# design.net
KiCad netlist of a schematic drawn in Altium Designer
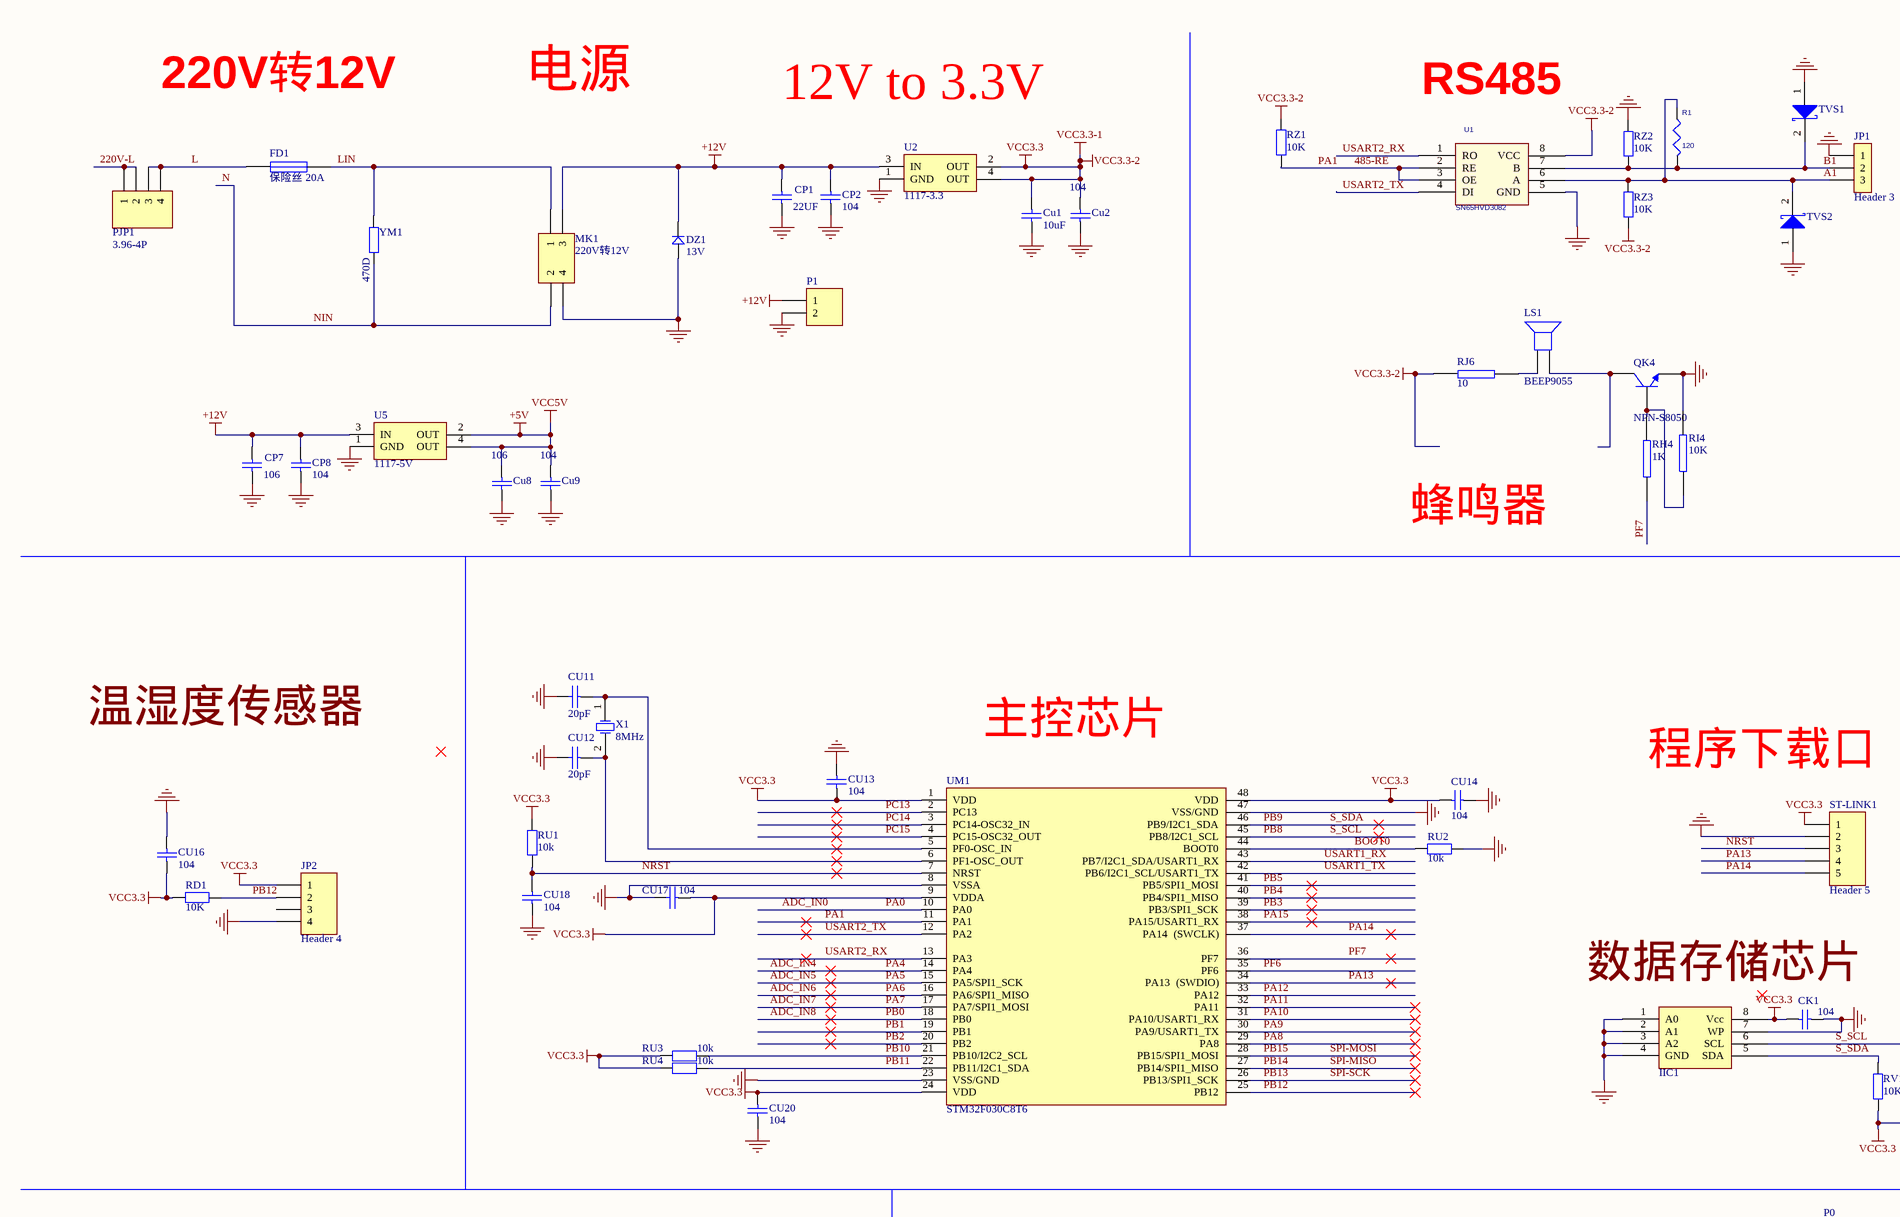
[diagram p0: 全兼容主控.SchDoc, top left]
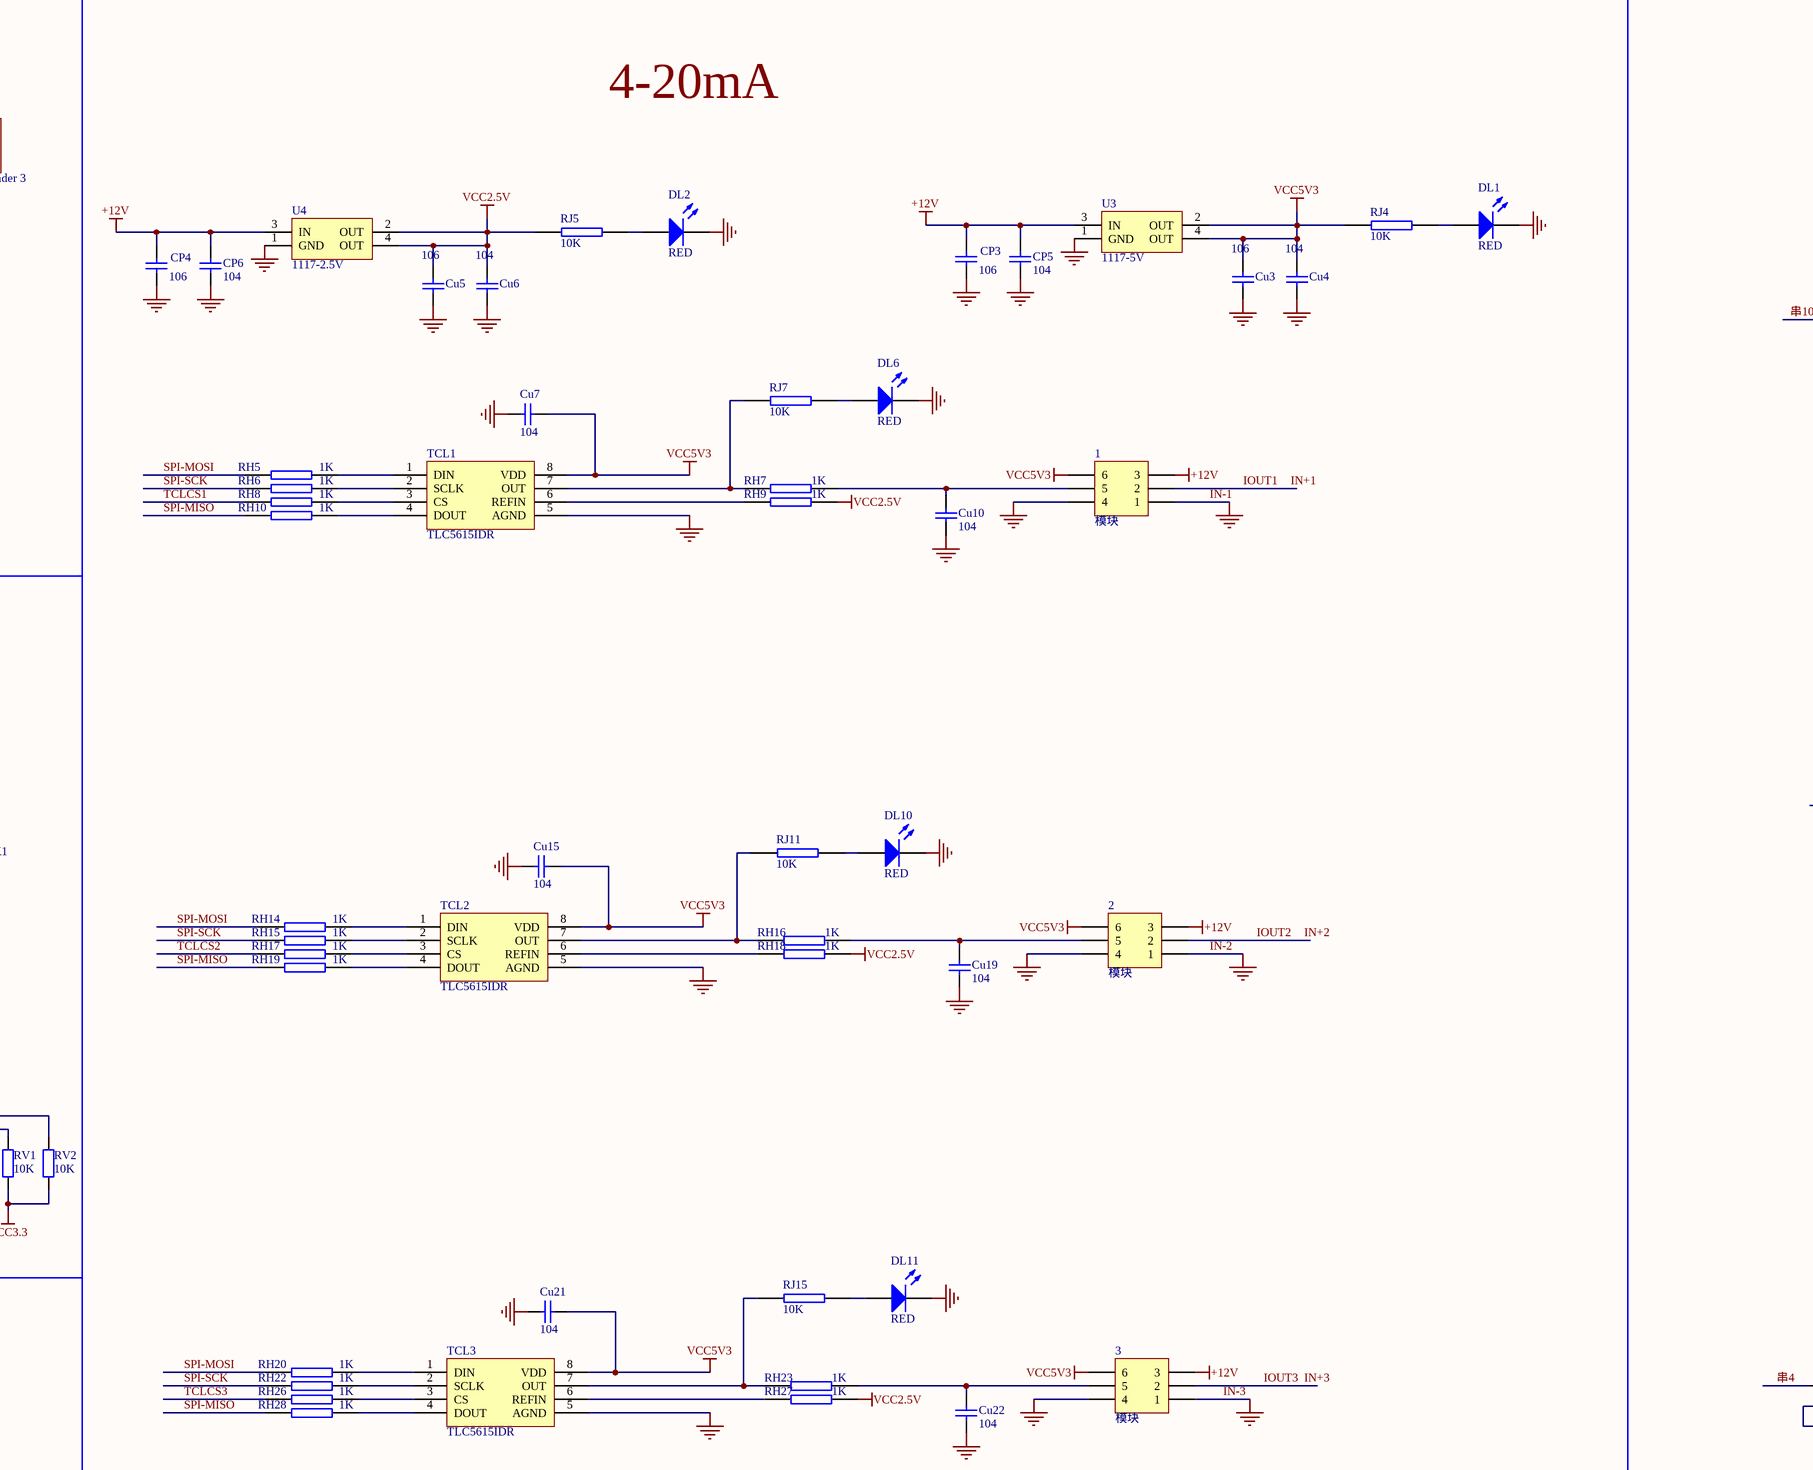
[diagram p1: 全兼容主控.SchDoc, top middle]
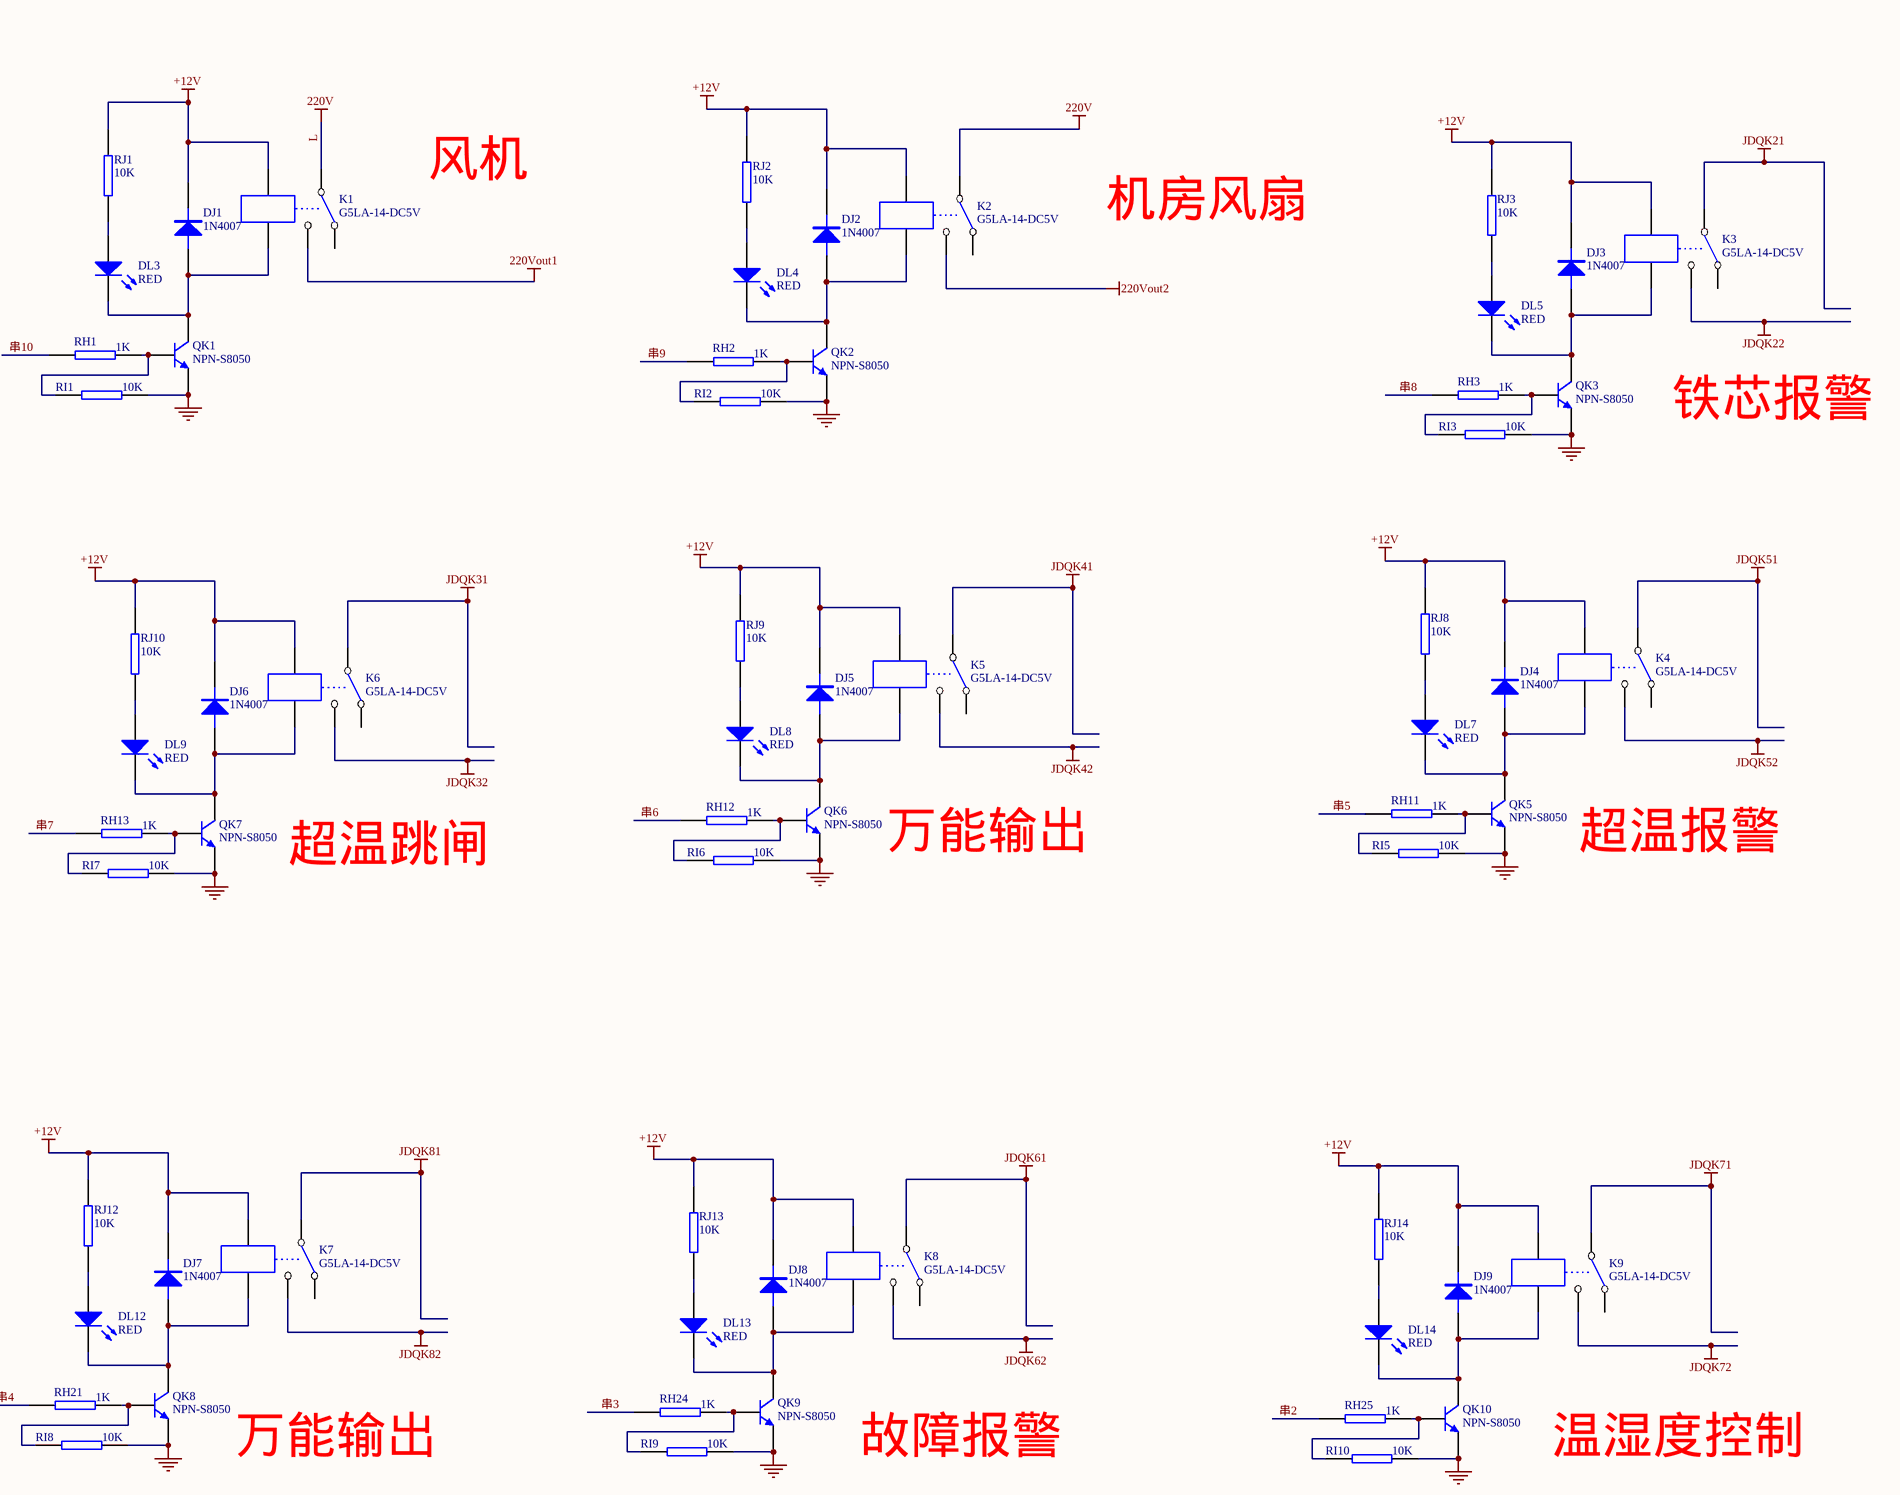
[diagram p2: 全兼容主控.SchDoc, top right]
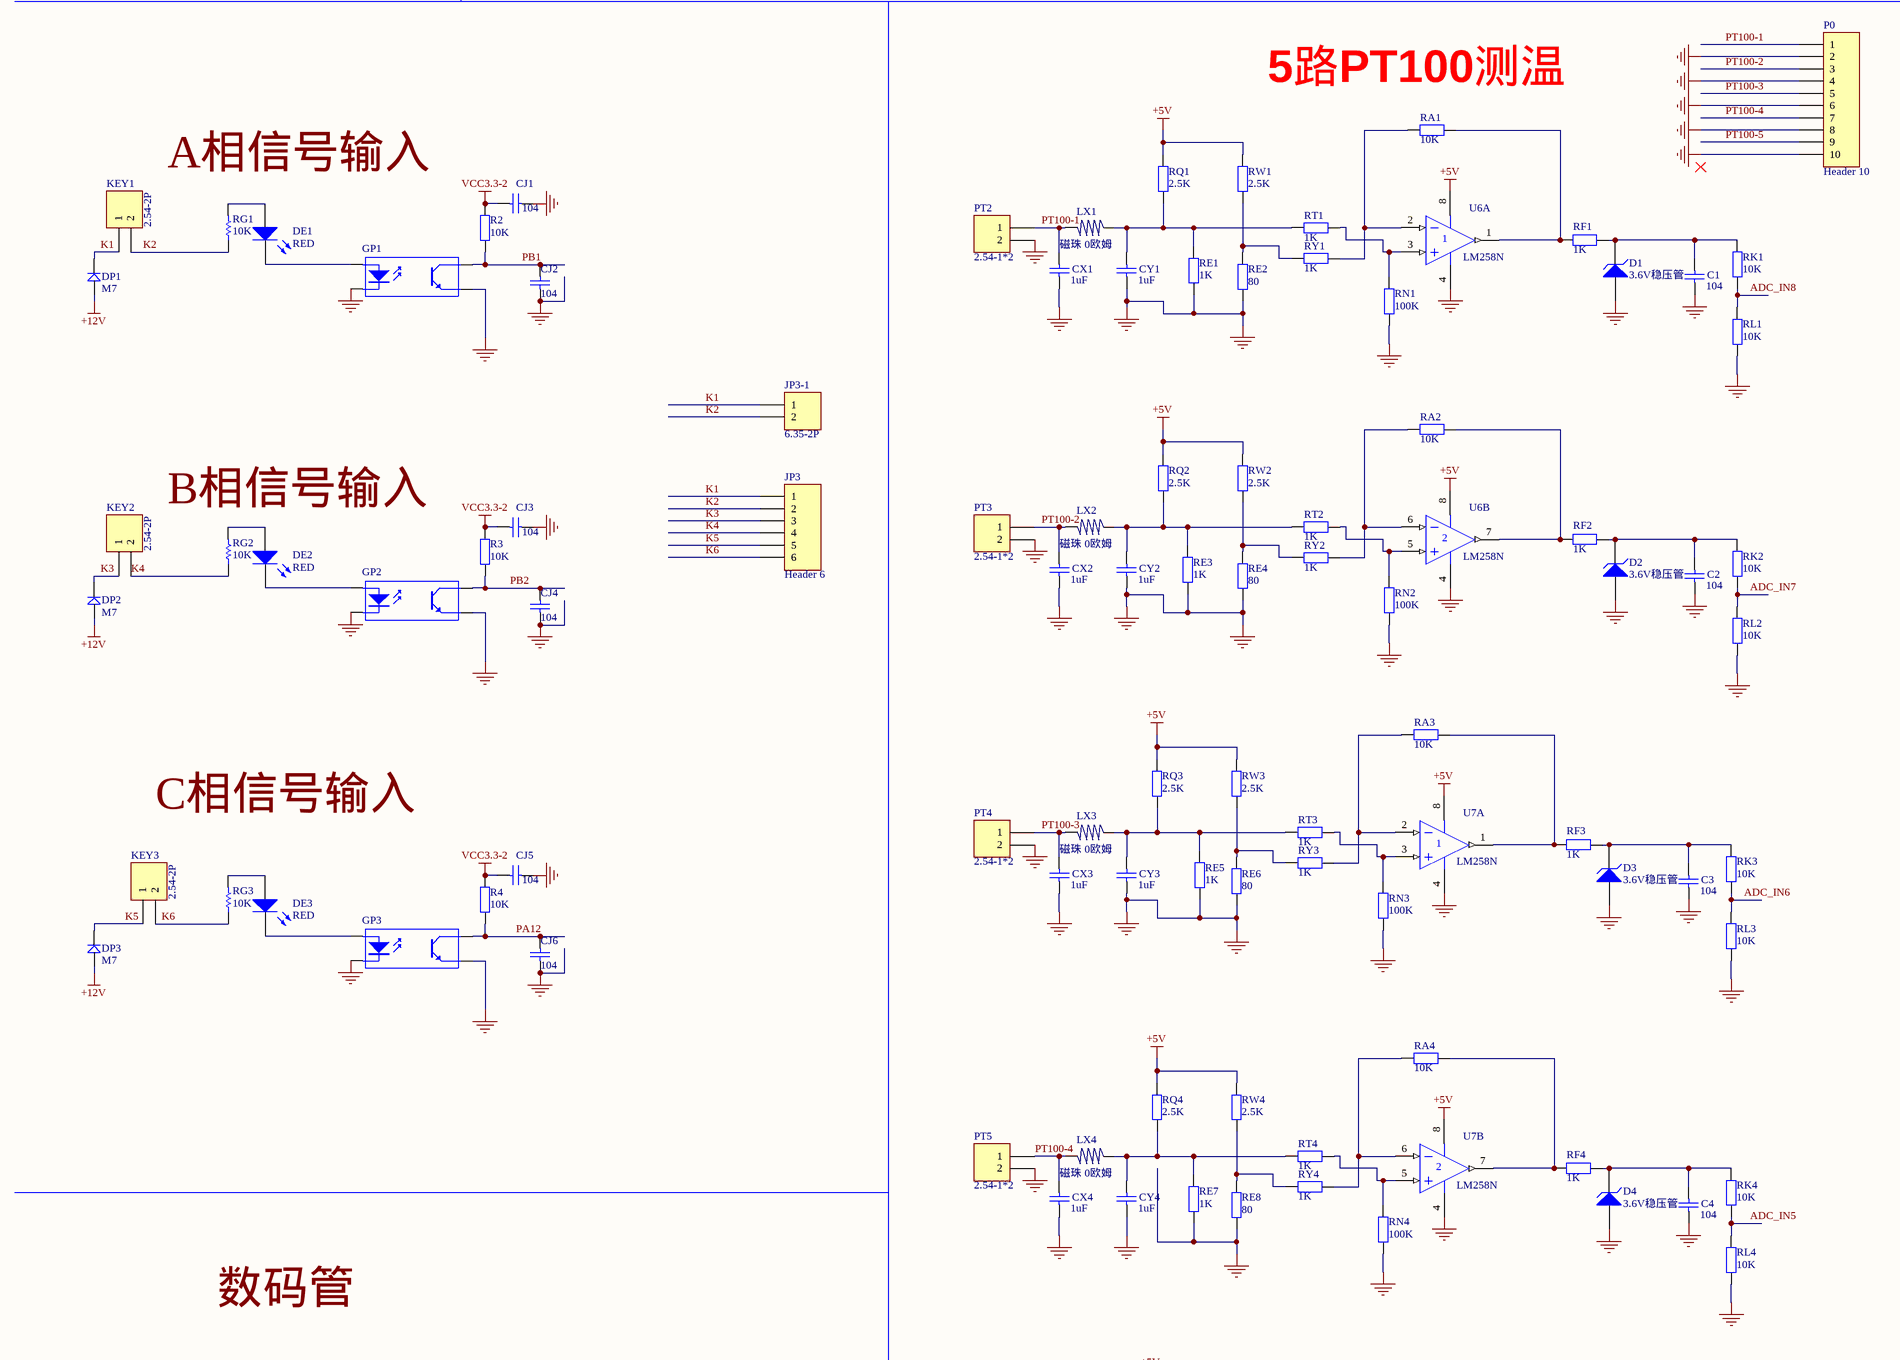
[diagram p3: 全兼容主控.SchDoc, centre left]
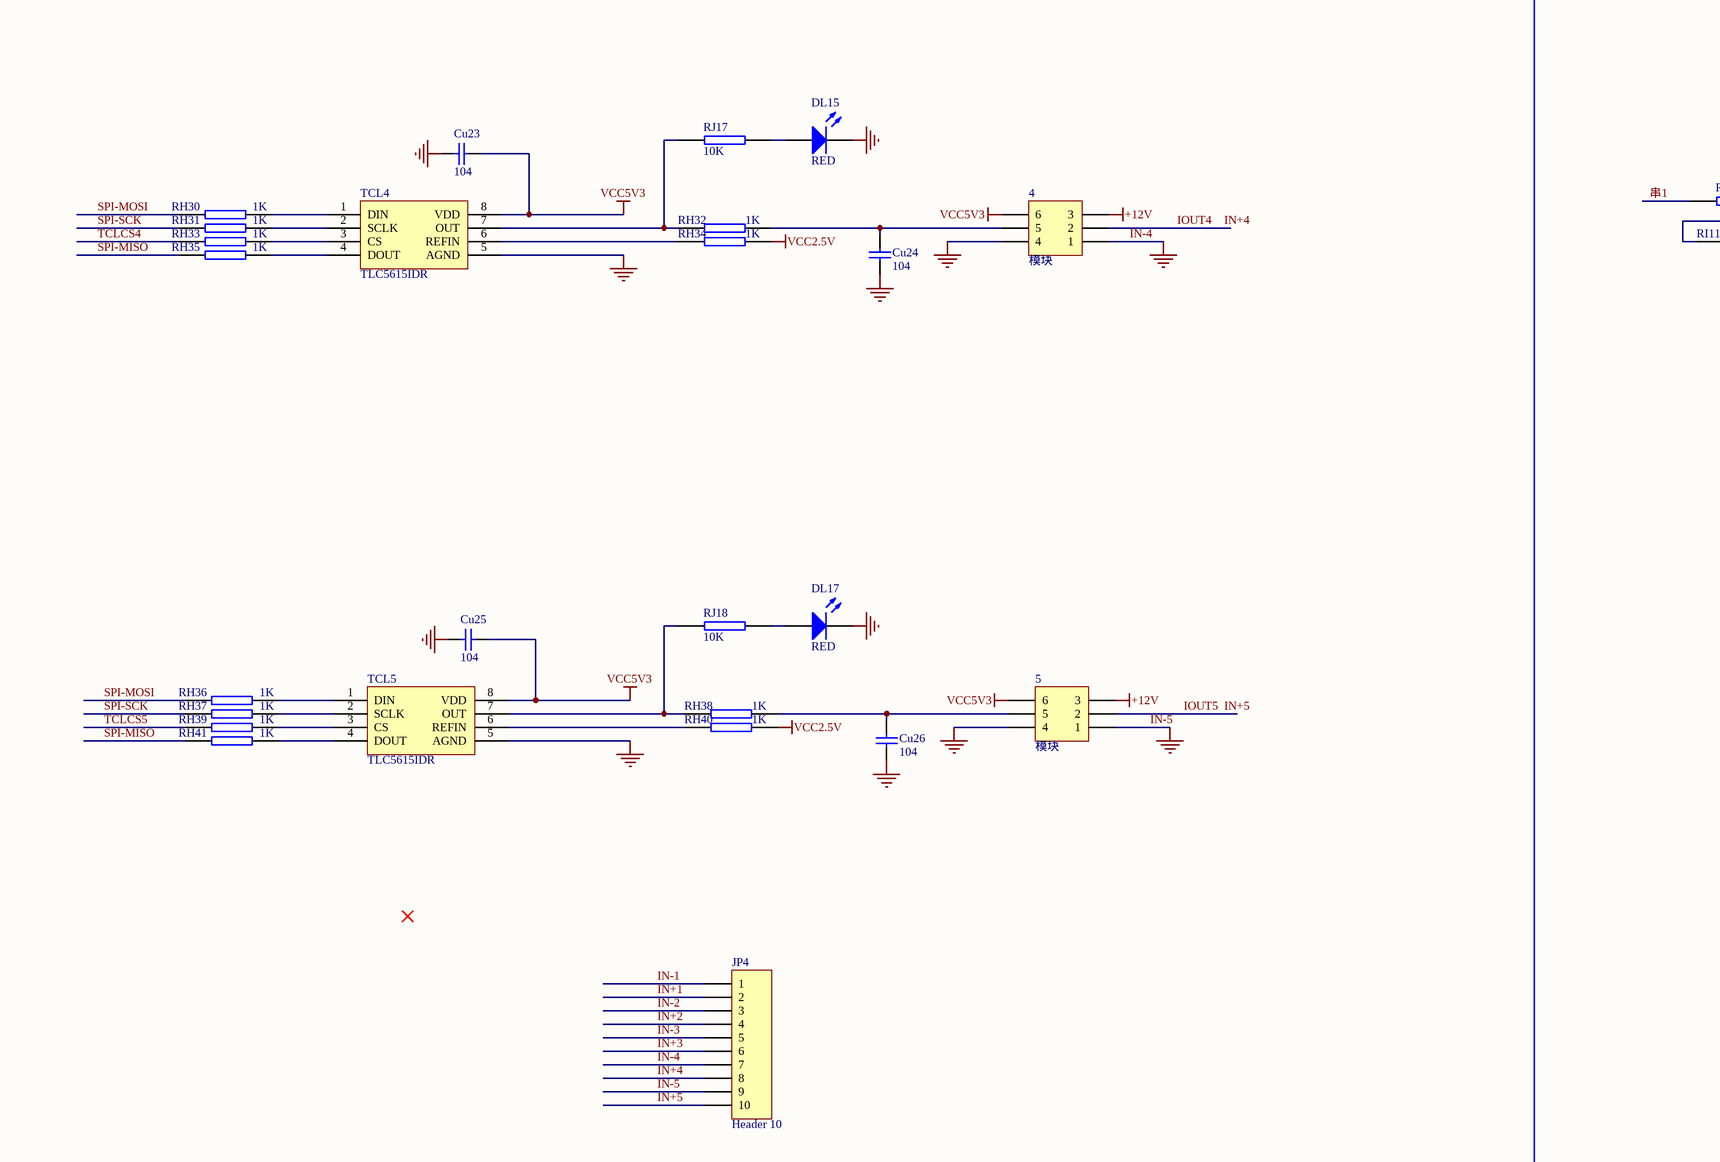
[diagram p4: 全兼容主控.SchDoc, centre middle]
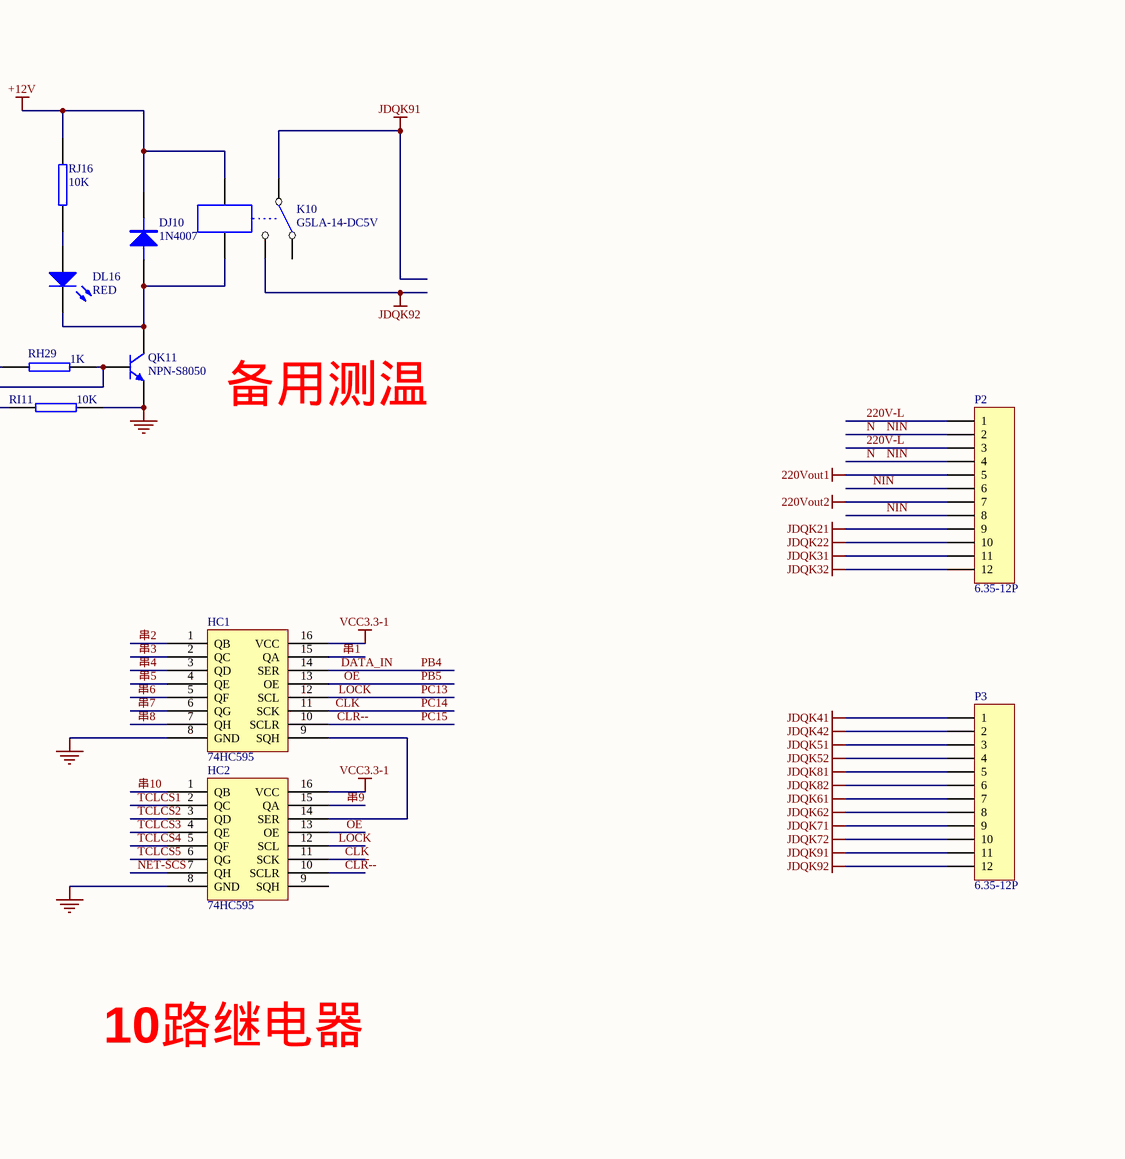
[diagram p5: 全兼容主控.SchDoc, centre right]
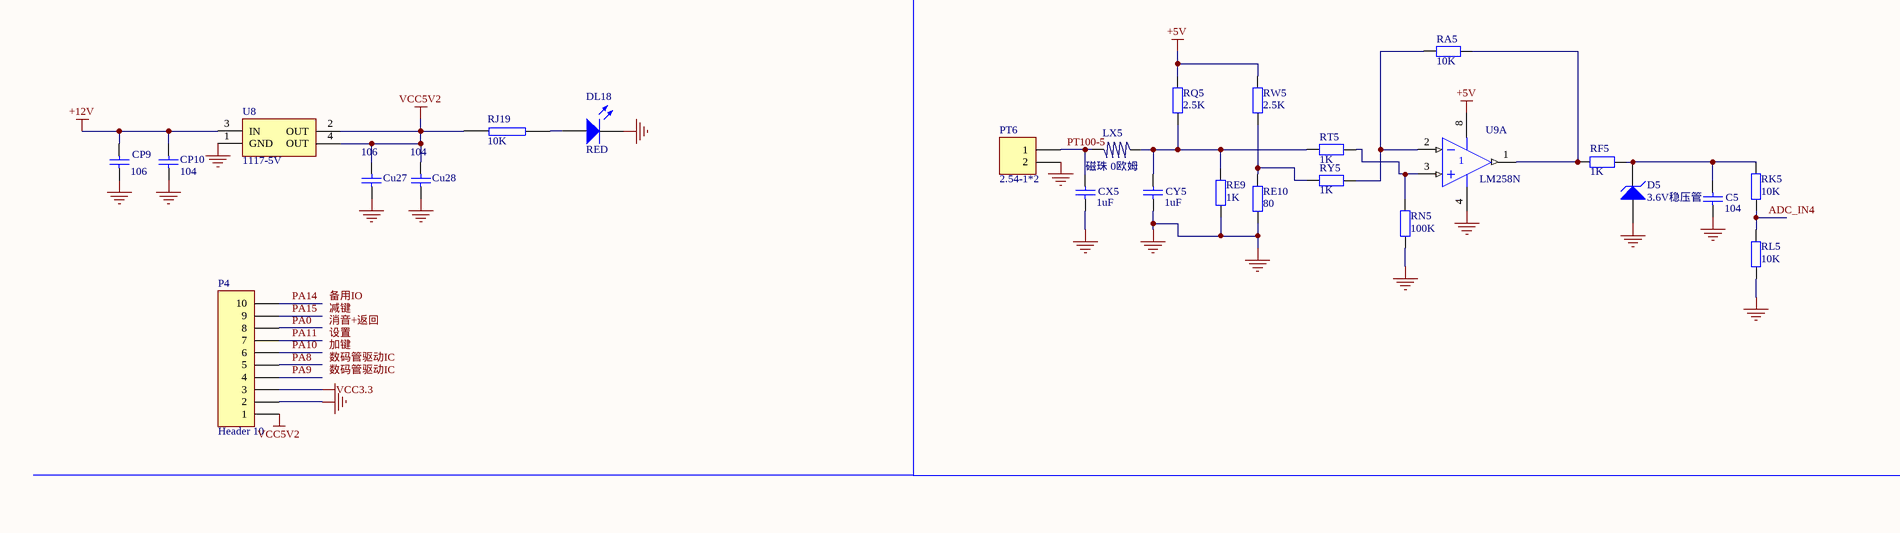
[diagram p6: 全兼容主控.SchDoc, bottom left]
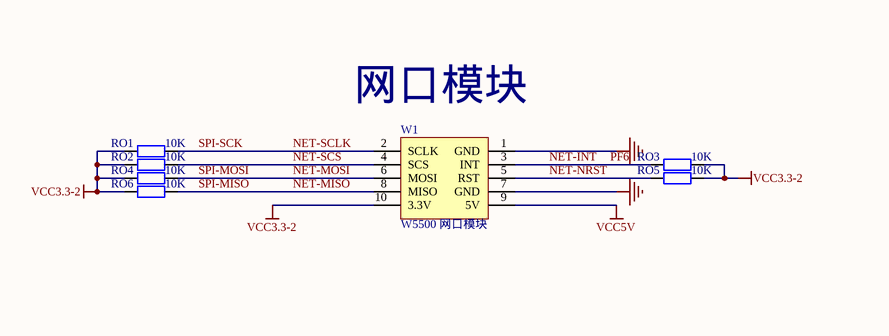
[diagram p7: 全兼容主控.SchDoc, bottom middle]
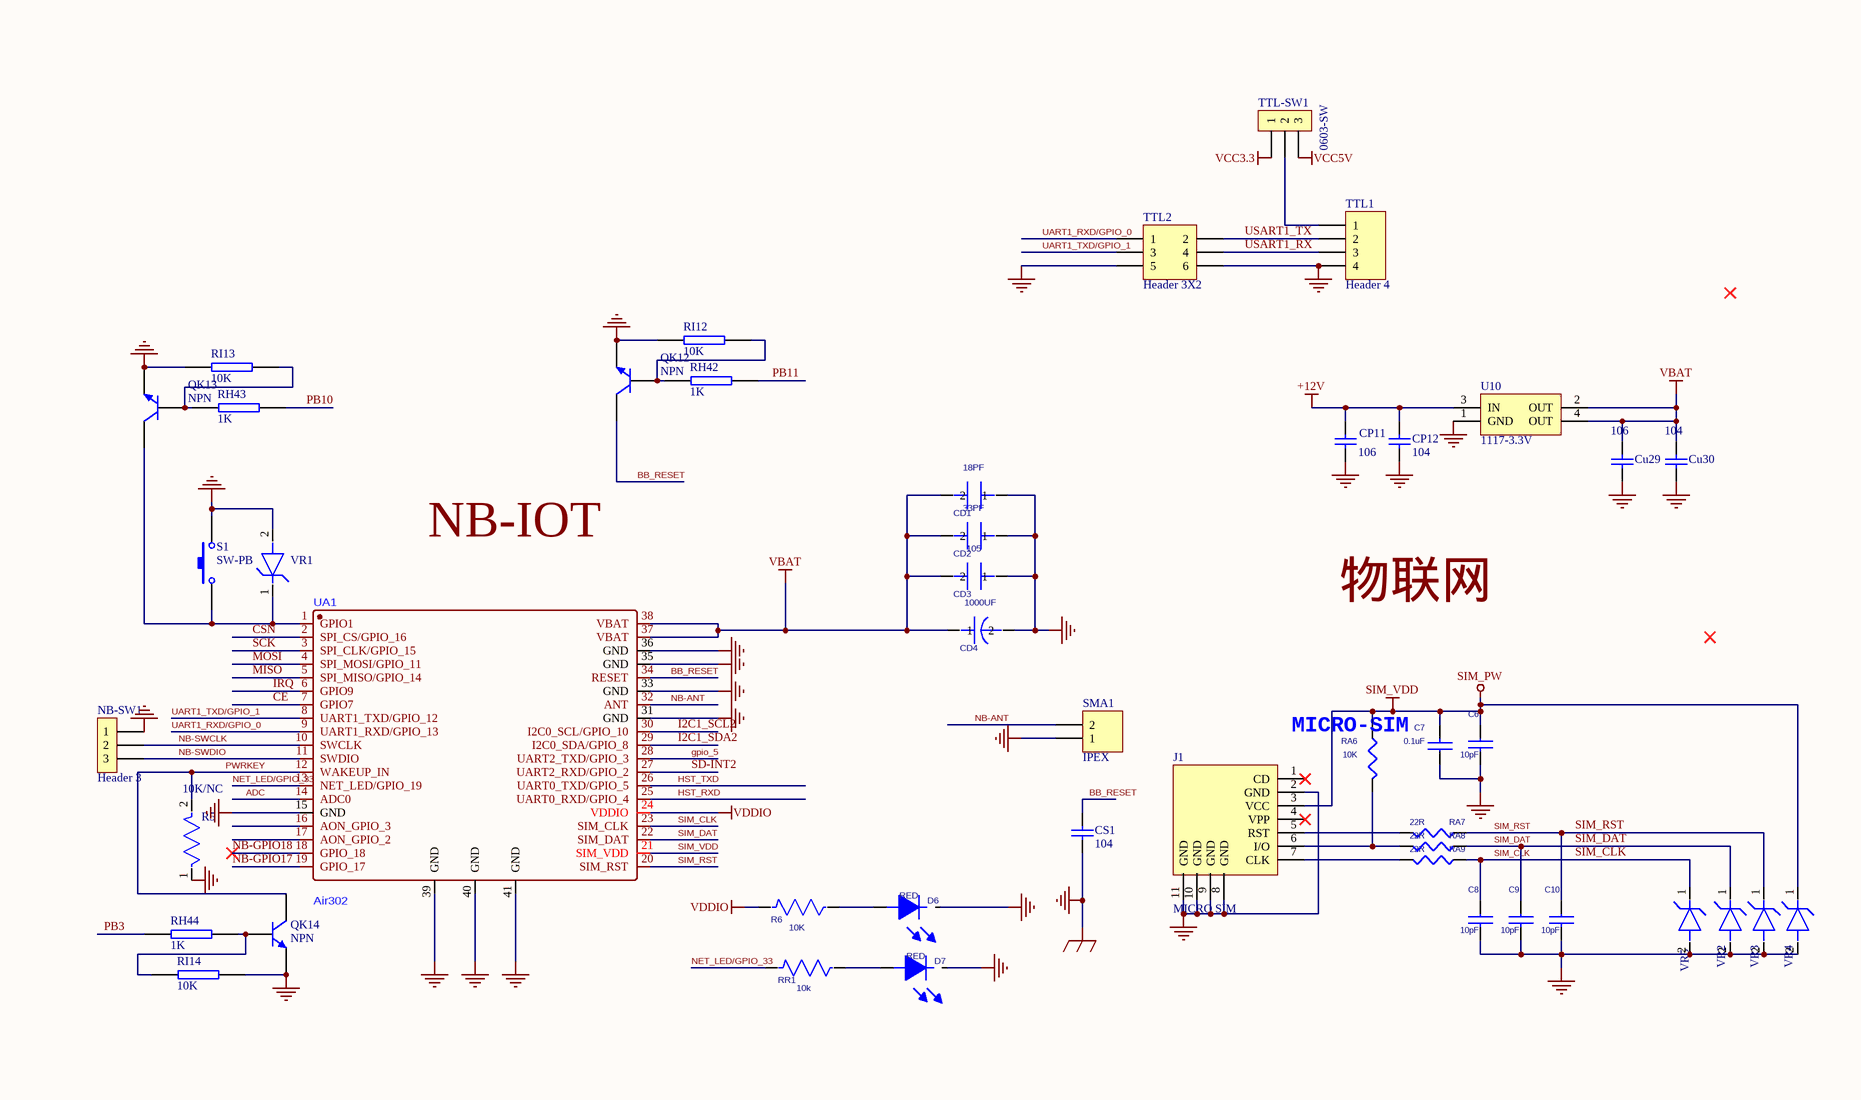
[diagram p8: 全兼容主控.SchDoc, bottom right]

(export (version "E")
  (design (tool "Eeschema 10.0.6"))
  (components
    (comp (ref "1")
      (value "模块")
      (footprint "0-5V转4-20mA")
      (description "Header, 3-Pin, Dual row")
      (libsource (lib "SCH原理图库") (part "Header 3X2A"))
    )
    (comp (ref "2")
      (value "模块")
      (footprint "0-5V转4-20mA")
      (description "Header, 3-Pin, Dual row")
      (libsource (lib "SCH原理图库") (part "Header 3X2A"))
    )
    (comp (ref "3")
      (value "模块")
      (footprint "0-5V转4-20mA")
      (description "Header, 3-Pin, Dual row")
      (libsource (lib "SCH原理图库") (part "Header 3X2A"))
    )
    (comp (ref "4")
      (value "模块")
      (footprint "0-5V转4-20mA")
      (description "Header, 3-Pin, Dual row")
      (libsource (lib "SCH原理图库") (part "Header 3X2A"))
    )
    (comp (ref "5")
      (value "模块")
      (footprint "0-5V转4-20mA")
      (description "Header, 3-Pin, Dual row")
      (libsource (lib "SCH原理图库") (part "Header 3X2A"))
    )
    (comp (ref "C1")
      (value "104")
      (footprint "0603-1")
      (description "Capacitor")
      (libsource (lib "Miscellaneous Devices") (part "Cap"))
    )
    (comp (ref "C2")
      (value "104")
      (footprint "0603-1")
      (description "Capacitor")
      (libsource (lib "Miscellaneous Devices") (part "Cap"))
    )
    (comp (ref "C3")
      (value "104")
      (footprint "0603-1")
      (description "Capacitor")
      (libsource (lib "Miscellaneous Devices") (part "Cap"))
    )
    (comp (ref "C4")
      (value "104")
      (footprint "0603-1")
      (description "Capacitor")
      (libsource (lib "Miscellaneous Devices") (part "Cap"))
    )
    (comp (ref "C5")
      (value "104")
      (footprint "0603-1")
      (description "Capacitor")
      (libsource (lib "Miscellaneous Devices") (part "Cap"))
    )
    (comp (ref "C6") (value "10pF") (footprint "0603-1") (libsource (lib "*") (part "CAP NP_Dup4")))
    (comp (ref "C7") (value "0.1uF") (footprint "0603-1") (libsource (lib "*") (part "CAP NP_Dup4")))
    (comp (ref "C8") (value "10pF") (footprint "0603-1") (libsource (lib "*") (part "CAP NP_Dup4")))
    (comp (ref "C9") (value "10pF") (footprint "0603-1") (libsource (lib "*") (part "CAP NP_Dup4")))
    (comp (ref "C10") (value "10pF") (footprint "0603-1") (libsource (lib "*") (part "CAP NP_Dup4")))
    (comp (ref "CD1")
      (value "18PF")
      (footprint "0603-1")
      (description "CAP CER C0G;18PF;+/-5%;50V;0402;0.5mm;ROHS")
      (libsource (lib "*") (part "CAP-18PF-0402-C0G"))
    )
    (comp (ref "CD2")
      (value "33PF")
      (footprint "0603-1")
      (description "CAP CER C0G;33PF;+/-5%;50V;0402;0.5mm;ROHS")
      (libsource (lib "*") (part "CAP-33PF-0402-C0G"))
    )
    (comp (ref "CD3")
      (value "105")
      (footprint "0603-1")
      (description "CAP CER X7R;0.1uF;+/-10%;16V;0402;0.5mm;ROHS")
      (libsource (lib "*") (part "CAP-0.1UF-0402-X7R"))
    )
    (comp (ref "CD4")
      (value "1000UF")
      (footprint "贴片电容-1000UF-10.4X10.4")
      (libsource (lib "*") (part "CAP-AL-1000UF-10.4X10.4"))
    )
    (comp (ref "CJ1")
      (value "104")
      (footprint "0603-1")
      (description "Capacitor")
      (fields (field (name "PUBLISHER") "Altium Limited"))
      (libsource (lib "原理图库") (part "104"))
    )
    (comp (ref "CJ2")
      (value "104")
      (footprint "0603-1")
      (description "Capacitor")
      (fields (field (name "PUBLISHER") "Altium Limited"))
      (libsource (lib "原理图库") (part "104"))
    )
    (comp (ref "CJ3")
      (value "104")
      (footprint "0603-1")
      (description "Capacitor")
      (fields (field (name "PUBLISHER") "Altium Limited"))
      (libsource (lib "原理图库") (part "104"))
    )
    (comp (ref "CJ4")
      (value "104")
      (footprint "0603-1")
      (description "Capacitor")
      (fields (field (name "PUBLISHER") "Altium Limited"))
      (libsource (lib "原理图库") (part "104"))
    )
    (comp (ref "CJ5")
      (value "104")
      (footprint "0603-1")
      (description "Capacitor")
      (fields (field (name "PUBLISHER") "Altium Limited"))
      (libsource (lib "原理图库") (part "104"))
    )
    (comp (ref "CJ6")
      (value "104")
      (footprint "0603-1")
      (description "Capacitor")
      (fields (field (name "PUBLISHER") "Altium Limited"))
      (libsource (lib "原理图库") (part "104"))
    )
    (comp (ref "CK1")
      (value "104")
      (footprint "0603-1")
      (description "Capacitor")
      (fields (field (name "PUBLISHER") "Altium Limited"))
      (libsource (lib "原理图库") (part "104"))
    )
    (comp (ref "CP1")
      (value "22UF")
      (footprint "0805")
      (description "Capacitor")
      (libsource (lib "原理图库") (part "104"))
    )
    (comp (ref "CP2")
      (value "104")
      (footprint "0603-1")
      (description "Capacitor")
      (libsource (lib "原理图库") (part "104"))
    )
    (comp (ref "CP3")
      (value "106")
      (footprint "0805")
      (description "Capacitor")
      (libsource (lib "原理图库") (part "104"))
    )
    (comp (ref "CP4")
      (value "106")
      (footprint "0805")
      (description "Capacitor")
      (libsource (lib "原理图库") (part "104"))
    )
    (comp (ref "CP5")
      (value "104")
      (footprint "0603-1")
      (description "Capacitor")
      (libsource (lib "原理图库") (part "104"))
    )
    (comp (ref "CP6")
      (value "104")
      (footprint "0603-1")
      (description "Capacitor")
      (libsource (lib "原理图库") (part "104"))
    )
    (comp (ref "CP7")
      (value "106")
      (footprint "0805")
      (description "Capacitor")
      (libsource (lib "原理图库") (part "104"))
    )
    (comp (ref "CP8")
      (value "104")
      (footprint "0603-1")
      (description "Capacitor")
      (libsource (lib "原理图库") (part "104"))
    )
    (comp (ref "CP9")
      (value "106")
      (footprint "0805")
      (description "Capacitor")
      (libsource (lib "原理图库") (part "104"))
    )
    (comp (ref "CP10")
      (value "104")
      (footprint "0603-1")
      (description "Capacitor")
      (libsource (lib "原理图库") (part "104"))
    )
    (comp (ref "CP11")
      (value "106")
      (footprint "0805")
      (description "Capacitor")
      (libsource (lib "原理图库") (part "104"))
    )
    (comp (ref "CP12")
      (value "104")
      (footprint "0603-1")
      (description "Capacitor")
      (libsource (lib "原理图库") (part "104"))
    )
    (comp (ref "CS1")
      (value "104")
      (footprint "0603-1")
      (description "Capacitor")
      (libsource (lib "原理图库") (part "104"))
    )
    (comp (ref "Cu1")
      (value "10uF")
      (footprint "0805")
      (description "Capacitor")
      (fields (field (name "Comment") "106") (field (name "PUBLISHER") "Altium Limited"))
      (libsource (lib "*") (part "Cap"))
    )
    (comp (ref "Cu2")
      (value "104")
      (footprint "0603-1")
      (description "Capacitor")
      (libsource (lib "*") (part "Cap"))
    )
    (comp (ref "Cu3")
      (value "106")
      (footprint "0805")
      (description "Capacitor")
      (libsource (lib "*") (part "Cap"))
    )
    (comp (ref "Cu4")
      (value "104")
      (footprint "0603-1")
      (description "Capacitor")
      (libsource (lib "*") (part "Cap"))
    )
    (comp (ref "Cu5")
      (value "106")
      (footprint "0805")
      (description "Capacitor")
      (libsource (lib "*") (part "Cap"))
    )
    (comp (ref "Cu6")
      (value "104")
      (footprint "0603-1")
      (description "Capacitor")
      (libsource (lib "*") (part "Cap"))
    )
    (comp (ref "Cu7")
      (value "104")
      (footprint "0603-1")
      (description "Capacitor")
      (libsource (lib "*") (part "Cap"))
    )
    (comp (ref "Cu8")
      (value "106")
      (footprint "0805")
      (description "Capacitor")
      (libsource (lib "*") (part "Cap"))
    )
    (comp (ref "Cu9")
      (value "104")
      (footprint "0603-1")
      (description "Capacitor")
      (libsource (lib "*") (part "Cap"))
    )
    (comp (ref "Cu10")
      (value "104")
      (footprint "0603-1")
      (description "Capacitor")
      (libsource (lib "*") (part "Cap"))
    )
    (comp (ref "CU11")
      (value "20pF")
      (footprint "0603-1")
      (description "Capacitor")
      (libsource (lib "*") (part "CAP"))
    )
    (comp (ref "CU12")
      (value "20pF")
      (footprint "0603-1")
      (description "Capacitor")
      (libsource (lib "*") (part "CAP"))
    )
    (comp (ref "CU13")
      (value "104")
      (footprint "0603-1")
      (description "Capacitor")
      (fields (field (name "PUBLISHER") "Altium Limited"))
      (libsource (lib "Miscellaneous Devices") (part "Cap"))
    )
    (comp (ref "CU14")
      (value "104")
      (footprint "0603-1")
      (description "Capacitor")
      (fields (field (name "PUBLISHER") "Altium Limited"))
      (libsource (lib "Miscellaneous Devices") (part "Cap"))
    )
    (comp (ref "Cu15")
      (value "104")
      (footprint "0603-1")
      (description "Capacitor")
      (libsource (lib "*") (part "Cap"))
    )
    (comp (ref "CU16")
      (value "104")
      (footprint "0603-1")
      (description "Capacitor")
      (fields (field (name "PUBLISHER") "Altium Limited"))
      (libsource (lib "Miscellaneous Devices") (part "Cap"))
    )
    (comp (ref "CU17")
      (value "104")
      (footprint "0603-1")
      (description "Capacitor")
      (libsource (lib "*") (part "CAP"))
    )
    (comp (ref "CU18")
      (value "104")
      (footprint "0603-1")
      (description "Capacitor")
      (fields (field (name "PUBLISHER") "Altium Limited"))
      (libsource (lib "Miscellaneous Devices") (part "Cap"))
    )
    (comp (ref "Cu19")
      (value "104")
      (footprint "0603-1")
      (description "Capacitor")
      (libsource (lib "*") (part "Cap"))
    )
    (comp (ref "CU20")
      (value "104")
      (footprint "0603-1")
      (description "Capacitor")
      (fields (field (name "PUBLISHER") "Altium Limited"))
      (libsource (lib "Miscellaneous Devices") (part "Cap"))
    )
    (comp (ref "Cu21")
      (value "104")
      (footprint "0603-1")
      (description "Capacitor")
      (libsource (lib "*") (part "Cap"))
    )
    (comp (ref "Cu22")
      (value "104")
      (footprint "0603-1")
      (description "Capacitor")
      (libsource (lib "*") (part "Cap"))
    )
    (comp (ref "Cu23")
      (value "104")
      (footprint "0603-1")
      (description "Capacitor")
      (libsource (lib "*") (part "Cap"))
    )
    (comp (ref "Cu24")
      (value "104")
      (footprint "0603-1")
      (description "Capacitor")
      (libsource (lib "*") (part "Cap"))
    )
    (comp (ref "Cu25")
      (value "104")
      (footprint "0603-1")
      (description "Capacitor")
      (libsource (lib "*") (part "Cap"))
    )
    (comp (ref "Cu26")
      (value "104")
      (footprint "0603-1")
      (description "Capacitor")
      (libsource (lib "*") (part "Cap"))
    )
    (comp (ref "Cu27")
      (value "106")
      (footprint "0805")
      (description "Capacitor")
      (libsource (lib "*") (part "Cap"))
    )
    (comp (ref "Cu28")
      (value "104")
      (footprint "0603-1")
      (description "Capacitor")
      (libsource (lib "*") (part "Cap"))
    )
    (comp (ref "Cu29")
      (value "106")
      (footprint "0805")
      (description "Capacitor")
      (libsource (lib "*") (part "Cap"))
    )
    (comp (ref "Cu30")
      (value "104")
      (footprint "0603-1")
      (description "Capacitor")
      (libsource (lib "*") (part "Cap"))
    )
    (comp (ref "CX1")
      (value "1uF")
      (footprint "1206")
      (description "Capacitor")
      (libsource (lib "Miscellaneous Devices") (part "Cap"))
    )
    (comp (ref "CX2")
      (value "1uF")
      (footprint "1206")
      (description "Capacitor")
      (libsource (lib "Miscellaneous Devices") (part "Cap"))
    )
    (comp (ref "CX3")
      (value "1uF")
      (footprint "1206")
      (description "Capacitor")
      (libsource (lib "Miscellaneous Devices") (part "Cap"))
    )
    (comp (ref "CX4")
      (value "1uF")
      (footprint "1206")
      (description "Capacitor")
      (libsource (lib "Miscellaneous Devices") (part "Cap"))
    )
    (comp (ref "CX5")
      (value "1uF")
      (footprint "1206")
      (description "Capacitor")
      (libsource (lib "Miscellaneous Devices") (part "Cap"))
    )
    (comp (ref "CY1")
      (value "1uF")
      (footprint "1206")
      (description "Capacitor")
      (libsource (lib "Miscellaneous Devices") (part "Cap"))
    )
    (comp (ref "CY2")
      (value "1uF")
      (footprint "1206")
      (description "Capacitor")
      (libsource (lib "Miscellaneous Devices") (part "Cap"))
    )
    (comp (ref "CY3")
      (value "1uF")
      (footprint "1206")
      (description "Capacitor")
      (libsource (lib "Miscellaneous Devices") (part "Cap"))
    )
    (comp (ref "CY4")
      (value "1uF")
      (footprint "1206")
      (description "Capacitor")
      (libsource (lib "Miscellaneous Devices") (part "Cap"))
    )
    (comp (ref "CY5")
      (value "1uF")
      (footprint "1206")
      (description "Capacitor")
      (libsource (lib "Miscellaneous Devices") (part "Cap"))
    )
    (comp (ref "D1")
      (value "3.6V稳压管")
      (footprint "DIODE")
      (description "Zener Diode")
      (libsource (lib "Miscellaneous Devices") (part "D Zener"))
    )
    (comp (ref "D2")
      (value "3.6V稳压管")
      (footprint "DIODE")
      (description "Zener Diode")
      (libsource (lib "Miscellaneous Devices") (part "D Zener"))
    )
    (comp (ref "D3")
      (value "3.6V稳压管")
      (footprint "DIODE")
      (description "Zener Diode")
      (libsource (lib "Miscellaneous Devices") (part "D Zener"))
    )
    (comp (ref "D4")
      (value "3.6V稳压管")
      (footprint "DIODE")
      (description "Zener Diode")
      (libsource (lib "Miscellaneous Devices") (part "D Zener"))
    )
    (comp (ref "D5")
      (value "3.6V稳压管")
      (footprint "DIODE")
      (description "Zener Diode")
      (libsource (lib "Miscellaneous Devices") (part "D Zener"))
    )
    (comp (ref "D6")
      (value "RED")
      (footprint "0603 - LED")
      (description "LED;Blue;3V;LED-0603;0.5mm;ROHS")
      (libsource (lib "*") (part "DIODE-LED-BLUE-0603"))
    )
    (comp (ref "D7")
      (value "RED")
      (footprint "0603 - LED")
      (description "LED;Blue;3V;LED-0603;0.5mm;ROHS")
      (libsource (lib "*") (part "DIODE-LED-BLUE-0603"))
    )
    (comp (ref "DE1")
      (value "RED")
      (footprint "0603 - LED")
      (description "Typical RED GaAs LED")
      (fields (field (name "PUBLISHER") "Altium Limited"))
      (libsource (lib "原理图库") (part "LED1"))
    )
    (comp (ref "DE2")
      (value "RED")
      (footprint "0603 - LED")
      (description "Typical RED GaAs LED")
      (fields (field (name "PUBLISHER") "Altium Limited"))
      (libsource (lib "原理图库") (part "LED1"))
    )
    (comp (ref "DE3")
      (value "RED")
      (footprint "0603 - LED")
      (description "Typical RED GaAs LED")
      (fields (field (name "PUBLISHER") "Altium Limited"))
      (libsource (lib "原理图库") (part "LED1"))
    )
    (comp (ref "DJ1")
      (value "1N4007")
      (footprint "DIODE")
      (description "Diode")
      (libsource (lib "*") (part "DIODE"))
    )
    (comp (ref "DJ2")
      (value "1N4007")
      (footprint "DIODE")
      (description "Diode")
      (libsource (lib "*") (part "DIODE"))
    )
    (comp (ref "DJ3")
      (value "1N4007")
      (footprint "DIODE")
      (description "Diode")
      (libsource (lib "*") (part "DIODE"))
    )
    (comp (ref "DJ4")
      (value "1N4007")
      (footprint "DIODE")
      (description "Diode")
      (libsource (lib "*") (part "DIODE"))
    )
    (comp (ref "DJ5")
      (value "1N4007")
      (footprint "DIODE")
      (description "Diode")
      (libsource (lib "*") (part "DIODE"))
    )
    (comp (ref "DJ6")
      (value "1N4007")
      (footprint "DIODE")
      (description "Diode")
      (libsource (lib "*") (part "DIODE"))
    )
    (comp (ref "DJ7")
      (value "1N4007")
      (footprint "DIODE")
      (description "Diode")
      (libsource (lib "*") (part "DIODE"))
    )
    (comp (ref "DJ8")
      (value "1N4007")
      (footprint "DIODE")
      (description "Diode")
      (libsource (lib "*") (part "DIODE"))
    )
    (comp (ref "DJ9")
      (value "1N4007")
      (footprint "DIODE")
      (description "Diode")
      (libsource (lib "*") (part "DIODE"))
    )
    (comp (ref "DJ10")
      (value "1N4007")
      (footprint "DIODE")
      (description "Diode")
      (libsource (lib "*") (part "DIODE"))
    )
    (comp (ref "DL1")
      (value "RED")
      (footprint "0603 - LED")
      (description "Typical RED GaAs LED")
      (fields (field (name "PUBLISHER") "Altium Limited"))
      (libsource (lib "原理图库") (part "LED1"))
    )
    (comp (ref "DL2")
      (value "RED")
      (footprint "0603 - LED")
      (description "Typical RED GaAs LED")
      (fields (field (name "PUBLISHER") "Altium Limited"))
      (libsource (lib "原理图库") (part "LED1"))
    )
    (comp (ref "DL3")
      (value "RED")
      (footprint "0603 - LED")
      (description "Typical RED GaAs LED")
      (fields (field (name "PUBLISHER") "Altium Limited"))
      (libsource (lib "原理图库") (part "LED1"))
    )
    (comp (ref "DL4")
      (value "RED")
      (footprint "0603 - LED")
      (description "Typical RED GaAs LED")
      (fields (field (name "PUBLISHER") "Altium Limited"))
      (libsource (lib "原理图库") (part "LED1"))
    )
    (comp (ref "DL5")
      (value "RED")
      (footprint "0603 - LED")
      (description "Typical RED GaAs LED")
      (fields (field (name "PUBLISHER") "Altium Limited"))
      (libsource (lib "原理图库") (part "LED1"))
    )
    (comp (ref "DL6")
      (value "RED")
      (footprint "0603 - LED")
      (description "Typical RED GaAs LED")
      (fields (field (name "PUBLISHER") "Altium Limited"))
      (libsource (lib "原理图库") (part "LED1"))
    )
    (comp (ref "DL7")
      (value "RED")
      (footprint "0603 - LED")
      (description "Typical RED GaAs LED")
      (fields (field (name "PUBLISHER") "Altium Limited"))
      (libsource (lib "原理图库") (part "LED1"))
    )
    (comp (ref "DL8")
      (value "RED")
      (footprint "0603 - LED")
      (description "Typical RED GaAs LED")
      (fields (field (name "PUBLISHER") "Altium Limited"))
      (libsource (lib "原理图库") (part "LED1"))
    )
    (comp (ref "DL9")
      (value "RED")
      (footprint "0603 - LED")
      (description "Typical RED GaAs LED")
      (fields (field (name "PUBLISHER") "Altium Limited"))
      (libsource (lib "原理图库") (part "LED1"))
    )
    (comp (ref "DL10")
      (value "RED")
      (footprint "0603 - LED")
      (description "Typical RED GaAs LED")
      (fields (field (name "PUBLISHER") "Altium Limited"))
      (libsource (lib "原理图库") (part "LED1"))
    )
    (comp (ref "DL11")
      (value "RED")
      (footprint "0603 - LED")
      (description "Typical RED GaAs LED")
      (fields (field (name "PUBLISHER") "Altium Limited"))
      (libsource (lib "原理图库") (part "LED1"))
    )
    (comp (ref "DL12")
      (value "RED")
      (footprint "0603 - LED")
      (description "Typical RED GaAs LED")
      (fields (field (name "PUBLISHER") "Altium Limited"))
      (libsource (lib "原理图库") (part "LED1"))
    )
    (comp (ref "DL13")
      (value "RED")
      (footprint "0603 - LED")
      (description "Typical RED GaAs LED")
      (fields (field (name "PUBLISHER") "Altium Limited"))
      (libsource (lib "原理图库") (part "LED1"))
    )
    (comp (ref "DL14")
      (value "RED")
      (footprint "0603 - LED")
      (description "Typical RED GaAs LED")
      (fields (field (name "PUBLISHER") "Altium Limited"))
      (libsource (lib "原理图库") (part "LED1"))
    )
    (comp (ref "DL15")
      (value "RED")
      (footprint "0603 - LED")
      (description "Typical RED GaAs LED")
      (fields (field (name "PUBLISHER") "Altium Limited"))
      (libsource (lib "原理图库") (part "LED1"))
    )
    (comp (ref "DL16")
      (value "RED")
      (footprint "0603 - LED")
      (description "Typical RED GaAs LED")
      (fields (field (name "PUBLISHER") "Altium Limited"))
      (libsource (lib "原理图库") (part "LED1"))
    )
    (comp (ref "DL17")
      (value "RED")
      (footprint "0603 - LED")
      (description "Typical RED GaAs LED")
      (fields (field (name "PUBLISHER") "Altium Limited"))
      (libsource (lib "原理图库") (part "LED1"))
    )
    (comp (ref "DL18")
      (value "RED")
      (footprint "0603 - LED")
      (description "Typical RED GaAs LED")
      (fields (field (name "PUBLISHER") "Altium Limited"))
      (libsource (lib "原理图库") (part "LED1"))
    )
    (comp (ref "DP1") (value "M7") (footprint "DIODE") (libsource (lib "SCH原理图库") (part "D")))
    (comp (ref "DP2") (value "M7") (footprint "DIODE") (libsource (lib "SCH原理图库") (part "D")))
    (comp (ref "DP3") (value "M7") (footprint "DIODE") (libsource (lib "SCH原理图库") (part "D")))
    (comp (ref "DZ1") (value "13V") (footprint "DIODE") (libsource (lib "SCH原理图库") (part "D")))
    (comp (ref "FD1")
      (value "保险丝 20A")
      (footprint "1808")
      (description "Fuse")
      (libsource (lib "原理图库") (part "Fuse 1"))
    )
    (comp (ref "GP1")
      (value "guangou*1")
      (footprint "PC817 SMD-4P")
      (libsource (lib "SCH原理图库") (part "guangou*1"))
    )
    (comp (ref "GP2")
      (value "guangou*1")
      (footprint "PC817 SMD-4P")
      (libsource (lib "SCH原理图库") (part "guangou*1"))
    )
    (comp (ref "GP3")
      (value "guangou*1")
      (footprint "PC817 SMD-4P")
      (libsource (lib "SCH原理图库") (part "guangou*1"))
    )
    (comp (ref "HC1") (value "74HC595") (footprint "SOP-16") (libsource (lib "74系列") (part "74HC595")))
    (comp (ref "HC2") (value "74HC595") (footprint "SOP-16") (libsource (lib "74系列") (part "74HC595")))
    (comp (ref "IIC1") (value "24c64") (footprint "SOP-8P") (libsource (lib "SCH原理图库") (part "24c64")))
    (comp (ref "J1")
      (value "MICRO SIM")
      (footprint "Nano-SIM卡 自弹式")
      (libsource (lib "my yltk") (part "MICRO SIM"))
    )
    (comp (ref "JP1")
      (value "Header 3")
      (footprint "HDR1X3")
      (description "Header, 3-Pin")
      (fields (field (name "PUBLISHER") "Altium Limited"))
      (libsource (lib "SCH原理图库") (part "Header 3"))
    )
    (comp (ref "JP2")
      (value "Header 4")
      (footprint "HDR1X4")
      (description "Header, 4-Pin")
      (fields (field (name "PUBLISHER") "Altium Limited"))
      (libsource (lib "SCH原理图库") (part "Header 4"))
    )
    (comp (ref "JP3")
      (value "Header 6")
      (footprint "HDR1X6")
      (description "Header, 6-Pin")
      (fields (field (name "PUBLISHER") "Altium Limited"))
      (libsource (lib "SCH原理图库") (part "Header 6"))
    )
    (comp (ref "JP3-1")
      (value "6.35-2P")
      (footprint "6.35-2P")
      (description "Header, 2-Pin")
      (libsource (lib "") (part "Header 2_2"))
    )
    (comp (ref "JP4")
      (value "Header 10")
      (footprint "HDR1X10")
      (description "Header, 10-Pin")
      (fields (field (name "PUBLISHER") "Altium Limited"))
      (libsource (lib "SCH原理图库") (part "Header 10"))
    )
    (comp (ref "K1")
      (value "G5LA-14-DC5V")
      (footprint "继电器 松乐SRD-12VDC-SL-C")
      (libsource (lib "*") (part "RELAY-SPDT"))
    )
    (comp (ref "K2")
      (value "G5LA-14-DC5V")
      (footprint "继电器 松乐SRD-12VDC-SL-C")
      (libsource (lib "*") (part "RELAY-SPDT"))
    )
    (comp (ref "K3")
      (value "G5LA-14-DC5V")
      (footprint "继电器 松乐SRD-12VDC-SL-C")
      (libsource (lib "*") (part "RELAY-SPDT"))
    )
    (comp (ref "K4")
      (value "G5LA-14-DC5V")
      (footprint "继电器 松乐SRD-12VDC-SL-C")
      (libsource (lib "*") (part "RELAY-SPDT"))
    )
    (comp (ref "K5")
      (value "G5LA-14-DC5V")
      (footprint "继电器 松乐SRD-12VDC-SL-C")
      (libsource (lib "*") (part "RELAY-SPDT"))
    )
    (comp (ref "K6")
      (value "G5LA-14-DC5V")
      (footprint "继电器 松乐SRD-12VDC-SL-C")
      (libsource (lib "*") (part "RELAY-SPDT"))
    )
    (comp (ref "K7")
      (value "G5LA-14-DC5V")
      (footprint "继电器 松乐SRD-12VDC-SL-C")
      (libsource (lib "*") (part "RELAY-SPDT"))
    )
    (comp (ref "K8")
      (value "G5LA-14-DC5V")
      (footprint "继电器 松乐SRD-12VDC-SL-C")
      (libsource (lib "*") (part "RELAY-SPDT"))
    )
    (comp (ref "K9")
      (value "G5LA-14-DC5V")
      (footprint "继电器 松乐SRD-12VDC-SL-C")
      (libsource (lib "*") (part "RELAY-SPDT"))
    )
    (comp (ref "K10")
      (value "G5LA-14-DC5V")
      (footprint "继电器 松乐SRD-12VDC-SL-C")
      (libsource (lib "*") (part "RELAY-SPDT"))
    )
    (comp (ref "KEY1")
      (value "2.54-2P")
      (footprint "HDR1X2")
      (description "Header, 2-Pin")
      (fields (field (name "PUBLISHER") "Altium Limited"))
      (libsource (lib "") (part "Header 2_1"))
    )
    (comp (ref "KEY2")
      (value "2.54-2P")
      (footprint "HDR1X2")
      (description "Header, 2-Pin")
      (fields (field (name "PUBLISHER") "Altium Limited"))
      (libsource (lib "") (part "Header 2_1"))
    )
    (comp (ref "KEY3")
      (value "2.54-2P")
      (footprint "HDR1X2")
      (description "Header, 2-Pin")
      (fields (field (name "PUBLISHER") "Altium Limited"))
      (libsource (lib "") (part "Header 2_1"))
    )
    (comp (ref "LS1")
      (value "BEEP9055")
      (footprint "BEEP9055")
      (description "Loudspeaker")
      (libsource (lib "SCH原理图库") (part "Speaker"))
    )
    (comp (ref "LX1") (value "磁珠 0欧姆") (footprint "1206") (libsource (lib "SCH原理图库") (part "L")))
    (comp (ref "LX2") (value "磁珠 0欧姆") (footprint "1206") (libsource (lib "SCH原理图库") (part "L")))
    (comp (ref "LX3") (value "磁珠 0欧姆") (footprint "1206") (libsource (lib "SCH原理图库") (part "L")))
    (comp (ref "LX4") (value "磁珠 0欧姆") (footprint "1206") (libsource (lib "SCH原理图库") (part "L")))
    (comp (ref "LX5") (value "磁珠 0欧姆") (footprint "1206") (libsource (lib "SCH原理图库") (part "L")))
    (comp (ref "MK1")
      (value "220V转12V")
      (footprint "220V转5V 2A")
      (description "Header, 2-Pin, Dual row")
      (fields (field (name "PUBLISHER") "Altium Limited"))
      (libsource (lib "SCH原理图库") (part "Header 2X2"))
    )
    (comp (ref "NB-SW1")
      (value "Header 3")
      (footprint "HDR1X3")
      (description "Header, 3-Pin")
      (fields (field (name "PUBLISHER") "Altium Limited"))
      (libsource (lib "") (part "Header 3_2"))
    )
    (comp (ref "P0")
      (value "Header 10")
      (footprint "HDR1X10")
      (description "Header, 10-Pin")
      (fields (field (name "PUBLISHER") "Altium Limited"))
      (libsource (lib "SCH原理图库") (part "Header 10"))
    )
    (comp (ref "P1")
      (value "~")
      (footprint "HDR1X2")
      (description "Header, 2-Pin")
      (libsource (lib "Miscellaneous Connectors") (part "Header 2"))
    )
    (comp (ref "P2")
      (value "6.35-12P")
      (footprint "6.35-12P")
      (description "Header, 12-Pin")
      (libsource (lib "SCH原理图库") (part "Header 12"))
    )
    (comp (ref "P3")
      (value "6.35-12P")
      (footprint "6.35-12P")
      (description "Header, 12-Pin")
      (libsource (lib "SCH原理图库") (part "Header 12"))
    )
    (comp (ref "P4")
      (value "Header 10")
      (footprint "HDR1X10")
      (description "Header, 10-Pin")
      (libsource (lib "") (part "Header 10_1"))
    )
    (comp (ref "PJP1")
      (value "3.96-4P")
      (footprint "3.96-4P")
      (description "Header, 4-Pin")
      (libsource (lib "") (part "Header 4_1"))
    )
    (comp (ref "PT2")
      (value "2.54-1*2")
      (footprint "HDR1X2")
      (description "Header, 2-Pin")
      (fields (field (name "PUBLISHER") "Altium Limited"))
      (libsource (lib "SCH原理图库") (part "Header 2"))
    )
    (comp (ref "PT3")
      (value "2.54-1*2")
      (footprint "HDR1X2")
      (description "Header, 2-Pin")
      (fields (field (name "PUBLISHER") "Altium Limited"))
      (libsource (lib "SCH原理图库") (part "Header 2"))
    )
    (comp (ref "PT4")
      (value "2.54-1*2")
      (footprint "HDR1X2")
      (description "Header, 2-Pin")
      (fields (field (name "PUBLISHER") "Altium Limited"))
      (libsource (lib "SCH原理图库") (part "Header 2"))
    )
    (comp (ref "PT5")
      (value "2.54-1*2")
      (footprint "HDR1X2")
      (description "Header, 2-Pin")
      (fields (field (name "PUBLISHER") "Altium Limited"))
      (libsource (lib "SCH原理图库") (part "Header 2"))
    )
    (comp (ref "PT6")
      (value "2.54-1*2")
      (footprint "HDR1X2")
      (description "Header, 2-Pin")
      (fields (field (name "PUBLISHER") "Altium Limited"))
      (libsource (lib "SCH原理图库") (part "Header 2"))
    )
    (comp (ref "QK1")
      (value "NPN-S8050")
      (footprint "NPN-SOT3")
      (description "NPN Bipolar Transistor")
      (fields (field (name "PUBLISHER") "Altium Limited"))
      (libsource (lib "原理图库") (part "NPN"))
    )
    (comp (ref "QK2")
      (value "NPN-S8050")
      (footprint "NPN-SOT3")
      (description "NPN Bipolar Transistor")
      (fields (field (name "PUBLISHER") "Altium Limited"))
      (libsource (lib "原理图库") (part "NPN"))
    )
    (comp (ref "QK3")
      (value "NPN-S8050")
      (footprint "NPN-SOT3")
      (description "NPN Bipolar Transistor")
      (fields (field (name "PUBLISHER") "Altium Limited"))
      (libsource (lib "原理图库") (part "NPN"))
    )
    (comp (ref "QK4")
      (value "NPN-S8050")
      (footprint "NPN-SOT3")
      (description "NPN Bipolar Transistor")
      (fields (field (name "PUBLISHER") "Altium Limited"))
      (libsource (lib "原理图库") (part "NPN"))
    )
    (comp (ref "QK5")
      (value "NPN-S8050")
      (footprint "NPN-SOT3")
      (description "NPN Bipolar Transistor")
      (fields (field (name "PUBLISHER") "Altium Limited"))
      (libsource (lib "原理图库") (part "NPN"))
    )
    (comp (ref "QK6")
      (value "NPN-S8050")
      (footprint "NPN-SOT3")
      (description "NPN Bipolar Transistor")
      (fields (field (name "PUBLISHER") "Altium Limited"))
      (libsource (lib "原理图库") (part "NPN"))
    )
    (comp (ref "QK7")
      (value "NPN-S8050")
      (footprint "NPN-SOT3")
      (description "NPN Bipolar Transistor")
      (fields (field (name "PUBLISHER") "Altium Limited"))
      (libsource (lib "原理图库") (part "NPN"))
    )
    (comp (ref "QK8")
      (value "NPN-S8050")
      (footprint "NPN-SOT3")
      (description "NPN Bipolar Transistor")
      (fields (field (name "PUBLISHER") "Altium Limited"))
      (libsource (lib "原理图库") (part "NPN"))
    )
    (comp (ref "QK9")
      (value "NPN-S8050")
      (footprint "NPN-SOT3")
      (description "NPN Bipolar Transistor")
      (fields (field (name "PUBLISHER") "Altium Limited"))
      (libsource (lib "原理图库") (part "NPN"))
    )
    (comp (ref "QK10")
      (value "NPN-S8050")
      (footprint "NPN-SOT3")
      (description "NPN Bipolar Transistor")
      (fields (field (name "PUBLISHER") "Altium Limited"))
      (libsource (lib "原理图库") (part "NPN"))
    )
    (comp (ref "QK11")
      (value "NPN-S8050")
      (footprint "NPN-SOT3")
      (description "NPN Bipolar Transistor")
      (fields (field (name "PUBLISHER") "Altium Limited"))
      (libsource (lib "原理图库") (part "NPN"))
    )
    (comp (ref "QK12")
      (value "NPN")
      (footprint "NPN-SOT3")
      (description "NPN Bipolar Transistor")
      (fields (field (name "PUBLISHER") "Altium Limited"))
      (libsource (lib "原理图库") (part "NPN"))
    )
    (comp (ref "QK13")
      (value "NPN")
      (footprint "NPN-SOT3")
      (description "NPN Bipolar Transistor")
      (fields (field (name "PUBLISHER") "Altium Limited"))
      (libsource (lib "原理图库") (part "NPN"))
    )
    (comp (ref "QK14")
      (value "NPN")
      (footprint "NPN-SOT3")
      (description "NPN Bipolar Transistor")
      (fields (field (name "PUBLISHER") "Altium Limited"))
      (libsource (lib "原理图库") (part "NPN"))
    )
    (comp (ref "R1") (value "120") (footprint "0603-1") (libsource (lib "*") (part "R1005_0")))
    (comp (ref "R2")
      (value "10K")
      (footprint "0603-1")
      (description "Resistor")
      (fields (field (name "PUBLISHER") "Altium Limited"))
      (libsource (lib "*") (part "Res2"))
    )
    (comp (ref "R3")
      (value "10K")
      (footprint "0603-1")
      (description "Resistor")
      (fields (field (name "PUBLISHER") "Altium Limited"))
      (libsource (lib "*") (part "Res2"))
    )
    (comp (ref "R4")
      (value "10K")
      (footprint "0603-1")
      (description "Resistor")
      (fields (field (name "PUBLISHER") "Altium Limited"))
      (libsource (lib "*") (part "Res2"))
    )
    (comp (ref "R5")
      (value "10K/NC")
      (footprint "0603-1")
      (description "RES FILM;10K;+/-5%;1/16W;0402;0.4mm;ROHS")
      (libsource (lib "*") (part "RES-10K-0402"))
    )
    (comp (ref "R6") (value "10K") (footprint "0603-1") (libsource (lib "*") (part "RES-510-0402")))
    (comp (ref "RA1")
      (value "10K")
      (footprint "0603-1")
      (description "Resistor")
      (libsource (lib "") (part "Res2_1"))
    )
    (comp (ref "RA2")
      (value "10K")
      (footprint "0603-1")
      (description "Resistor")
      (libsource (lib "") (part "Res2_1"))
    )
    (comp (ref "RA3")
      (value "10K")
      (footprint "0603-1")
      (description "Resistor")
      (libsource (lib "") (part "Res2_1"))
    )
    (comp (ref "RA4")
      (value "10K")
      (footprint "0603-1")
      (description "Resistor")
      (libsource (lib "") (part "Res2_1"))
    )
    (comp (ref "RA5")
      (value "10K")
      (footprint "0603-1")
      (description "Resistor")
      (libsource (lib "") (part "Res2_1"))
    )
    (comp (ref "RA6") (value "10K") (footprint "0603-1") (libsource (lib "*") (part "R")))
    (comp (ref "RA7") (value "22R") (footprint "0603-1") (libsource (lib "*") (part "R_Dup2")))
    (comp (ref "RA8") (value "22R") (footprint "0603-1") (libsource (lib "*") (part "R_Dup2")))
    (comp (ref "RA9") (value "22R") (footprint "0603-1") (libsource (lib "*") (part "R_Dup2")))
    (comp (ref "RD1")
      (value "10K")
      (footprint "0603-1")
      (description "Resistor")
      (fields (field (name "PUBLISHER") "Altium Limited"))
      (libsource (lib "") (part "Res2_3"))
    )
    (comp (ref "RE1")
      (value "1K")
      (footprint "0603-1")
      (description "Resistor")
      (libsource (lib "") (part "Res2_2"))
    )
    (comp (ref "RE2")
      (value "80")
      (footprint "0603-1")
      (description "Resistor")
      (libsource (lib "") (part "Res2_2"))
    )
    (comp (ref "RE3")
      (value "1K")
      (footprint "0603-1")
      (description "Resistor")
      (libsource (lib "") (part "Res2_2"))
    )
    (comp (ref "RE4")
      (value "80")
      (footprint "0603-1")
      (description "Resistor")
      (libsource (lib "") (part "Res2_2"))
    )
    (comp (ref "RE5")
      (value "1K")
      (footprint "0603-1")
      (description "Resistor")
      (libsource (lib "") (part "Res2_2"))
    )
    (comp (ref "RE6")
      (value "80")
      (footprint "0603-1")
      (description "Resistor")
      (libsource (lib "") (part "Res2_2"))
    )
    (comp (ref "RE7")
      (value "1K")
      (footprint "0603-1")
      (description "Resistor")
      (libsource (lib "") (part "Res2_2"))
    )
    (comp (ref "RE8")
      (value "80")
      (footprint "0603-1")
      (description "Resistor")
      (libsource (lib "") (part "Res2_2"))
    )
    (comp (ref "RE9")
      (value "1K")
      (footprint "0603-1")
      (description "Resistor")
      (libsource (lib "") (part "Res2_2"))
    )
    (comp (ref "RE10")
      (value "80")
      (footprint "0603-1")
      (description "Resistor")
      (libsource (lib "") (part "Res2_2"))
    )
    (comp (ref "RF1")
      (value "1K")
      (footprint "0603-1")
      (description "Resistor")
      (libsource (lib "") (part "Res2_3"))
    )
    (comp (ref "RF2")
      (value "1K")
      (footprint "0603-1")
      (description "Resistor")
      (libsource (lib "") (part "Res2_3"))
    )
    (comp (ref "RF3")
      (value "1K")
      (footprint "0603-1")
      (description "Resistor")
      (libsource (lib "") (part "Res2_3"))
    )
    (comp (ref "RF4")
      (value "1K")
      (footprint "0603-1")
      (description "Resistor")
      (libsource (lib "") (part "Res2_3"))
    )
    (comp (ref "RF5")
      (value "1K")
      (footprint "0603-1")
      (description "Resistor")
      (libsource (lib "") (part "Res2_3"))
    )
    (comp (ref "RG1")
      (value "10K")
      (footprint "0603-1")
      (description "Resistor")
      (libsource (lib "Miscellaneous Devices") (part "Res1"))
    )
    (comp (ref "RG2")
      (value "10K")
      (footprint "0603-1")
      (description "Resistor")
      (libsource (lib "Miscellaneous Devices") (part "Res1"))
    )
    (comp (ref "RG3")
      (value "10K")
      (footprint "0603-1")
      (description "Resistor")
      (libsource (lib "Miscellaneous Devices") (part "Res1"))
    )
    (comp (ref "RH1") (value "1K") (footprint "0603-1") (libsource (lib "*") (part "RES2")))
    (comp (ref "RH2") (value "1K") (footprint "0603-1") (libsource (lib "*") (part "RES2")))
    (comp (ref "RH3") (value "1K") (footprint "0603-1") (libsource (lib "*") (part "RES2")))
    (comp (ref "RH4") (value "1K") (footprint "0603-1") (libsource (lib "*") (part "RES2")))
    (comp (ref "RH5") (value "1K") (footprint "0603-1") (libsource (lib "*") (part "RES2")))
    (comp (ref "RH6") (value "1K") (footprint "0603-1") (libsource (lib "*") (part "RES2")))
    (comp (ref "RH7") (value "1K") (footprint "0603-1") (libsource (lib "*") (part "RES2")))
    (comp (ref "RH8") (value "1K") (footprint "0603-1") (libsource (lib "*") (part "RES2")))
    (comp (ref "RH9") (value "1K") (footprint "0603-1") (libsource (lib "*") (part "RES2")))
    (comp (ref "RH10") (value "1K") (footprint "0603-1") (libsource (lib "*") (part "RES2")))
    (comp (ref "RH11") (value "1K") (footprint "0603-1") (libsource (lib "*") (part "RES2")))
    (comp (ref "RH12") (value "1K") (footprint "0603-1") (libsource (lib "*") (part "RES2")))
    (comp (ref "RH13") (value "1K") (footprint "0603-1") (libsource (lib "*") (part "RES2")))
    (comp (ref "RH14") (value "1K") (footprint "0603-1") (libsource (lib "*") (part "RES2")))
    (comp (ref "RH15") (value "1K") (footprint "0603-1") (libsource (lib "*") (part "RES2")))
    (comp (ref "RH16") (value "1K") (footprint "0603-1") (libsource (lib "*") (part "RES2")))
    (comp (ref "RH17") (value "1K") (footprint "0603-1") (libsource (lib "*") (part "RES2")))
    (comp (ref "RH18") (value "1K") (footprint "0603-1") (libsource (lib "*") (part "RES2")))
    (comp (ref "RH19") (value "1K") (footprint "0603-1") (libsource (lib "*") (part "RES2")))
    (comp (ref "RH20") (value "1K") (footprint "0603-1") (libsource (lib "*") (part "RES2")))
    (comp (ref "RH21") (value "1K") (footprint "0603-1") (libsource (lib "*") (part "RES2")))
    (comp (ref "RH22") (value "1K") (footprint "0603-1") (libsource (lib "*") (part "RES2")))
    (comp (ref "RH23") (value "1K") (footprint "0603-1") (libsource (lib "*") (part "RES2")))
    (comp (ref "RH24") (value "1K") (footprint "0603-1") (libsource (lib "*") (part "RES2")))
    (comp (ref "RH25") (value "1K") (footprint "0603-1") (libsource (lib "*") (part "RES2")))
    (comp (ref "RH26") (value "1K") (footprint "0603-1") (libsource (lib "*") (part "RES2")))
    (comp (ref "RH27") (value "1K") (footprint "0603-1") (libsource (lib "*") (part "RES2")))
    (comp (ref "RH28") (value "1K") (footprint "0603-1") (libsource (lib "*") (part "RES2")))
    (comp (ref "RH29") (value "1K") (footprint "0603-1") (libsource (lib "*") (part "RES2")))
    (comp (ref "RH30") (value "1K") (footprint "0603-1") (libsource (lib "*") (part "RES2")))
    (comp (ref "RH31") (value "1K") (footprint "0603-1") (libsource (lib "*") (part "RES2")))
    (comp (ref "RH32") (value "1K") (footprint "0603-1") (libsource (lib "*") (part "RES2")))
    (comp (ref "RH33") (value "1K") (footprint "0603-1") (libsource (lib "*") (part "RES2")))
    (comp (ref "RH34") (value "1K") (footprint "0603-1") (libsource (lib "*") (part "RES2")))
    (comp (ref "RH35") (value "1K") (footprint "0603-1") (libsource (lib "*") (part "RES2")))
    (comp (ref "RH36") (value "1K") (footprint "0603-1") (libsource (lib "*") (part "RES2")))
    (comp (ref "RH37") (value "1K") (footprint "0603-1") (libsource (lib "*") (part "RES2")))
    (comp (ref "RH38") (value "1K") (footprint "0603-1") (libsource (lib "*") (part "RES2")))
    (comp (ref "RH39") (value "1K") (footprint "0603-1") (libsource (lib "*") (part "RES2")))
    (comp (ref "RH40") (value "1K") (footprint "0603-1") (libsource (lib "*") (part "RES2")))
    (comp (ref "RH41") (value "1K") (footprint "0603-1") (libsource (lib "*") (part "RES2")))
    (comp (ref "RH42") (value "1K") (footprint "0603-1") (libsource (lib "*") (part "RES2")))
    (comp (ref "RH43") (value "1K") (footprint "0603-1") (libsource (lib "*") (part "RES2")))
    (comp (ref "RH44") (value "1K") (footprint "0603-1") (libsource (lib "*") (part "RES2")))
    (comp (ref "RI1") (value "10K") (footprint "0603-1") (libsource (lib "*") (part "RES2")))
    (comp (ref "RI2") (value "10K") (footprint "0603-1") (libsource (lib "*") (part "RES2")))
    (comp (ref "RI3") (value "10K") (footprint "0603-1") (libsource (lib "*") (part "RES2")))
    (comp (ref "RI4") (value "10K") (footprint "0603-1") (libsource (lib "*") (part "RES2")))
    (comp (ref "RI5") (value "10K") (footprint "0603-1") (libsource (lib "*") (part "RES2")))
    (comp (ref "RI6") (value "10K") (footprint "0603-1") (libsource (lib "*") (part "RES2")))
    (comp (ref "RI7") (value "10K") (footprint "0603-1") (libsource (lib "*") (part "RES2")))
    (comp (ref "RI8") (value "10K") (footprint "0603-1") (libsource (lib "*") (part "RES2")))
    (comp (ref "RI9") (value "10K") (footprint "0603-1") (libsource (lib "*") (part "RES2")))
    (comp (ref "RI10") (value "10K") (footprint "0603-1") (libsource (lib "*") (part "RES2")))
    (comp (ref "RI11") (value "10K") (footprint "0603-1") (libsource (lib "*") (part "RES2")))
    (comp (ref "RI12") (value "10K") (footprint "0603-1") (libsource (lib "*") (part "RES2")))
    (comp (ref "RI13") (value "10K") (footprint "0603-1") (libsource (lib "*") (part "RES2")))
    (comp (ref "RI14") (value "10K") (footprint "0603-1") (libsource (lib "*") (part "RES2")))
    (comp (ref "RJ1") (value "10K") (footprint "0603-1") (libsource (lib "*") (part "RES2")))
    (comp (ref "RJ2") (value "10K") (footprint "0603-1") (libsource (lib "*") (part "RES2")))
    (comp (ref "RJ3") (value "10K") (footprint "0603-1") (libsource (lib "*") (part "RES2")))
    (comp (ref "RJ4") (value "10K") (footprint "0603-1") (libsource (lib "*") (part "RES2")))
    (comp (ref "RJ5") (value "10K") (footprint "0603-1") (libsource (lib "*") (part "RES2")))
    (comp (ref "RJ6") (value "10") (footprint "0603-1") (libsource (lib "*") (part "RES2")))
    (comp (ref "RJ7") (value "10K") (footprint "0603-1") (libsource (lib "*") (part "RES2")))
    (comp (ref "RJ8") (value "10K") (footprint "0603-1") (libsource (lib "*") (part "RES2")))
    (comp (ref "RJ9") (value "10K") (footprint "0603-1") (libsource (lib "*") (part "RES2")))
    (comp (ref "RJ10") (value "10K") (footprint "0603-1") (libsource (lib "*") (part "RES2")))
    (comp (ref "RJ11") (value "10K") (footprint "0603-1") (libsource (lib "*") (part "RES2")))
    (comp (ref "RJ12") (value "10K") (footprint "0603-1") (libsource (lib "*") (part "RES2")))
    (comp (ref "RJ13") (value "10K") (footprint "0603-1") (libsource (lib "*") (part "RES2")))
    (comp (ref "RJ14") (value "10K") (footprint "0603-1") (libsource (lib "*") (part "RES2")))
    (comp (ref "RJ15") (value "10K") (footprint "0603-1") (libsource (lib "*") (part "RES2")))
    (comp (ref "RJ16") (value "10K") (footprint "0603-1") (libsource (lib "*") (part "RES2")))
    (comp (ref "RJ17") (value "10K") (footprint "0603-1") (libsource (lib "*") (part "RES2")))
    (comp (ref "RJ18") (value "10K") (footprint "0603-1") (libsource (lib "*") (part "RES2")))
    (comp (ref "RJ19") (value "10K") (footprint "0603-1") (libsource (lib "*") (part "RES2")))
    (comp (ref "RK1")
      (value "10K")
      (footprint "0603-1")
      (description "Resistor")
      (libsource (lib "") (part "Res2_2"))
    )
    (comp (ref "RK2")
      (value "10K")
      (footprint "0603-1")
      (description "Resistor")
      (libsource (lib "") (part "Res2_2"))
    )
    (comp (ref "RK3")
      (value "10K")
      (footprint "0603-1")
      (description "Resistor")
      (libsource (lib "") (part "Res2_2"))
    )
    (comp (ref "RK4")
      (value "10K")
      (footprint "0603-1")
      (description "Resistor")
      (libsource (lib "") (part "Res2_2"))
    )
    (comp (ref "RK5")
      (value "10K")
      (footprint "0603-1")
      (description "Resistor")
      (libsource (lib "") (part "Res2_2"))
    )
    (comp (ref "RL1")
      (value "10K")
      (footprint "0603-1")
      (description "Resistor")
      (libsource (lib "") (part "Res2_2"))
    )
    (comp (ref "RL2")
      (value "10K")
      (footprint "0603-1")
      (description "Resistor")
      (libsource (lib "") (part "Res2_2"))
    )
    (comp (ref "RL3")
      (value "10K")
      (footprint "0603-1")
      (description "Resistor")
      (libsource (lib "") (part "Res2_2"))
    )
    (comp (ref "RL4")
      (value "10K")
      (footprint "0603-1")
      (description "Resistor")
      (libsource (lib "") (part "Res2_2"))
    )
    (comp (ref "RL5")
      (value "10K")
      (footprint "0603-1")
      (description "Resistor")
      (libsource (lib "") (part "Res2_2"))
    )
    (comp (ref "RN1")
      (value "100K")
      (footprint "0603-1")
      (description "Resistor")
      (libsource (lib "Miscellaneous Devices") (part "Res2"))
    )
    (comp (ref "RN2")
      (value "100K")
      (footprint "0603-1")
      (description "Resistor")
      (libsource (lib "Miscellaneous Devices") (part "Res2"))
    )
    (comp (ref "RN3")
      (value "100K")
      (footprint "0603-1")
      (description "Resistor")
      (libsource (lib "Miscellaneous Devices") (part "Res2"))
    )
    (comp (ref "RN4")
      (value "100K")
      (footprint "0603-1")
      (description "Resistor")
      (libsource (lib "Miscellaneous Devices") (part "Res2"))
    )
    (comp (ref "RN5")
      (value "100K")
      (footprint "0603-1")
      (description "Resistor")
      (libsource (lib "Miscellaneous Devices") (part "Res2"))
    )
    (comp (ref "RO1")
      (value "10K")
      (footprint "0603-1")
      (description "Resistor")
      (libsource (lib "") (part "Res2_1"))
    )
    (comp (ref "RO2")
      (value "10K")
      (footprint "0603-1")
      (description "Resistor")
      (libsource (lib "") (part "Res2_1"))
    )
    (comp (ref "RO3")
      (value "10K")
      (footprint "0603-1")
      (description "Resistor")
      (libsource (lib "") (part "Res2_1"))
    )
    (comp (ref "RO4")
      (value "10K")
      (footprint "0603-1")
      (description "Resistor")
      (libsource (lib "") (part "Res2_1"))
    )
    (comp (ref "RO5")
      (value "10K")
      (footprint "0603-1")
      (description "Resistor")
      (libsource (lib "") (part "Res2_1"))
    )
    (comp (ref "RO6")
      (value "10K")
      (footprint "0603-1")
      (description "Resistor")
      (libsource (lib "") (part "Res2_1"))
    )
    (comp (ref "RQ1")
      (value "2.5K")
      (footprint "0603-1")
      (description "Resistor")
      (libsource (lib "") (part "Res2_2"))
    )
    (comp (ref "RQ2")
      (value "2.5K")
      (footprint "0603-1")
      (description "Resistor")
      (libsource (lib "") (part "Res2_2"))
    )
    (comp (ref "RQ3")
      (value "2.5K")
      (footprint "0603-1")
      (description "Resistor")
      (libsource (lib "") (part "Res2_2"))
    )
    (comp (ref "RQ4")
      (value "2.5K")
      (footprint "0603-1")
      (description "Resistor")
      (libsource (lib "") (part "Res2_2"))
    )
    (comp (ref "RQ5")
      (value "2.5K")
      (footprint "0603-1")
      (description "Resistor")
      (libsource (lib "") (part "Res2_2"))
    )
    (comp (ref "RR1")
      (value "10k")
      (footprint "0603-1")
      (description "RES FILM;1K;+/-5%;1/16W;0402;0.4mm;ROHS")
      (libsource (lib "*") (part "RES-1K-0402"))
    )
    (comp (ref "RT1")
      (value "1K")
      (footprint "0603-1")
      (description "Resistor")
      (libsource (lib "") (part "Res2_1"))
    )
    (comp (ref "RT2")
      (value "1K")
      (footprint "0603-1")
      (description "Resistor")
      (libsource (lib "") (part "Res2_1"))
    )
    (comp (ref "RT3")
      (value "1K")
      (footprint "0603-1")
      (description "Resistor")
      (libsource (lib "") (part "Res2_1"))
    )
    (comp (ref "RT4")
      (value "1K")
      (footprint "0603-1")
      (description "Resistor")
      (libsource (lib "") (part "Res2_1"))
    )
    (comp (ref "RT5")
      (value "1K")
      (footprint "0603-1")
      (description "Resistor")
      (libsource (lib "") (part "Res2_1"))
    )
    (comp (ref "RU1")
      (value "10k")
      (footprint "0603-1")
      (description "Resistor")
      (fields (field (name "PUBLISHER") "Altium Limited"))
      (libsource (lib "Miscellaneous Devices") (part "Res2"))
    )
    (comp (ref "RU2")
      (value "10k")
      (footprint "0603-1")
      (description "Resistor")
      (libsource (lib "Miscellaneous Devices") (part "Res2"))
    )
    (comp (ref "RU3")
      (value "10k")
      (footprint "0603-1")
      (description "Resistor")
      (libsource (lib "") (part "Res2_3"))
    )
    (comp (ref "RU4")
      (value "10k")
      (footprint "0603-1")
      (description "Resistor")
      (fields (field (name "PUBLISHER") "Altium Limited"))
      (libsource (lib "") (part "Res2_3"))
    )
    (comp (ref "RV1")
      (value "10K")
      (footprint "0603-1")
      (description "Resistor")
      (fields (field (name "PUBLISHER") "Altium Limited"))
      (libsource (lib "Miscellaneous Devices") (part "Res2"))
    )
    (comp (ref "RV2")
      (value "10K")
      (footprint "0603-1")
      (description "Resistor")
      (fields (field (name "PUBLISHER") "Altium Limited"))
      (libsource (lib "Miscellaneous Devices") (part "Res2"))
    )
    (comp (ref "RW1")
      (value "2.5K")
      (footprint "0603-1")
      (description "Resistor")
      (libsource (lib "") (part "Res2_2"))
    )
    (comp (ref "RW2")
      (value "2.5K")
      (footprint "0603-1")
      (description "Resistor")
      (libsource (lib "") (part "Res2_2"))
    )
    (comp (ref "RW3")
      (value "2.5K")
      (footprint "0603-1")
      (description "Resistor")
      (libsource (lib "") (part "Res2_2"))
    )
    (comp (ref "RW4")
      (value "2.5K")
      (footprint "0603-1")
      (description "Resistor")
      (libsource (lib "") (part "Res2_2"))
    )
    (comp (ref "RW5")
      (value "2.5K")
      (footprint "0603-1")
      (description "Resistor")
      (libsource (lib "") (part "Res2_2"))
    )
    (comp (ref "RY1")
      (value "1K")
      (footprint "0603-1")
      (description "Resistor")
      (libsource (lib "") (part "Res2_1"))
    )
    (comp (ref "RY2")
      (value "1K")
      (footprint "0603-1")
      (description "Resistor")
      (libsource (lib "") (part "Res2_1"))
    )
    (comp (ref "RY3")
      (value "1K")
      (footprint "0603-1")
      (description "Resistor")
      (libsource (lib "") (part "Res2_1"))
    )
    (comp (ref "RY4")
      (value "1K")
      (footprint "0603-1")
      (description "Resistor")
      (libsource (lib "") (part "Res2_1"))
    )
    (comp (ref "RY5")
      (value "1K")
      (footprint "0603-1")
      (description "Resistor")
      (libsource (lib "") (part "Res2_1"))
    )
    (comp (ref "RZ1")
      (value "10K")
      (footprint "0603-1")
      (description "Resistor")
      (fields (field (name "PUBLISHER") "Altium Limited"))
      (libsource (lib "") (part "Res2_2"))
    )
    (comp (ref "RZ2")
      (value "10K")
      (footprint "0603-1")
      (description "Resistor")
      (fields (field (name "PUBLISHER") "Altium Limited"))
      (libsource (lib "Miscellaneous Devices") (part "Res2"))
    )
    (comp (ref "RZ3")
      (value "10K")
      (footprint "0603-1")
      (description "Resistor")
      (fields (field (name "PUBLISHER") "Altium Limited"))
      (libsource (lib "Miscellaneous Devices") (part "Res2"))
    )
    (comp (ref "S1")
      (value "SW-PB")
      (footprint "SW_2 - SMT")
      (description "Switch")
      (fields (field (name "PUBLISHER") "Altium Limited"))
      (libsource (lib "SCH原理图库") (part "SW-PB"))
    )
    (comp (ref "SMA1")
      (value "IPEX")
      (footprint "IPEX 接头")
      (description "Header, 2-Pin")
      (fields (field (name "PUBLISHER") "Altium Limited"))
      (libsource (lib "") (part "Header 2_1"))
    )
    (comp (ref "ST-LINK1")
      (value "Header 5")
      (footprint "HDR1X5")
      (description "Header, 5-Pin")
      (fields (field (name "PUBLISHER") "Altium Limited"))
      (libsource (lib "原理图库") (part "Header 5"))
    )
    (comp (ref "TCL1")
      (value "TLC5615IDR")
      (footprint "SOP-8")
      (libsource (lib "SCH原理图库") (part "TLC5615IDR"))
    )
    (comp (ref "TCL2")
      (value "TLC5615IDR")
      (footprint "SOP-8")
      (libsource (lib "SCH原理图库") (part "TLC5615IDR"))
    )
    (comp (ref "TCL3")
      (value "TLC5615IDR")
      (footprint "SOP-8")
      (libsource (lib "SCH原理图库") (part "TLC5615IDR"))
    )
    (comp (ref "TCL4")
      (value "TLC5615IDR")
      (footprint "SOP-8")
      (libsource (lib "SCH原理图库") (part "TLC5615IDR"))
    )
    (comp (ref "TCL5")
      (value "TLC5615IDR")
      (footprint "SOP-8")
      (libsource (lib "SCH原理图库") (part "TLC5615IDR"))
    )
    (comp (ref "TTL-SW1")
      (value "0603-SW")
      (footprint "HDR1X3")
      (description "Header, 3-Pin")
      (fields (field (name "PUBLISHER") "Altium Limited"))
      (libsource (lib "") (part "Header 3_1"))
    )
    (comp (ref "TTL1")
      (value "Header 4")
      (footprint "HDR1X4")
      (description "Header, 4-Pin")
      (fields (field (name "PUBLISHER") "Altium Limited"))
      (libsource (lib "SCH原理图库") (part "Header 4"))
    )
    (comp (ref "TTL2")
      (value "Header 3X2")
      (footprint "HDR2X3")
      (description "Header, 3-Pin, Dual row")
      (fields (field (name "PUBLISHER") "Altium Limited"))
      (libsource (lib "SCH原理图库") (part "Header 3X2"))
    )
    (comp (ref "TVS1")
      (value "~")
      (footprint "DIODE")
      (description "Schottky Rectifier")
      (fields (field (name "PUBLISHER") "*"))
      (libsource (lib "*") (part "Diode 10TQ035"))
    )
    (comp (ref "TVS2")
      (value "~")
      (footprint "DIODE")
      (description "Schottky Rectifier")
      (fields (field (name "PUBLISHER") "*"))
      (libsource (lib "*") (part "Diode 10TQ035"))
    )
    (comp (ref "U1") (value "SN65HVD3082") (footprint "SOP-8P") (libsource (lib "*") (part "SN65HVD3082")))
    (comp (ref "U2")
      (value "1117-3.3")
      (footprint "SOT223")
      (description "800mA and 1A Low Dropout Positive Regulator 2.85V, 3.3V, 5V, and Adjustable")
      (fields (field (name "PUBLISHER") "Altium Limited"))
      (libsource (lib "CommonLib") (part "1117-3.3"))
    )
    (comp (ref "U3")
      (value "1117-5V")
      (footprint "SOT223")
      (description "800mA and 1A Low Dropout Positive Regulator 2.85V, 3.3V, 5V, and Adjustable")
      (libsource (lib "CommonLib") (part "1117-3.3"))
    )
    (comp (ref "U4")
      (value "1117-2.5V")
      (footprint "SOT223")
      (description "800mA and 1A Low Dropout Positive Regulator 2.85V, 3.3V, 5V, and Adjustable")
      (libsource (lib "CommonLib") (part "1117-3.3"))
    )
    (comp (ref "U5")
      (value "1117-5V")
      (footprint "SOT223")
      (description "800mA and 1A Low Dropout Positive Regulator 2.85V, 3.3V, 5V, and Adjustable")
      (libsource (lib "CommonLib") (part "1117-3.3"))
    )
    (comp (ref "U6")
      (value "LM258N")
      (footprint "SOP-8")
      (description "Dual Low-Power Operational Amplifier")
      (libsource (lib "Motorola Amplifier Operational Amplifier") (part "LM258N"))
    )
    (comp (ref "U7")
      (value "LM258N")
      (footprint "SOP-8")
      (description "Dual Low-Power Operational Amplifier")
      (libsource (lib "Motorola Amplifier Operational Amplifier") (part "LM258N"))
    )
    (comp (ref "U8")
      (value "1117-5V")
      (footprint "SOT223")
      (description "800mA and 1A Low Dropout Positive Regulator 2.85V, 3.3V, 5V, and Adjustable")
      (libsource (lib "CommonLib") (part "1117-3.3"))
    )
    (comp (ref "U9")
      (value "LM258N")
      (footprint "SOP-8")
      (description "Dual Low-Power Operational Amplifier")
      (libsource (lib "Motorola Amplifier Operational Amplifier") (part "LM258N"))
    )
    (comp (ref "U10")
      (value "1117-3.3V")
      (footprint "SOT223")
      (description "800mA and 1A Low Dropout Positive Regulator 2.85V, 3.3V, 5V, and Adjustable")
      (libsource (lib "CommonLib") (part "1117-3.3"))
    )
    (comp (ref "UA1") (value "Air302") (footprint "AIR202") (libsource (lib "SCH原理图库") (part "Air302")))
    (comp (ref "UM1")
      (value "STM32F030C8T6")
      (footprint "LQFP48")
      (libsource (lib "SCH原理图库") (part "STM32F030C8T6"))
    )
    (comp (ref "VR1")
      (value "ESD-TVS-UM5079")
      (footprint "0603-1")
      (description "TVS;7V;65pf;SOD882;ROHS")
      (libsource (lib "*") (part "ESD-TVS-UM5079"))
    )
    (comp (ref "VR2")
      (value "ESD-TVS-UM5079")
      (footprint "0603-1")
      (description "TVS;7V;65pf;SOD882;ROHS")
      (libsource (lib "*") (part "ESD-TVS-UM5079"))
    )
    (comp (ref "VR3")
      (value "ESD-TVS-UM5079")
      (footprint "0603-1")
      (description "TVS;7V;65pf;SOD882;ROHS")
      (libsource (lib "*") (part "ESD-TVS-UM5079"))
    )
    (comp (ref "VR4")
      (value "ESD-TVS-UM5079")
      (footprint "0603-1")
      (description "TVS;7V;65pf;SOD882;ROHS")
      (libsource (lib "*") (part "ESD-TVS-UM5079"))
    )
    (comp (ref "VR5")
      (value "ESD-TVS-UM5079")
      (footprint "0603-1")
      (description "TVS;7V;65pf;SOD882;ROHS")
      (libsource (lib "*") (part "ESD-TVS-UM5079"))
    )
    (comp (ref "W1")
      (value "W5500 网口模块")
      (footprint "W5500 网口模块")
      (libsource (lib "SCH原理图库") (part "W5500 网口模块"))
    )
    (comp (ref "X1")
      (value "8MHz")
      (footprint "5032")
      (description "Crystal Oscillator")
      (fields (field (name "PUBLISHER") "Altium Limited"))
      (libsource (lib "MCD_TOOLS") (part "XTAL"))
    )
    (comp (ref "YM1")
      (value "470D")
      (footprint "压敏电阻")
      (description "Resistor")
      (libsource (lib "") (part "Res2_2"))
    )
  )
  (nets
    (net (code "1") (name "+5V") (class "Default")
      (node (ref "Cu8") (pin "1") (pinfunction "1_1") (pintype "passive"))
      (node (ref "Cu9") (pin "2") (pinfunction "2_2") (pintype "passive"))
      (node (ref "RQ1") (pin "2") (pinfunction "2_2") (pintype "passive"))
      (node (ref "RQ2") (pin "2") (pinfunction "2_2") (pintype "passive"))
      (node (ref "RQ3") (pin "2") (pinfunction "2_2") (pintype "passive"))
      (node (ref "RQ4") (pin "2") (pinfunction "2_2") (pintype "passive"))
      (node (ref "RQ5") (pin "2") (pinfunction "2_2") (pintype "passive"))
      (node (ref "RW1") (pin "2") (pinfunction "2_2") (pintype "passive"))
      (node (ref "RW2") (pin "2") (pinfunction "2_2") (pintype "passive"))
      (node (ref "RW3") (pin "2") (pinfunction "2_2") (pintype "passive"))
      (node (ref "RW4") (pin "2") (pinfunction "2_2") (pintype "passive"))
      (node (ref "RW5") (pin "2") (pinfunction "2_2") (pintype "passive"))
      (node (ref "TTL-SW1") (pin "3") (pinfunction "3_3") (pintype "passive"))
      (node (ref "U5") (pin "2") (pinfunction "OUT_2") (pintype "power_in"))
      (node (ref "U5") (pin "4") (pinfunction "OUT_4") (pintype "power_in"))
      (node (ref "U6") (pin "8") (pinfunction "V+_8") (pintype "power_in"))
      (node (ref "U7") (pin "8") (pinfunction "V+_8") (pintype "power_in"))
      (node (ref "U9") (pin "8") (pinfunction "V+_8") (pintype "power_in"))
      (node (ref "W1") (pin "9") (pinfunction "5V_9") (pintype "passive"))
    )
    (net (code "2") (name "+12V") (class "Default")
      (node (ref "1") (pin "3") (pinfunction "3_3") (pintype "passive"))
      (node (ref "2") (pin "3") (pinfunction "3_3") (pintype "passive"))
      (node (ref "3") (pin "3") (pinfunction "3_3") (pintype "passive"))
      (node (ref "4") (pin "3") (pinfunction "3_3") (pintype "passive"))
      (node (ref "5") (pin "3") (pinfunction "3_3") (pintype "passive"))
      (node (ref "CP1") (pin "1") (pinfunction "1_1") (pintype "passive"))
      (node (ref "CP10") (pin "2") (pinfunction "2_2") (pintype "passive"))
      (node (ref "CP11") (pin "1") (pinfunction "1_1") (pintype "passive"))
      (node (ref "CP12") (pin "2") (pinfunction "2_2") (pintype "passive"))
      (node (ref "CP2") (pin "2") (pinfunction "2_2") (pintype "passive"))
      (node (ref "CP3") (pin "1") (pinfunction "1_1") (pintype "passive"))
      (node (ref "CP4") (pin "1") (pinfunction "1_1") (pintype "passive"))
      (node (ref "CP5") (pin "2") (pinfunction "2_2") (pintype "passive"))
      (node (ref "CP6") (pin "2") (pinfunction "2_2") (pintype "passive"))
      (node (ref "CP7") (pin "1") (pinfunction "1_1") (pintype "passive"))
      (node (ref "CP8") (pin "2") (pinfunction "2_2") (pintype "passive"))
      (node (ref "CP9") (pin "1") (pinfunction "1_1") (pintype "passive"))
      (node (ref "DJ1") (pin "2") (pinfunction "K_2") (pintype "passive"))
      (node (ref "DJ10") (pin "2") (pinfunction "K_2") (pintype "passive"))
      (node (ref "DJ2") (pin "2") (pinfunction "K_2") (pintype "passive"))
      (node (ref "DJ3") (pin "2") (pinfunction "K_2") (pintype "passive"))
      (node (ref "DJ4") (pin "2") (pinfunction "K_2") (pintype "passive"))
      (node (ref "DJ5") (pin "2") (pinfunction "K_2") (pintype "passive"))
      (node (ref "DJ6") (pin "2") (pinfunction "K_2") (pintype "passive"))
      (node (ref "DJ7") (pin "2") (pinfunction "K_2") (pintype "passive"))
      (node (ref "DJ8") (pin "2") (pinfunction "K_2") (pintype "passive"))
      (node (ref "DJ9") (pin "2") (pinfunction "K_2") (pintype "passive"))
      (node (ref "DP1") (pin "1") (pintype "passive"))
      (node (ref "DP2") (pin "1") (pintype "passive"))
      (node (ref "DP3") (pin "1") (pintype "passive"))
      (node (ref "DZ1") (pin "2") (pintype "passive"))
      (node (ref "K1") (pin "4") (pinfunction "4_4") (pintype "passive"))
      (node (ref "K10") (pin "4") (pinfunction "4_4") (pintype "passive"))
      (node (ref "K2") (pin "4") (pinfunction "4_4") (pintype "passive"))
      (node (ref "K3") (pin "4") (pinfunction "4_4") (pintype "passive"))
      (node (ref "K4") (pin "4") (pinfunction "4_4") (pintype "passive"))
      (node (ref "K5") (pin "4") (pinfunction "4_4") (pintype "passive"))
      (node (ref "K6") (pin "4") (pinfunction "4_4") (pintype "passive"))
      (node (ref "K7") (pin "4") (pinfunction "4_4") (pintype "passive"))
      (node (ref "K8") (pin "4") (pinfunction "4_4") (pintype "passive"))
      (node (ref "K9") (pin "4") (pinfunction "4_4") (pintype "passive"))
      (node (ref "MK1") (pin "3") (pinfunction "3_3") (pintype "passive"))
      (node (ref "P1") (pin "1") (pinfunction "1_1") (pintype "passive"))
      (node (ref "RJ1") (pin "1") (pinfunction "1_1") (pintype "passive"))
      (node (ref "RJ10") (pin "1") (pinfunction "1_1") (pintype "passive"))
      (node (ref "RJ12") (pin "1") (pinfunction "1_1") (pintype "passive"))
      (node (ref "RJ13") (pin "1") (pinfunction "1_1") (pintype "passive"))
      (node (ref "RJ14") (pin "1") (pinfunction "1_1") (pintype "passive"))
      (node (ref "RJ16") (pin "1") (pinfunction "1_1") (pintype "passive"))
      (node (ref "RJ2") (pin "1") (pinfunction "1_1") (pintype "passive"))
      (node (ref "RJ3") (pin "1") (pinfunction "1_1") (pintype "passive"))
      (node (ref "RJ8") (pin "1") (pinfunction "1_1") (pintype "passive"))
      (node (ref "RJ9") (pin "1") (pinfunction "1_1") (pintype "passive"))
      (node (ref "U10") (pin "3") (pinfunction "IN_3") (pintype "power_in"))
      (node (ref "U2") (pin "3") (pinfunction "IN_3") (pintype "power_in"))
      (node (ref "U3") (pin "3") (pinfunction "IN_3") (pintype "power_in"))
      (node (ref "U4") (pin "3") (pinfunction "IN_3") (pintype "power_in"))
      (node (ref "U5") (pin "3") (pinfunction "IN_3") (pintype "power_in"))
      (node (ref "U8") (pin "3") (pinfunction "IN_3") (pintype "power_in"))
    )
    (net (code "4") (name "/220V-L") (class "Default")
      (node (ref "P2") (pin "1") (pinfunction "1_1") (pintype "passive"))
      (node (ref "P2") (pin "3") (pinfunction "3_3") (pintype "passive"))
      (node (ref "PJP1") (pin "1") (pinfunction "1_1") (pintype "passive"))
      (node (ref "PJP1") (pin "2") (pinfunction "2_2") (pintype "passive"))
    )
    (net (code "5") (name "/485-RE") (class "Default")
      (node (ref "RZ1") (pin "1") (pinfunction "1_1") (pintype "passive"))
      (node (ref "U1") (pin "2") (pinfunction "RE_2") (pintype "passive"))
      (node (ref "U1") (pin "3") (pinfunction "OE_3") (pintype "passive"))
      (node (ref "UM1") (pin "11") (pinfunction "PA1_11") (pintype "passive"))
    )
    (net (code "6") (name "/A1") (class "Default")
      (node (ref "JP1") (pin "3") (pinfunction "3_3") (pintype "passive"))
      (node (ref "R1") (pin "2") (pinfunction "2_2") (pintype "passive"))
      (node (ref "RZ3") (pin "1") (pinfunction "1_1") (pintype "passive"))
      (node (ref "TVS2") (pin "2") (pinfunction "K_2") (pintype "passive"))
      (node (ref "U1") (pin "6") (pinfunction "A_6") (pintype "passive"))
    )
    (net (code "7") (name "/ADC") (class "Default")
      (node (ref "UA1") (pin "14") (pinfunction "ADC0_14") (pintype "passive"))
    )
    (net (code "8") (name "/ADC_IN0") (class "Default")
      (node (ref "P4") (pin "8") (pinfunction "8_8") (pintype "passive"))
      (node (ref "UM1") (pin "10") (pinfunction "PA0_10") (pintype "passive"))
    )
    (net (code "9") (name "/ADC_IN4") (class "Default")
      (node (ref "RK5") (pin "1") (pinfunction "1_1") (pintype "passive"))
      (node (ref "RL5") (pin "2") (pinfunction "2_2") (pintype "passive"))
      (node (ref "UM1") (pin "14") (pinfunction "PA4_14") (pintype "passive"))
    )
    (net (code "10") (name "/ADC_IN5") (class "Default")
      (node (ref "RK4") (pin "1") (pinfunction "1_1") (pintype "passive"))
      (node (ref "RL4") (pin "2") (pinfunction "2_2") (pintype "passive"))
      (node (ref "UM1") (pin "15") (pinfunction "PA5/SPI1_SCK_15") (pintype "passive"))
    )
    (net (code "11") (name "/ADC_IN6") (class "Default")
      (node (ref "RK3") (pin "1") (pinfunction "1_1") (pintype "passive"))
      (node (ref "RL3") (pin "2") (pinfunction "2_2") (pintype "passive"))
      (node (ref "UM1") (pin "16") (pinfunction "PA6/SPI1_MISO_16") (pintype "passive"))
    )
    (net (code "12") (name "/ADC_IN7") (class "Default")
      (node (ref "RK2") (pin "1") (pinfunction "1_1") (pintype "passive"))
      (node (ref "RL2") (pin "2") (pinfunction "2_2") (pintype "passive"))
      (node (ref "UM1") (pin "17") (pinfunction "PA7/SPI1_MOSI_17") (pintype "passive"))
    )
    (net (code "13") (name "/ADC_IN8") (class "Default")
      (node (ref "RK1") (pin "1") (pinfunction "1_1") (pintype "passive"))
      (node (ref "RL1") (pin "2") (pinfunction "2_2") (pintype "passive"))
      (node (ref "UM1") (pin "18") (pinfunction "PB0_18") (pintype "passive"))
    )
    (net (code "15") (name "/B1") (class "Default")
      (node (ref "JP1") (pin "2") (pinfunction "2_2") (pintype "passive"))
      (node (ref "R1") (pin "1") (pinfunction "1_1") (pintype "passive"))
      (node (ref "RZ2") (pin "2") (pinfunction "2_2") (pintype "passive"))
      (node (ref "TVS1") (pin "2") (pinfunction "K_2") (pintype "passive"))
      (node (ref "U1") (pin "7") (pinfunction "B_7") (pintype "passive"))
    )
    (net (code "16") (name "/BB_RESET") (class "Default")
      (node (ref "CS1") (pin "1") (pinfunction "1_1") (pintype "passive"))
      (node (ref "QK12") (pin "1") (pinfunction "C_1") (pintype "passive"))
      (node (ref "UA1") (pin "34") (pinfunction "RESET_34") (pintype "passive"))
    )
    (net (code "17") (name "/BOOT0") (class "Default")
      (node (ref "RU2") (pin "2") (pinfunction "2_2") (pintype "passive"))
      (node (ref "UM1") (pin "44") (pinfunction "BOOT0_44") (pintype "passive"))
    )
    (net (code "19") (name "/CE") (class "Default")
      (node (ref "UA1") (pin "7") (pinfunction "GPIO7_7") (pintype "passive"))
    )
    (net (code "20") (name "/CLK") (class "Default")
      (node (ref "HC1") (pin "11") (pinfunction "SCK_11") (pintype "passive"))
      (node (ref "HC2") (pin "11") (pinfunction "SCK_11") (pintype "passive"))
      (node (ref "UM1") (pin "3") (pinfunction "PC14-OSC32_IN_3") (pintype "passive"))
    )
    (net (code "21") (name "/CSN") (class "Default")
      (node (ref "UA1") (pin "2") (pinfunction "SPI_CS/GPIO_16_2") (pintype "passive"))
    )
    (net (code "23") (name "/DATA_IN") (class "Default")
      (node (ref "HC1") (pin "14") (pinfunction "SER_14") (pintype "passive"))
      (node (ref "UM1") (pin "40") (pinfunction "PB4/SPI1_MISO_40") (pintype "passive"))
    )
    (net (code "24") (name "/HST_RXD") (class "Default")
      (node (ref "UA1") (pin "25") (pinfunction "UART0_RXD/GPIO_4_25") (pintype "passive"))
    )
    (net (code "25") (name "/HST_TXD") (class "Default")
      (node (ref "UA1") (pin "26") (pinfunction "UART0_TXD/GPIO_5_26") (pintype "passive"))
    )
    (net (code "26") (name "/I2C1_SCL2") (class "Default")
      (node (ref "UA1") (pin "30") (pinfunction "I2C0_SCL/GPIO_10_30") (pintype "passive"))
    )
    (net (code "27") (name "/I2C1_SDA2") (class "Default")
      (node (ref "UA1") (pin "29") (pinfunction "I2C0_SDA/GPIO_8_29") (pintype "passive"))
    )
    (net (code "28") (name "/IN+1") (class "Default")
      (node (ref "1") (pin "2") (pinfunction "2_2") (pintype "passive"))
      (node (ref "JP4") (pin "2") (pinfunction "2_2") (pintype "passive"))
    )
    (net (code "29") (name "/IN+2") (class "Default")
      (node (ref "2") (pin "2") (pinfunction "2_2") (pintype "passive"))
      (node (ref "JP4") (pin "4") (pinfunction "4_4") (pintype "passive"))
    )
    (net (code "30") (name "/IN+3") (class "Default")
      (node (ref "3") (pin "2") (pinfunction "2_2") (pintype "passive"))
      (node (ref "JP4") (pin "6") (pinfunction "6_6") (pintype "passive"))
    )
    (net (code "31") (name "/IN+4") (class "Default")
      (node (ref "4") (pin "2") (pinfunction "2_2") (pintype "passive"))
      (node (ref "JP4") (pin "8") (pinfunction "8_8") (pintype "passive"))
    )
    (net (code "32") (name "/IN+5") (class "Default")
      (node (ref "5") (pin "2") (pinfunction "2_2") (pintype "passive"))
      (node (ref "JP4") (pin "10") (pinfunction "10_10") (pintype "passive"))
    )
    (net (code "33") (name "/IRQ") (class "Default")
      (node (ref "UA1") (pin "6") (pinfunction "GPIO9_6") (pintype "passive"))
    )
    (net (code "34") (name "/K1") (class "Default")
      (node (ref "DP1") (pin "2") (pintype "passive"))
      (node (ref "JP3") (pin "1") (pinfunction "1_1") (pintype "passive"))
      (node (ref "JP3-1") (pin "1") (pinfunction "1_1") (pintype "passive"))
      (node (ref "KEY1") (pin "1") (pinfunction "1_1") (pintype "passive"))
    )
    (net (code "35") (name "/K2") (class "Default")
      (node (ref "JP3") (pin "2") (pinfunction "2_2") (pintype "passive"))
      (node (ref "JP3-1") (pin "2") (pinfunction "2_2") (pintype "passive"))
      (node (ref "KEY1") (pin "2") (pinfunction "2_2") (pintype "passive"))
      (node (ref "RG1") (pin "1") (pinfunction "1_1") (pintype "passive"))
    )
    (net (code "36") (name "/K3") (class "Default")
      (node (ref "DP2") (pin "2") (pintype "passive"))
      (node (ref "JP3") (pin "3") (pinfunction "3_3") (pintype "passive"))
      (node (ref "KEY2") (pin "1") (pinfunction "1_1") (pintype "passive"))
    )
    (net (code "37") (name "/K4") (class "Default")
      (node (ref "JP3") (pin "4") (pinfunction "4_4") (pintype "passive"))
      (node (ref "KEY2") (pin "2") (pinfunction "2_2") (pintype "passive"))
      (node (ref "RG2") (pin "1") (pinfunction "1_1") (pintype "passive"))
    )
    (net (code "38") (name "/K5") (class "Default")
      (node (ref "DP3") (pin "2") (pintype "passive"))
      (node (ref "JP3") (pin "5") (pinfunction "5_5") (pintype "passive"))
      (node (ref "KEY3") (pin "1") (pinfunction "1_1") (pintype "passive"))
    )
    (net (code "39") (name "/K6") (class "Default")
      (node (ref "JP3") (pin "6") (pinfunction "6_6") (pintype "passive"))
      (node (ref "KEY3") (pin "2") (pinfunction "2_2") (pintype "passive"))
      (node (ref "RG3") (pin "1") (pinfunction "1_1") (pintype "passive"))
    )
    (net (code "40") (name "/LIN") (class "Default")
      (node (ref "FD1") (pin "2") (pinfunction "2_2") (pintype "passive"))
      (node (ref "MK1") (pin "1") (pinfunction "1_1") (pintype "passive"))
      (node (ref "YM1") (pin "2") (pinfunction "2_2") (pintype "passive"))
    )
    (net (code "41") (name "/LOCK") (class "Default")
      (node (ref "HC1") (pin "12") (pinfunction "SCL_12") (pintype "passive"))
      (node (ref "HC2") (pin "12") (pinfunction "SCL_12") (pintype "passive"))
      (node (ref "UM1") (pin "2") (pinfunction "PC13_2") (pintype "passive"))
    )
    (net (code "42") (name "/MISO") (class "Default")
      (node (ref "UA1") (pin "5") (pinfunction "SPI_MISO/GPIO_14_5") (pintype "passive"))
    )
    (net (code "43") (name "/MOSI") (class "Default")
      (node (ref "UA1") (pin "4") (pinfunction "SPI_MOSI/GPIO_11_4") (pintype "passive"))
    )
    (net (code "44") (name "/N") (class "Default")
      (node (ref "MK1") (pin "2") (pinfunction "2_2") (pintype "passive"))
      (node (ref "P2") (pin "2") (pinfunction "2_2") (pintype "passive"))
      (node (ref "P2") (pin "4") (pinfunction "4_4") (pintype "passive"))
      (node (ref "P2") (pin "6") (pinfunction "6_6") (pintype "passive"))
      (node (ref "P2") (pin "8") (pinfunction "8_8") (pintype "passive"))
      (node (ref "YM1") (pin "1") (pinfunction "1_1") (pintype "passive"))
    )
    (net (code "45") (name "/NB-ANT") (class "Default")
      (node (ref "SMA1") (pin "2") (pinfunction "2_2") (pintype "passive"))
      (node (ref "UA1") (pin "32") (pinfunction "ANT_32") (pintype "passive"))
    )
    (net (code "46") (name "/NB-GPIO17") (class "Default")
      (node (ref "UA1") (pin "19") (pinfunction "GPIO_17_19") (pintype "passive"))
    )
    (net (code "47") (name "/NB-GPIO18") (class "Default")
      (node (ref "UA1") (pin "18") (pinfunction "GPIO_18_18") (pintype "passive+no_connect"))
    )
    (net (code "49") (name "/NB-SWCLK") (class "Default")
      (node (ref "NB-SW1") (pin "2") (pinfunction "2_2") (pintype "passive"))
      (node (ref "UA1") (pin "10") (pinfunction "SWCLK_10") (pintype "passive"))
    )
    (net (code "50") (name "/NB-SWDIO") (class "Default")
      (node (ref "NB-SW1") (pin "3") (pinfunction "3_3") (pintype "passive"))
      (node (ref "UA1") (pin "11") (pinfunction "SWDIO_11") (pintype "passive"))
    )
    (net (code "51") (name "/NET-INT") (class "Default")
      (node (ref "RO3") (pin "2") (pinfunction "2_2") (pintype "passive"))
      (node (ref "UM1") (pin "35") (pinfunction "PF6_35") (pintype "passive"))
      (node (ref "W1") (pin "3") (pinfunction "INT_3") (pintype "passive"))
    )
    (net (code "52") (name "/NET-MISO") (class "Default")
      (node (ref "RH10") (pin "1") (pinfunction "1_1") (pintype "passive"))
      (node (ref "RH19") (pin "1") (pinfunction "1_1") (pintype "passive"))
      (node (ref "RH28") (pin "1") (pinfunction "1_1") (pintype "passive"))
      (node (ref "RH35") (pin "1") (pinfunction "1_1") (pintype "passive"))
      (node (ref "RH41") (pin "1") (pinfunction "1_1") (pintype "passive"))
      (node (ref "RO6") (pin "1") (pinfunction "1_1") (pintype "passive"))
      (node (ref "UM1") (pin "27") (pinfunction "PB14/SPI1_MISO_27") (pintype "passive"))
      (node (ref "W1") (pin "8") (pinfunction "MISO_8") (pintype "passive"))
    )
    (net (code "53") (name "/NET-MOSI") (class "Default")
      (node (ref "RH14") (pin "1") (pinfunction "1_1") (pintype "passive"))
      (node (ref "RH20") (pin "1") (pinfunction "1_1") (pintype "passive"))
      (node (ref "RH30") (pin "1") (pinfunction "1_1") (pintype "passive"))
      (node (ref "RH36") (pin "1") (pinfunction "1_1") (pintype "passive"))
      (node (ref "RH5") (pin "1") (pinfunction "1_1") (pintype "passive"))
      (node (ref "RO4") (pin "1") (pinfunction "1_1") (pintype "passive"))
      (node (ref "UM1") (pin "28") (pinfunction "PB15/SPI1_MOSI_28") (pintype "passive"))
      (node (ref "W1") (pin "6") (pinfunction "MOSI_6") (pintype "passive"))
    )
    (net (code "54") (name "/NET-NRST") (class "Default")
      (node (ref "RO5") (pin "2") (pinfunction "2_2") (pintype "passive"))
      (node (ref "W1") (pin "5") (pinfunction "RST_5") (pintype "passive"))
    )
    (net (code "55") (name "/NET-SCLK") (class "Default")
      (node (ref "RH15") (pin "1") (pinfunction "1_1") (pintype "passive"))
      (node (ref "RH22") (pin "1") (pinfunction "1_1") (pintype "passive"))
      (node (ref "RH31") (pin "1") (pinfunction "1_1") (pintype "passive"))
      (node (ref "RH37") (pin "1") (pinfunction "1_1") (pintype "passive"))
      (node (ref "RH6") (pin "1") (pinfunction "1_1") (pintype "passive"))
      (node (ref "RO1") (pin "1") (pinfunction "1_1") (pintype "passive"))
      (node (ref "UM1") (pin "26") (pinfunction "PB13/SPI1_SCK_26") (pintype "passive"))
      (node (ref "W1") (pin "2") (pinfunction "SCLK_2") (pintype "passive"))
    )
    (net (code "56") (name "/NET-SCS") (class "Default")
      (node (ref "HC2") (pin "7") (pinfunction "QH_7") (pintype "passive"))
      (node (ref "RO2") (pin "1") (pinfunction "1_1") (pintype "passive"))
      (node (ref "W1") (pin "4") (pinfunction "SCS_4") (pintype "passive"))
    )
    (net (code "57") (name "/NET_LED{slash}GPIO_33") (class "Default")
      (node (ref "RR1") (pin "2") (pinfunction "2_2") (pintype "passive"))
      (node (ref "UA1") (pin "13") (pinfunction "NET_LED/GPIO_19_13") (pintype "passive"))
    )
    (net (code "58") (name "/NRST") (class "Default")
      (node (ref "CU18") (pin "1") (pinfunction "1_1") (pintype "passive"))
      (node (ref "RU1") (pin "2") (pinfunction "2_2") (pintype "passive"))
      (node (ref "ST-LINK1") (pin "3") (pinfunction "3_3") (pintype "passive"))
      (node (ref "UM1") (pin "7") (pinfunction "NRST_7") (pintype "passive"))
    )
    (net (code "59") (name "/PA8") (class "Default")
      (node (ref "P4") (pin "5") (pinfunction "5_5") (pintype "passive"))
      (node (ref "UM1") (pin "29") (pinfunction "PA8_29") (pintype "passive"))
    )
    (net (code "60") (name "/PA9") (class "Default")
      (node (ref "P4") (pin "4") (pinfunction "4_4") (pintype "passive"))
      (node (ref "UM1") (pin "30") (pinfunction "PA9/USART1_TX_30") (pintype "passive"))
    )
    (net (code "61") (name "/PA10") (class "Default")
      (node (ref "P4") (pin "6") (pinfunction "6_6") (pintype "passive"))
      (node (ref "UM1") (pin "31") (pinfunction "PA10/USART1_RX_31") (pintype "passive"))
    )
    (net (code "62") (name "/PA11") (class "Default")
      (node (ref "P4") (pin "7") (pinfunction "7_7") (pintype "passive"))
      (node (ref "UM1") (pin "32") (pinfunction "PA11_32") (pintype "passive"))
    )
    (net (code "63") (name "/PA12") (class "Default")
      (node (ref "CJ6") (pin "2") (pinfunction "2_2") (pintype "passive"))
      (node (ref "GP3") (pin "4") (pinfunction "C_4") (pintype "passive"))
      (node (ref "R4") (pin "1") (pinfunction "1_1") (pintype "passive"))
      (node (ref "UM1") (pin "33") (pinfunction "PA12_33") (pintype "passive"))
    )
    (net (code "64") (name "/PA13") (class "Default")
      (node (ref "ST-LINK1") (pin "4") (pinfunction "4_4") (pintype "passive"))
      (node (ref "UM1") (pin "34") (pinfunction "PA13__(SWDIO)_34") (pintype "passive"))
    )
    (net (code "65") (name "/PA14") (class "Default")
      (node (ref "P4") (pin "10") (pinfunction "10_10") (pintype "passive"))
      (node (ref "ST-LINK1") (pin "5") (pinfunction "5_5") (pintype "passive"))
      (node (ref "UM1") (pin "37") (pinfunction "PA14__(SWCLK)_37") (pintype "passive"))
    )
    (net (code "66") (name "/PA15") (class "Default")
      (node (ref "P4") (pin "9") (pinfunction "9_9") (pintype "passive"))
      (node (ref "UM1") (pin "38") (pinfunction "PA15/USART1_RX_38") (pintype "passive"))
    )
    (net (code "67") (name "/PB1") (class "Default")
      (node (ref "CJ2") (pin "2") (pinfunction "2_2") (pintype "passive"))
      (node (ref "GP1") (pin "4") (pinfunction "C_4") (pintype "passive"))
      (node (ref "R2") (pin "1") (pinfunction "1_1") (pintype "passive"))
      (node (ref "UM1") (pin "19") (pinfunction "PB1_19") (pintype "passive"))
    )
    (net (code "68") (name "/PB2") (class "Default")
      (node (ref "CJ4") (pin "2") (pinfunction "2_2") (pintype "passive"))
      (node (ref "GP2") (pin "4") (pinfunction "C_4") (pintype "passive"))
      (node (ref "R3") (pin "1") (pinfunction "1_1") (pintype "passive"))
      (node (ref "UM1") (pin "20") (pinfunction "PB2_20") (pintype "passive"))
    )
    (net (code "69") (name "/PB3") (class "Default")
      (node (ref "RH44") (pin "2") (pinfunction "2_2") (pintype "passive"))
      (node (ref "UM1") (pin "39") (pinfunction "PB3/SPI1_SCK_39") (pintype "passive"))
    )
    (net (code "70") (name "/PB5") (class "Default")
      (node (ref "HC1") (pin "13") (pinfunction "OE_13") (pintype "passive"))
      (node (ref "HC2") (pin "13") (pinfunction "OE_13") (pintype "passive"))
      (node (ref "UM1") (pin "41") (pinfunction "PB5/SPI1_MOSI_41") (pintype "passive"))
    )
    (net (code "71") (name "/PB8") (class "Default")
      (node (ref "IIC1") (pin "6") (pinfunction "SCL_6") (pintype "passive"))
      (node (ref "RV2") (pin "1") (pinfunction "1_1") (pintype "passive"))
      (node (ref "UM1") (pin "45") (pinfunction "PB8/I2C1_SCL_45") (pintype "passive"))
    )
    (net (code "72") (name "/PB9") (class "Default")
      (node (ref "IIC1") (pin "5") (pinfunction "SDA_5") (pintype "passive"))
      (node (ref "RV1") (pin "1") (pinfunction "1_1") (pintype "passive"))
      (node (ref "UM1") (pin "46") (pinfunction "PB9/I2C1_SDA_46") (pintype "passive"))
    )
    (net (code "73") (name "/PB10") (class "Default")
      (node (ref "RH43") (pin "2") (pinfunction "2_2") (pintype "passive"))
      (node (ref "RU3") (pin "2") (pinfunction "2_2") (pintype "passive"))
      (node (ref "UM1") (pin "21") (pinfunction "PB10/I2C2_SCL_21") (pintype "passive"))
    )
    (net (code "74") (name "/PB11") (class "Default")
      (node (ref "RH42") (pin "2") (pinfunction "2_2") (pintype "passive"))
      (node (ref "RU4") (pin "2") (pinfunction "2_2") (pintype "passive"))
      (node (ref "UM1") (pin "22") (pinfunction "PB11/I2C1_SDA_22") (pintype "passive"))
    )
    (net (code "75") (name "/PB12") (class "Default")
      (node (ref "JP2") (pin "2") (pinfunction "2_2") (pintype "passive"))
      (node (ref "RD1") (pin "2") (pinfunction "2_2") (pintype "passive"))
      (node (ref "UM1") (pin "25") (pinfunction "PB12_25") (pintype "passive"))
    )
    (net (code "76") (name "/PC15") (class "Default")
      (node (ref "HC1") (pin "10") (pinfunction "SCLR_10") (pintype "passive"))
      (node (ref "HC2") (pin "10") (pinfunction "SCLR_10") (pintype "passive"))
      (node (ref "UM1") (pin "4") (pinfunction "PC15-OSC32_OUT_4") (pintype "passive"))
    )
    (net (code "77") (name "/PF7") (class "Default")
      (node (ref "RH4") (pin "2") (pinfunction "2_2") (pintype "passive"))
      (node (ref "UM1") (pin "36") (pinfunction "PF7_36") (pintype "passive"))
    )
    (net (code "78") (name "/PT100-1") (class "Default")
      (node (ref "CX1") (pin "2") (pinfunction "2_2") (pintype "passive"))
      (node (ref "LX1") (pin "2") (pintype "passive"))
      (node (ref "P0") (pin "1") (pinfunction "1_1") (pintype "passive"))
      (node (ref "PT2") (pin "1") (pinfunction "1_1") (pintype "passive"))
    )
    (net (code "79") (name "/PT100-2") (class "Default")
      (node (ref "CX2") (pin "2") (pinfunction "2_2") (pintype "passive"))
      (node (ref "LX2") (pin "2") (pintype "passive"))
      (node (ref "P0") (pin "3") (pinfunction "3_3") (pintype "passive"))
      (node (ref "PT3") (pin "1") (pinfunction "1_1") (pintype "passive"))
    )
    (net (code "80") (name "/PT100-3") (class "Default")
      (node (ref "CX3") (pin "2") (pinfunction "2_2") (pintype "passive"))
      (node (ref "LX3") (pin "2") (pintype "passive"))
      (node (ref "P0") (pin "5") (pinfunction "5_5") (pintype "passive"))
      (node (ref "PT4") (pin "1") (pinfunction "1_1") (pintype "passive"))
    )
    (net (code "81") (name "/PT100-4") (class "Default")
      (node (ref "CX4") (pin "2") (pinfunction "2_2") (pintype "passive"))
      (node (ref "LX4") (pin "2") (pintype "passive"))
      (node (ref "P0") (pin "7") (pinfunction "7_7") (pintype "passive"))
      (node (ref "PT5") (pin "1") (pinfunction "1_1") (pintype "passive"))
    )
    (net (code "82") (name "/PT100-5") (class "Default")
      (node (ref "CX5") (pin "2") (pinfunction "2_2") (pintype "passive"))
      (node (ref "LX5") (pin "2") (pintype "passive"))
      (node (ref "P0") (pin "9") (pinfunction "9_9") (pintype "passive"))
      (node (ref "PT6") (pin "1") (pinfunction "1_1") (pintype "passive"))
    )
    (net (code "83") (name "/PWRKEY") (class "Default")
      (node (ref "QK14") (pin "1") (pinfunction "C_1") (pintype "passive"))
      (node (ref "R5") (pin "2") (pintype "passive"))
      (node (ref "UA1") (pin "12") (pinfunction "WAKEUP_IN_12") (pintype "passive"))
    )
    (net (code "84") (name "/SCK") (class "Default")
      (node (ref "UA1") (pin "3") (pinfunction "SPI_CLK/GPIO_15_3") (pintype "passive"))
    )
    (net (code "85") (name "/SD-INT2") (class "Default")
      (node (ref "UA1") (pin "27") (pinfunction "UART2_RXD/GPIO_2_27") (pintype "passive"))
    )
    (net (code "86") (name "/SIM_CLK") (class "Default")
      (node (ref "C8") (pin "1") (pinfunction "1_1") (pintype "passive"))
      (node (ref "RA9") (pin "2") (pinfunction "2_2") (pintype "passive"))
      (node (ref "UA1") (pin "23") (pinfunction "SIM_CLK_23") (pintype "passive"))
      (node (ref "VR5") (pin "1") (pintype "passive"))
    )
    (net (code "87") (name "/SIM_DAT") (class "Default")
      (node (ref "C9") (pin "1") (pinfunction "1_1") (pintype "passive"))
      (node (ref "RA8") (pin "1") (pinfunction "1_1") (pintype "passive"))
      (node (ref "UA1") (pin "22") (pinfunction "SIM_DAT_22") (pintype "passive"))
      (node (ref "VR2") (pin "1") (pintype "passive"))
    )
    (net (code "88") (name "/SIM_RST") (class "Default")
      (node (ref "C10") (pin "1") (pinfunction "1_1") (pintype "passive"))
      (node (ref "RA7") (pin "1") (pinfunction "1_1") (pintype "passive"))
      (node (ref "UA1") (pin "20") (pinfunction "SIM_RST_20") (pintype "passive"))
      (node (ref "VR3") (pin "1") (pintype "passive"))
    )
    (net (code "89") (name "/TCLCS1") (class "Default")
      (node (ref "HC2") (pin "2") (pinfunction "QC_2") (pintype "passive"))
      (node (ref "RH8") (pin "1") (pinfunction "1_1") (pintype "passive"))
    )
    (net (code "90") (name "/TCLCS2") (class "Default")
      (node (ref "HC2") (pin "3") (pinfunction "QD_3") (pintype "passive"))
      (node (ref "RH17") (pin "1") (pinfunction "1_1") (pintype "passive"))
    )
    (net (code "91") (name "/TCLCS3") (class "Default")
      (node (ref "HC2") (pin "4") (pinfunction "QE_4") (pintype "passive"))
      (node (ref "RH26") (pin "1") (pinfunction "1_1") (pintype "passive"))
    )
    (net (code "92") (name "/TCLCS4") (class "Default")
      (node (ref "HC2") (pin "5") (pinfunction "QF_5") (pintype "passive"))
      (node (ref "RH33") (pin "1") (pinfunction "1_1") (pintype "passive"))
    )
    (net (code "93") (name "/TCLCS5") (class "Default")
      (node (ref "HC2") (pin "6") (pinfunction "QG_6") (pintype "passive"))
      (node (ref "RH39") (pin "1") (pinfunction "1_1") (pintype "passive"))
    )
    (net (code "94") (name "/UART1_RXD{slash}GPIO_0") (class "Default")
      (node (ref "TTL2") (pin "1") (pinfunction "1_1") (pintype "passive"))
      (node (ref "UA1") (pin "9") (pinfunction "UART1_RXD/GPIO_13_9") (pintype "passive"))
    )
    (net (code "95") (name "/UART1_TXD{slash}GPIO_1") (class "Default")
      (node (ref "TTL2") (pin "3") (pinfunction "3_3") (pintype "passive"))
      (node (ref "UA1") (pin "8") (pinfunction "UART1_TXD/GPIO_12_8") (pintype "passive"))
    )
    (net (code "96") (name "/USART1_RX") (class "Default")
      (node (ref "TTL1") (pin "3") (pinfunction "3_3") (pintype "passive"))
      (node (ref "TTL2") (pin "4") (pinfunction "4_4") (pintype "passive"))
      (node (ref "UM1") (pin "43") (pinfunction "PB7/I2C1_SDA/USART1_RX_43") (pintype "passive"))
    )
    (net (code "97") (name "/USART1_TX") (class "Default")
      (node (ref "TTL1") (pin "2") (pinfunction "2_2") (pintype "passive"))
      (node (ref "TTL2") (pin "2") (pinfunction "2_2") (pintype "passive"))
      (node (ref "UM1") (pin "42") (pinfunction "PB6/I2C1_SCL/USART1_TX_42") (pintype "passive"))
    )
    (net (code "98") (name "/USART2_RX") (class "Default")
      (node (ref "U1") (pin "1") (pinfunction "RO_1") (pintype "passive"))
      (node (ref "UM1") (pin "13") (pinfunction "PA3_13") (pintype "passive"))
    )
    (net (code "99") (name "/USART2_TX") (class "Default")
      (node (ref "U1") (pin "4") (pinfunction "DI_4") (pintype "passive"))
      (node (ref "UM1") (pin "12") (pinfunction "PA2_12") (pintype "passive"))
    )
    (net (code "100") (name "/gpio_5") (class "Default")
      (node (ref "UA1") (pin "28") (pinfunction "UART2_TXD/GPIO_3_28") (pintype "passive"))
    )
    (net (code "101") (name "/串1") (class "Default")
      (node (ref "HC1") (pin "15") (pinfunction "QA_15") (pintype "passive"))
      (node (ref "RH29") (pin "2") (pinfunction "2_2") (pintype "passive"))
    )
    (net (code "102") (name "/串2") (class "Default")
      (node (ref "HC1") (pin "1") (pinfunction "QB_1") (pintype "passive"))
      (node (ref "RH25") (pin "2") (pinfunction "2_2") (pintype "passive"))
    )
    (net (code "103") (name "/串3") (class "Default")
      (node (ref "HC1") (pin "2") (pinfunction "QC_2") (pintype "passive"))
      (node (ref "RH24") (pin "2") (pinfunction "2_2") (pintype "passive"))
    )
    (net (code "104") (name "/串4") (class "Default")
      (node (ref "HC1") (pin "3") (pinfunction "QD_3") (pintype "passive"))
      (node (ref "RH21") (pin "2") (pinfunction "2_2") (pintype "passive"))
    )
    (net (code "105") (name "/串5") (class "Default")
      (node (ref "HC1") (pin "4") (pinfunction "QE_4") (pintype "passive"))
      (node (ref "RH11") (pin "2") (pinfunction "2_2") (pintype "passive"))
    )
    (net (code "106") (name "/串6") (class "Default")
      (node (ref "HC1") (pin "5") (pinfunction "QF_5") (pintype "passive"))
      (node (ref "RH12") (pin "2") (pinfunction "2_2") (pintype "passive"))
    )
    (net (code "107") (name "/串7") (class "Default")
      (node (ref "HC1") (pin "6") (pinfunction "QG_6") (pintype "passive"))
      (node (ref "RH13") (pin "2") (pinfunction "2_2") (pintype "passive"))
    )
    (net (code "108") (name "/串8") (class "Default")
      (node (ref "HC1") (pin "7") (pinfunction "QH_7") (pintype "passive"))
      (node (ref "RH3") (pin "2") (pinfunction "2_2") (pintype "passive"))
    )
    (net (code "109") (name "/串9") (class "Default")
      (node (ref "HC2") (pin "15") (pinfunction "QA_15") (pintype "passive"))
      (node (ref "RH2") (pin "2") (pinfunction "2_2") (pintype "passive"))
    )
    (net (code "110") (name "/串10") (class "Default")
      (node (ref "HC2") (pin "1") (pinfunction "QB_1") (pintype "passive"))
      (node (ref "RH1") (pin "2") (pinfunction "2_2") (pintype "passive"))
    )
    (net (code "121") (name "220V") (class "Default")
      (node (ref "FD1") (pin "1") (pinfunction "1_1") (pintype "passive"))
      (node (ref "K1") (pin "1") (pinfunction "1_1") (pintype "passive"))
      (node (ref "K2") (pin "1") (pinfunction "1_1") (pintype "passive"))
      (node (ref "PJP1") (pin "3") (pinfunction "3_3") (pintype "passive"))
      (node (ref "PJP1") (pin "4") (pinfunction "4_4") (pintype "passive"))
    )
    (net (code "122") (name "220Vout1") (class "Default")
      (node (ref "K1") (pin "3") (pinfunction "3_3") (pintype "passive"))
      (node (ref "P2") (pin "5") (pinfunction "5_5") (pintype "passive"))
    )
    (net (code "123") (name "220Vout2") (class "Default")
      (node (ref "K2") (pin "3") (pinfunction "3_3") (pintype "passive"))
      (node (ref "P2") (pin "7") (pinfunction "7_7") (pintype "passive"))
    )
    (net (code "124") (name "GND") (class "Default")
      (node (ref "1") (pin "1") (pinfunction "1_1") (pintype "passive"))
      (node (ref "1") (pin "4") (pinfunction "4_4") (pintype "passive"))
      (node (ref "2") (pin "1") (pinfunction "1_1") (pintype "passive"))
      (node (ref "2") (pin "4") (pinfunction "4_4") (pintype "passive"))
      (node (ref "3") (pin "1") (pinfunction "1_1") (pintype "passive"))
      (node (ref "3") (pin "4") (pinfunction "4_4") (pintype "passive"))
      (node (ref "4") (pin "1") (pinfunction "1_1") (pintype "passive"))
      (node (ref "4") (pin "4") (pinfunction "4_4") (pintype "passive"))
      (node (ref "5") (pin "1") (pinfunction "1_1") (pintype "passive"))
      (node (ref "5") (pin "4") (pinfunction "4_4") (pintype "passive"))
      (node (ref "C1") (pin "1") (pinfunction "1_1") (pintype "passive"))
      (node (ref "C10") (pin "2") (pinfunction "2_2") (pintype "passive"))
      (node (ref "C2") (pin "1") (pinfunction "1_1") (pintype "passive"))
      (node (ref "C3") (pin "1") (pinfunction "1_1") (pintype "passive"))
      (node (ref "C4") (pin "1") (pinfunction "1_1") (pintype "passive"))
      (node (ref "C5") (pin "1") (pinfunction "1_1") (pintype "passive"))
      (node (ref "C6") (pin "2") (pinfunction "2_2") (pintype "passive"))
      (node (ref "C7") (pin "1") (pinfunction "1_1") (pintype "passive"))
      (node (ref "C8") (pin "2") (pinfunction "2_2") (pintype "passive"))
      (node (ref "C9") (pin "2") (pinfunction "2_2") (pintype "passive"))
      (node (ref "CD1") (pin "1") (pinfunction "1_1") (pintype "passive"))
      (node (ref "CD2") (pin "1") (pinfunction "1_1") (pintype "passive"))
      (node (ref "CD3") (pin "1") (pinfunction "1_1") (pintype "passive"))
      (node (ref "CD4") (pin "2") (pinfunction "2_2") (pintype "passive"))
      (node (ref "CJ1") (pin "2") (pinfunction "2_2") (pintype "passive"))
      (node (ref "CJ2") (pin "1") (pinfunction "1_1") (pintype "passive"))
      (node (ref "CJ3") (pin "2") (pinfunction "2_2") (pintype "passive"))
      (node (ref "CJ4") (pin "1") (pinfunction "1_1") (pintype "passive"))
      (node (ref "CJ5") (pin "2") (pinfunction "2_2") (pintype "passive"))
      (node (ref "CJ6") (pin "1") (pinfunction "1_1") (pintype "passive"))
      (node (ref "CK1") (pin "1") (pinfunction "1_1") (pintype "passive"))
      (node (ref "CP1") (pin "2") (pinfunction "2_2") (pintype "passive"))
      (node (ref "CP10") (pin "1") (pinfunction "1_1") (pintype "passive"))
      (node (ref "CP11") (pin "2") (pinfunction "2_2") (pintype "passive"))
      (node (ref "CP12") (pin "1") (pinfunction "1_1") (pintype "passive"))
      (node (ref "CP2") (pin "1") (pinfunction "1_1") (pintype "passive"))
      (node (ref "CP3") (pin "2") (pinfunction "2_2") (pintype "passive"))
      (node (ref "CP4") (pin "2") (pinfunction "2_2") (pintype "passive"))
      (node (ref "CP5") (pin "1") (pinfunction "1_1") (pintype "passive"))
      (node (ref "CP6") (pin "1") (pinfunction "1_1") (pintype "passive"))
      (node (ref "CP7") (pin "2") (pinfunction "2_2") (pintype "passive"))
      (node (ref "CP8") (pin "1") (pinfunction "1_1") (pintype "passive"))
      (node (ref "CP9") (pin "2") (pinfunction "2_2") (pintype "passive"))
      (node (ref "CS1") (pin "2") (pinfunction "2_2") (pintype "passive"))
      (node (ref "CU11") (pin "2") (pinfunction "2_2") (pintype "passive"))
      (node (ref "CU12") (pin "2") (pinfunction "2_2") (pintype "passive"))
      (node (ref "CU13") (pin "2") (pinfunction "2_2") (pintype "passive"))
      (node (ref "CU14") (pin "2") (pinfunction "2_2") (pintype "passive"))
      (node (ref "CU16") (pin "2") (pinfunction "2_2") (pintype "passive"))
      (node (ref "CU17") (pin "2") (pinfunction "2_2") (pintype "passive"))
      (node (ref "CU18") (pin "2") (pinfunction "2_2") (pintype "passive"))
      (node (ref "CU20") (pin "2") (pinfunction "2_2") (pintype "passive"))
      (node (ref "CX1") (pin "1") (pinfunction "1_1") (pintype "passive"))
      (node (ref "CX2") (pin "1") (pinfunction "1_1") (pintype "passive"))
      (node (ref "CX3") (pin "1") (pinfunction "1_1") (pintype "passive"))
      (node (ref "CX4") (pin "1") (pinfunction "1_1") (pintype "passive"))
      (node (ref "CX5") (pin "1") (pinfunction "1_1") (pintype "passive"))
      (node (ref "CY1") (pin "1") (pinfunction "1_1") (pintype "passive"))
      (node (ref "CY2") (pin "1") (pinfunction "1_1") (pintype "passive"))
      (node (ref "CY3") (pin "1") (pinfunction "1_1") (pintype "passive"))
      (node (ref "CY4") (pin "1") (pinfunction "1_1") (pintype "passive"))
      (node (ref "CY5") (pin "1") (pinfunction "1_1") (pintype "passive"))
      (node (ref "Cu1") (pin "2") (pinfunction "2_2") (pintype "passive"))
      (node (ref "Cu10") (pin "2") (pinfunction "2_2") (pintype "passive"))
      (node (ref "Cu15") (pin "2") (pinfunction "2_2") (pintype "passive"))
      (node (ref "Cu19") (pin "2") (pinfunction "2_2") (pintype "passive"))
      (node (ref "Cu2") (pin "1") (pinfunction "1_1") (pintype "passive"))
      (node (ref "Cu21") (pin "2") (pinfunction "2_2") (pintype "passive"))
      (node (ref "Cu22") (pin "2") (pinfunction "2_2") (pintype "passive"))
      (node (ref "Cu23") (pin "2") (pinfunction "2_2") (pintype "passive"))
      (node (ref "Cu24") (pin "2") (pinfunction "2_2") (pintype "passive"))
      (node (ref "Cu25") (pin "2") (pinfunction "2_2") (pintype "passive"))
      (node (ref "Cu26") (pin "2") (pinfunction "2_2") (pintype "passive"))
      (node (ref "Cu27") (pin "2") (pinfunction "2_2") (pintype "passive"))
      (node (ref "Cu28") (pin "1") (pinfunction "1_1") (pintype "passive"))
      (node (ref "Cu29") (pin "2") (pinfunction "2_2") (pintype "passive"))
      (node (ref "Cu3") (pin "2") (pinfunction "2_2") (pintype "passive"))
      (node (ref "Cu30") (pin "1") (pinfunction "1_1") (pintype "passive"))
      (node (ref "Cu4") (pin "1") (pinfunction "1_1") (pintype "passive"))
      (node (ref "Cu5") (pin "2") (pinfunction "2_2") (pintype "passive"))
      (node (ref "Cu6") (pin "1") (pinfunction "1_1") (pintype "passive"))
      (node (ref "Cu7") (pin "2") (pinfunction "2_2") (pintype "passive"))
      (node (ref "Cu8") (pin "2") (pinfunction "2_2") (pintype "passive"))
      (node (ref "Cu9") (pin "1") (pinfunction "1_1") (pintype "passive"))
      (node (ref "D1") (pin "1") (pinfunction "A_1") (pintype "passive"))
      (node (ref "D2") (pin "1") (pinfunction "A_1") (pintype "passive"))
      (node (ref "D3") (pin "1") (pinfunction "A_1") (pintype "passive"))
      (node (ref "D4") (pin "1") (pinfunction "A_1") (pintype "passive"))
      (node (ref "D5") (pin "1") (pinfunction "A_1") (pintype "passive"))
      (node (ref "D6") (pin "2") (pinfunction "2_2") (pintype "passive"))
      (node (ref "D7") (pin "2") (pinfunction "2_2") (pintype "passive"))
      (node (ref "DL1") (pin "2") (pinfunction "K_2") (pintype "passive"))
      (node (ref "DL10") (pin "2") (pinfunction "K_2") (pintype "passive"))
      (node (ref "DL11") (pin "2") (pinfunction "K_2") (pintype "passive"))
      (node (ref "DL15") (pin "2") (pinfunction "K_2") (pintype "passive"))
      (node (ref "DL17") (pin "2") (pinfunction "K_2") (pintype "passive"))
      (node (ref "DL18") (pin "2") (pinfunction "K_2") (pintype "passive"))
      (node (ref "DL2") (pin "2") (pinfunction "K_2") (pintype "passive"))
      (node (ref "DL6") (pin "2") (pinfunction "K_2") (pintype "passive"))
      (node (ref "DZ1") (pin "1") (pintype "passive"))
      (node (ref "GP1") (pin "2") (pinfunction "K_2") (pintype "passive"))
      (node (ref "GP1") (pin "3") (pinfunction "E_3") (pintype "passive"))
      (node (ref "GP2") (pin "2") (pinfunction "K_2") (pintype "passive"))
      (node (ref "GP2") (pin "3") (pinfunction "E_3") (pintype "passive"))
      (node (ref "GP3") (pin "2") (pinfunction "K_2") (pintype "passive"))
      (node (ref "GP3") (pin "3") (pinfunction "E_3") (pintype "passive"))
      (node (ref "HC1") (pin "8") (pinfunction "GND_8") (pintype "passive"))
      (node (ref "HC2") (pin "8") (pinfunction "GND_8") (pintype "passive"))
      (node (ref "IIC1") (pin "1") (pinfunction "A0_1") (pintype "passive"))
      (node (ref "IIC1") (pin "2") (pinfunction "A1_2") (pintype "passive"))
      (node (ref "IIC1") (pin "3") (pinfunction "A2_3") (pintype "passive"))
      (node (ref "IIC1") (pin "4") (pinfunction "GND_4") (pintype "passive"))
      (node (ref "IIC1") (pin "7") (pinfunction "WP_7") (pintype "passive"))
      (node (ref "J1") (pin "10") (pinfunction "GND_10") (pintype "passive"))
      (node (ref "J1") (pin "11") (pinfunction "GND_11") (pintype "passive"))
      (node (ref "J1") (pin "2") (pinfunction "GND_2") (pintype "passive"))
      (node (ref "J1") (pin "8") (pinfunction "GND_8") (pintype "passive"))
      (node (ref "J1") (pin "9") (pinfunction "GND_9") (pintype "passive"))
      (node (ref "JP1") (pin "1") (pinfunction "1_1") (pintype "passive"))
      (node (ref "JP2") (pin "4") (pinfunction "4_4") (pintype "passive"))
      (node (ref "JP4") (pin "1") (pinfunction "1_1") (pintype "passive"))
      (node (ref "JP4") (pin "3") (pinfunction "3_3") (pintype "passive"))
      (node (ref "JP4") (pin "5") (pinfunction "5_5") (pintype "passive"))
      (node (ref "JP4") (pin "7") (pinfunction "7_7") (pintype "passive"))
      (node (ref "JP4") (pin "9") (pinfunction "9_9") (pintype "passive"))
      (node (ref "MK1") (pin "4") (pinfunction "4_4") (pintype "passive"))
      (node (ref "NB-SW1") (pin "1") (pinfunction "1_1") (pintype "passive"))
      (node (ref "P0") (pin "10") (pinfunction "10_10") (pintype "passive"))
      (node (ref "P0") (pin "2") (pinfunction "2_2") (pintype "passive"))
      (node (ref "P0") (pin "4") (pinfunction "4_4") (pintype "passive"))
      (node (ref "P0") (pin "6") (pinfunction "6_6") (pintype "passive"))
      (node (ref "P0") (pin "8") (pinfunction "8_8") (pintype "passive"))
      (node (ref "P1") (pin "2") (pinfunction "2_2") (pintype "passive"))
      (node (ref "P4") (pin "2") (pinfunction "2_2") (pintype "passive"))
      (node (ref "PT2") (pin "2") (pinfunction "2_2") (pintype "passive"))
      (node (ref "PT3") (pin "2") (pinfunction "2_2") (pintype "passive"))
      (node (ref "PT4") (pin "2") (pinfunction "2_2") (pintype "passive"))
      (node (ref "PT5") (pin "2") (pinfunction "2_2") (pintype "passive"))
      (node (ref "PT6") (pin "2") (pinfunction "2_2") (pintype "passive"))
      (node (ref "QK1") (pin "3") (pinfunction "E_3") (pintype "passive"))
      (node (ref "QK10") (pin "3") (pinfunction "E_3") (pintype "passive"))
      (node (ref "QK11") (pin "3") (pinfunction "E_3") (pintype "passive"))
      (node (ref "QK12") (pin "3") (pinfunction "E_3") (pintype "passive"))
      (node (ref "QK13") (pin "3") (pinfunction "E_3") (pintype "passive"))
      (node (ref "QK14") (pin "3") (pinfunction "E_3") (pintype "passive"))
      (node (ref "QK2") (pin "3") (pinfunction "E_3") (pintype "passive"))
      (node (ref "QK3") (pin "3") (pinfunction "E_3") (pintype "passive"))
      (node (ref "QK4") (pin "3") (pinfunction "E_3") (pintype "passive"))
      (node (ref "QK5") (pin "3") (pinfunction "E_3") (pintype "passive"))
      (node (ref "QK6") (pin "3") (pinfunction "E_3") (pintype "passive"))
      (node (ref "QK7") (pin "3") (pinfunction "E_3") (pintype "passive"))
      (node (ref "QK8") (pin "3") (pinfunction "E_3") (pintype "passive"))
      (node (ref "QK9") (pin "3") (pinfunction "E_3") (pintype "passive"))
      (node (ref "R5") (pin "1") (pintype "passive"))
      (node (ref "RE1") (pin "1") (pinfunction "1_1") (pintype "passive"))
      (node (ref "RE10") (pin "1") (pinfunction "1_1") (pintype "passive"))
      (node (ref "RE2") (pin "1") (pinfunction "1_1") (pintype "passive"))
      (node (ref "RE3") (pin "1") (pinfunction "1_1") (pintype "passive"))
      (node (ref "RE4") (pin "1") (pinfunction "1_1") (pintype "passive"))
      (node (ref "RE5") (pin "1") (pinfunction "1_1") (pintype "passive"))
      (node (ref "RE6") (pin "1") (pinfunction "1_1") (pintype "passive"))
      (node (ref "RE7") (pin "1") (pinfunction "1_1") (pintype "passive"))
      (node (ref "RE8") (pin "1") (pinfunction "1_1") (pintype "passive"))
      (node (ref "RE9") (pin "1") (pinfunction "1_1") (pintype "passive"))
      (node (ref "RI1") (pin "2") (pinfunction "2_2") (pintype "passive"))
      (node (ref "RI10") (pin "2") (pinfunction "2_2") (pintype "passive"))
      (node (ref "RI11") (pin "2") (pinfunction "2_2") (pintype "passive"))
      (node (ref "RI12") (pin "2") (pinfunction "2_2") (pintype "passive"))
      (node (ref "RI13") (pin "2") (pinfunction "2_2") (pintype "passive"))
      (node (ref "RI14") (pin "2") (pinfunction "2_2") (pintype "passive"))
      (node (ref "RI2") (pin "2") (pinfunction "2_2") (pintype "passive"))
      (node (ref "RI3") (pin "2") (pinfunction "2_2") (pintype "passive"))
      (node (ref "RI4") (pin "2") (pinfunction "2_2") (pintype "passive"))
      (node (ref "RI5") (pin "2") (pinfunction "2_2") (pintype "passive"))
      (node (ref "RI6") (pin "2") (pinfunction "2_2") (pintype "passive"))
      (node (ref "RI7") (pin "2") (pinfunction "2_2") (pintype "passive"))
      (node (ref "RI8") (pin "2") (pinfunction "2_2") (pintype "passive"))
      (node (ref "RI9") (pin "2") (pinfunction "2_2") (pintype "passive"))
      (node (ref "RL1") (pin "1") (pinfunction "1_1") (pintype "passive"))
      (node (ref "RL2") (pin "1") (pinfunction "1_1") (pintype "passive"))
      (node (ref "RL3") (pin "1") (pinfunction "1_1") (pintype "passive"))
      (node (ref "RL4") (pin "1") (pinfunction "1_1") (pintype "passive"))
      (node (ref "RL5") (pin "1") (pinfunction "1_1") (pintype "passive"))
      (node (ref "RN1") (pin "2") (pinfunction "2_2") (pintype "passive"))
      (node (ref "RN2") (pin "2") (pinfunction "2_2") (pintype "passive"))
      (node (ref "RN3") (pin "2") (pinfunction "2_2") (pintype "passive"))
      (node (ref "RN4") (pin "2") (pinfunction "2_2") (pintype "passive"))
      (node (ref "RN5") (pin "2") (pinfunction "2_2") (pintype "passive"))
      (node (ref "RU2") (pin "1") (pinfunction "1_1") (pintype "passive"))
      (node (ref "RZ2") (pin "1") (pinfunction "1_1") (pintype "passive"))
      (node (ref "S1") (pin "2") (pinfunction "2_2") (pintype "passive"))
      (node (ref "SMA1") (pin "1") (pinfunction "1_1") (pintype "passive"))
      (node (ref "ST-LINK1") (pin "2") (pinfunction "2_2") (pintype "passive"))
      (node (ref "TCL1") (pin "5") (pinfunction "AGND_5") (pintype "passive"))
      (node (ref "TCL2") (pin "5") (pinfunction "AGND_5") (pintype "passive"))
      (node (ref "TCL3") (pin "5") (pinfunction "AGND_5") (pintype "passive"))
      (node (ref "TCL4") (pin "5") (pinfunction "AGND_5") (pintype "passive"))
      (node (ref "TCL5") (pin "5") (pinfunction "AGND_5") (pintype "passive"))
      (node (ref "TTL1") (pin "4") (pinfunction "4_4") (pintype "passive"))
      (node (ref "TTL2") (pin "5") (pinfunction "5_5") (pintype "passive"))
      (node (ref "TTL2") (pin "6") (pinfunction "6_6") (pintype "passive"))
      (node (ref "TVS1") (pin "1") (pinfunction "A_1") (pintype "passive"))
      (node (ref "TVS2") (pin "1") (pinfunction "A_1") (pintype "passive"))
      (node (ref "U1") (pin "5") (pinfunction "GND_5") (pintype "passive"))
      (node (ref "U10") (pin "1") (pinfunction "GND_1") (pintype "power_in"))
      (node (ref "U2") (pin "1") (pinfunction "GND_1") (pintype "power_in"))
      (node (ref "U3") (pin "1") (pinfunction "GND_1") (pintype "power_in"))
      (node (ref "U4") (pin "1") (pinfunction "GND_1") (pintype "power_in"))
      (node (ref "U5") (pin "1") (pinfunction "GND_1") (pintype "power_in"))
      (node (ref "U6") (pin "4") (pinfunction "V-_4") (pintype "power_in"))
      (node (ref "U7") (pin "4") (pinfunction "V-_4") (pintype "power_in"))
      (node (ref "U8") (pin "1") (pinfunction "GND_1") (pintype "power_in"))
      (node (ref "U9") (pin "4") (pinfunction "V-_4") (pintype "power_in"))
      (node (ref "UA1") (pin "15") (pinfunction "GND_15") (pintype "passive"))
      (node (ref "UA1") (pin "31") (pinfunction "GND_31") (pintype "passive"))
      (node (ref "UA1") (pin "33") (pinfunction "GND_33") (pintype "passive"))
      (node (ref "UA1") (pin "35") (pinfunction "GND_35") (pintype "passive"))
      (node (ref "UA1") (pin "36") (pinfunction "GND_36") (pintype "passive"))
      (node (ref "UA1") (pin "39") (pinfunction "GND_39") (pintype "passive"))
      (node (ref "UA1") (pin "40") (pinfunction "GND_40") (pintype "passive"))
      (node (ref "UA1") (pin "41") (pinfunction "GND_41") (pintype "passive"))
      (node (ref "UM1") (pin "23") (pinfunction "VSS/GND_23") (pintype "passive"))
      (node (ref "UM1") (pin "47") (pinfunction "VSS/GND_47") (pintype "passive"))
      (node (ref "UM1") (pin "8") (pinfunction "VSSA_8") (pintype "passive"))
      (node (ref "VR1") (pin "2") (pintype "passive"))
      (node (ref "VR2") (pin "2") (pintype "passive"))
      (node (ref "VR3") (pin "2") (pintype "passive"))
      (node (ref "VR4") (pin "2") (pintype "passive"))
      (node (ref "VR5") (pin "2") (pintype "passive"))
      (node (ref "W1") (pin "1") (pinfunction "GND_1") (pintype "passive"))
      (node (ref "W1") (pin "7") (pinfunction "GND_7") (pintype "passive"))
    )
    (net (code "125") (name "JDQK21") (class "Default")
      (node (ref "K3") (pin "1") (pinfunction "1_1") (pintype "passive"))
      (node (ref "P2") (pin "9") (pinfunction "9_9") (pintype "passive"))
    )
    (net (code "126") (name "JDQK22") (class "Default")
      (node (ref "K3") (pin "3") (pinfunction "3_3") (pintype "passive"))
      (node (ref "P2") (pin "10") (pinfunction "10_10") (pintype "passive"))
    )
    (net (code "127") (name "JDQK31") (class "Default")
      (node (ref "K6") (pin "1") (pinfunction "1_1") (pintype "passive"))
      (node (ref "P2") (pin "11") (pinfunction "11_11") (pintype "passive"))
    )
    (net (code "128") (name "JDQK32") (class "Default")
      (node (ref "K6") (pin "3") (pinfunction "3_3") (pintype "passive"))
      (node (ref "P2") (pin "12") (pinfunction "12_12") (pintype "passive"))
    )
    (net (code "129") (name "JDQK41") (class "Default")
      (node (ref "K5") (pin "1") (pinfunction "1_1") (pintype "passive"))
      (node (ref "P3") (pin "1") (pinfunction "1_1") (pintype "passive"))
    )
    (net (code "130") (name "JDQK42") (class "Default")
      (node (ref "K5") (pin "3") (pinfunction "3_3") (pintype "passive"))
      (node (ref "P3") (pin "2") (pinfunction "2_2") (pintype "passive"))
    )
    (net (code "131") (name "JDQK51") (class "Default")
      (node (ref "K4") (pin "1") (pinfunction "1_1") (pintype "passive"))
      (node (ref "P3") (pin "3") (pinfunction "3_3") (pintype "passive"))
    )
    (net (code "132") (name "JDQK52") (class "Default")
      (node (ref "K4") (pin "3") (pinfunction "3_3") (pintype "passive"))
      (node (ref "P3") (pin "4") (pinfunction "4_4") (pintype "passive"))
    )
    (net (code "133") (name "JDQK61") (class "Default")
      (node (ref "K8") (pin "1") (pinfunction "1_1") (pintype "passive"))
      (node (ref "P3") (pin "7") (pinfunction "7_7") (pintype "passive"))
    )
    (net (code "134") (name "JDQK62") (class "Default")
      (node (ref "K8") (pin "3") (pinfunction "3_3") (pintype "passive"))
      (node (ref "P3") (pin "8") (pinfunction "8_8") (pintype "passive"))
    )
    (net (code "135") (name "JDQK71") (class "Default")
      (node (ref "K9") (pin "1") (pinfunction "1_1") (pintype "passive"))
      (node (ref "P3") (pin "9") (pinfunction "9_9") (pintype "passive"))
    )
    (net (code "136") (name "JDQK72") (class "Default")
      (node (ref "K9") (pin "3") (pinfunction "3_3") (pintype "passive"))
      (node (ref "P3") (pin "10") (pinfunction "10_10") (pintype "passive"))
    )
    (net (code "137") (name "JDQK81") (class "Default")
      (node (ref "K7") (pin "1") (pinfunction "1_1") (pintype "passive"))
      (node (ref "P3") (pin "5") (pinfunction "5_5") (pintype "passive"))
    )
    (net (code "138") (name "JDQK82") (class "Default")
      (node (ref "K7") (pin "3") (pinfunction "3_3") (pintype "passive"))
      (node (ref "P3") (pin "6") (pinfunction "6_6") (pintype "passive"))
    )
    (net (code "139") (name "JDQK91") (class "Default")
      (node (ref "K10") (pin "1") (pinfunction "1_1") (pintype "passive"))
      (node (ref "P3") (pin "11") (pinfunction "11_11") (pintype "passive"))
    )
    (net (code "140") (name "JDQK92") (class "Default")
      (node (ref "K10") (pin "3") (pinfunction "3_3") (pintype "passive"))
      (node (ref "P3") (pin "12") (pinfunction "12_12") (pintype "passive"))
    )
    (net (code "141") (name "Net-(1-Pad5)") (class "Default")
      (node (ref "1") (pin "5") (pinfunction "5_5") (pintype "passive"))
      (node (ref "Cu10") (pin "1") (pinfunction "1_1") (pintype "passive"))
      (node (ref "RH7") (pin "1") (pinfunction "1_1") (pintype "passive"))
    )
    (net (code "142") (name "Net-(2-Pad5)") (class "Default")
      (node (ref "2") (pin "5") (pinfunction "5_5") (pintype "passive"))
      (node (ref "Cu19") (pin "1") (pinfunction "1_1") (pintype "passive"))
      (node (ref "RH16") (pin "1") (pinfunction "1_1") (pintype "passive"))
    )
    (net (code "143") (name "Net-(3-Pad5)") (class "Default")
      (node (ref "3") (pin "5") (pinfunction "5_5") (pintype "passive"))
      (node (ref "Cu22") (pin "1") (pinfunction "1_1") (pintype "passive"))
      (node (ref "RH23") (pin "1") (pinfunction "1_1") (pintype "passive"))
    )
    (net (code "144") (name "Net-(4-Pad5)") (class "Default")
      (node (ref "4") (pin "5") (pinfunction "5_5") (pintype "passive"))
      (node (ref "Cu24") (pin "1") (pinfunction "1_1") (pintype "passive"))
      (node (ref "RH32") (pin "1") (pinfunction "1_1") (pintype "passive"))
    )
    (net (code "145") (name "Net-(5-Pad5)") (class "Default")
      (node (ref "5") (pin "5") (pinfunction "5_5") (pintype "passive"))
      (node (ref "Cu26") (pin "1") (pinfunction "1_1") (pintype "passive"))
      (node (ref "RH38") (pin "1") (pinfunction "1_1") (pintype "passive"))
    )
    (net (code "146") (name "Net-(CY1-Pad2)") (class "Default")
      (node (ref "CY1") (pin "2") (pinfunction "2_2") (pintype "passive"))
      (node (ref "LX1") (pin "1") (pintype "passive"))
      (node (ref "RE1") (pin "2") (pinfunction "2_2") (pintype "passive"))
      (node (ref "RQ1") (pin "1") (pinfunction "1_1") (pintype "passive"))
      (node (ref "RT1") (pin "2") (pinfunction "2_2") (pintype "passive"))
    )
    (net (code "147") (name "Net-(CY2-Pad2)") (class "Default")
      (node (ref "CY2") (pin "2") (pinfunction "2_2") (pintype "passive"))
      (node (ref "LX2") (pin "1") (pintype "passive"))
      (node (ref "RE3") (pin "2") (pinfunction "2_2") (pintype "passive"))
      (node (ref "RQ2") (pin "1") (pinfunction "1_1") (pintype "passive"))
      (node (ref "RT2") (pin "2") (pinfunction "2_2") (pintype "passive"))
    )
    (net (code "148") (name "Net-(CY3-Pad2)") (class "Default")
      (node (ref "CY3") (pin "2") (pinfunction "2_2") (pintype "passive"))
      (node (ref "LX3") (pin "1") (pintype "passive"))
      (node (ref "RE5") (pin "2") (pinfunction "2_2") (pintype "passive"))
      (node (ref "RQ3") (pin "1") (pinfunction "1_1") (pintype "passive"))
      (node (ref "RT3") (pin "2") (pinfunction "2_2") (pintype "passive"))
    )
    (net (code "149") (name "Net-(CY4-Pad2)") (class "Default")
      (node (ref "CY4") (pin "2") (pinfunction "2_2") (pintype "passive"))
      (node (ref "LX4") (pin "1") (pintype "passive"))
      (node (ref "RE7") (pin "2") (pinfunction "2_2") (pintype "passive"))
      (node (ref "RQ4") (pin "1") (pinfunction "1_1") (pintype "passive"))
      (node (ref "RT4") (pin "2") (pinfunction "2_2") (pintype "passive"))
    )
    (net (code "150") (name "Net-(CY5-Pad2)") (class "Default")
      (node (ref "CY5") (pin "2") (pinfunction "2_2") (pintype "passive"))
      (node (ref "LX5") (pin "1") (pintype "passive"))
      (node (ref "RE9") (pin "2") (pinfunction "2_2") (pintype "passive"))
      (node (ref "RQ5") (pin "1") (pinfunction "1_1") (pintype "passive"))
      (node (ref "RT5") (pin "2") (pinfunction "2_2") (pintype "passive"))
    )
    (net (code "151") (name "Net-(D1-K)") (class "Default")
      (node (ref "C1") (pin "2") (pinfunction "2_2") (pintype "passive"))
      (node (ref "D1") (pin "2") (pinfunction "K_2") (pintype "passive"))
      (node (ref "RF1") (pin "2") (pinfunction "2_2") (pintype "passive"))
      (node (ref "RK1") (pin "2") (pinfunction "2_2") (pintype "passive"))
    )
    (net (code "152") (name "Net-(D2-K)") (class "Default")
      (node (ref "C2") (pin "2") (pinfunction "2_2") (pintype "passive"))
      (node (ref "D2") (pin "2") (pinfunction "K_2") (pintype "passive"))
      (node (ref "RF2") (pin "2") (pinfunction "2_2") (pintype "passive"))
      (node (ref "RK2") (pin "2") (pinfunction "2_2") (pintype "passive"))
    )
    (net (code "153") (name "Net-(D3-K)") (class "Default")
      (node (ref "C3") (pin "2") (pinfunction "2_2") (pintype "passive"))
      (node (ref "D3") (pin "2") (pinfunction "K_2") (pintype "passive"))
      (node (ref "RF3") (pin "2") (pinfunction "2_2") (pintype "passive"))
      (node (ref "RK3") (pin "2") (pinfunction "2_2") (pintype "passive"))
    )
    (net (code "154") (name "Net-(D4-K)") (class "Default")
      (node (ref "C4") (pin "2") (pinfunction "2_2") (pintype "passive"))
      (node (ref "D4") (pin "2") (pinfunction "K_2") (pintype "passive"))
      (node (ref "RF4") (pin "2") (pinfunction "2_2") (pintype "passive"))
      (node (ref "RK4") (pin "2") (pinfunction "2_2") (pintype "passive"))
    )
    (net (code "155") (name "Net-(D5-K)") (class "Default")
      (node (ref "C5") (pin "2") (pinfunction "2_2") (pintype "passive"))
      (node (ref "D5") (pin "2") (pinfunction "K_2") (pintype "passive"))
      (node (ref "RF5") (pin "2") (pinfunction "2_2") (pintype "passive"))
      (node (ref "RK5") (pin "2") (pinfunction "2_2") (pintype "passive"))
    )
    (net (code "156") (name "Net-(D6-Pad1)") (class "Default")
      (node (ref "D6") (pin "1") (pinfunction "1_1") (pintype "passive"))
      (node (ref "R6") (pin "1") (pinfunction "1_1") (pintype "passive"))
    )
    (net (code "157") (name "Net-(D7-Pad1)") (class "Default")
      (node (ref "D7") (pin "1") (pinfunction "1_1") (pintype "passive"))
      (node (ref "RR1") (pin "1") (pinfunction "1_1") (pintype "passive"))
    )
    (net (code "158") (name "Net-(DE1-A)") (class "Default")
      (node (ref "DE1") (pin "1") (pinfunction "A_1") (pintype "passive"))
      (node (ref "RG1") (pin "2") (pinfunction "2_2") (pintype "passive"))
    )
    (net (code "159") (name "Net-(DE1-K)") (class "Default")
      (node (ref "DE1") (pin "2") (pinfunction "K_2") (pintype "passive"))
      (node (ref "GP1") (pin "1") (pinfunction "A_1") (pintype "passive"))
    )
    (net (code "160") (name "Net-(DE2-A)") (class "Default")
      (node (ref "DE2") (pin "1") (pinfunction "A_1") (pintype "passive"))
      (node (ref "RG2") (pin "2") (pinfunction "2_2") (pintype "passive"))
    )
    (net (code "161") (name "Net-(DE2-K)") (class "Default")
      (node (ref "DE2") (pin "2") (pinfunction "K_2") (pintype "passive"))
      (node (ref "GP2") (pin "1") (pinfunction "A_1") (pintype "passive"))
    )
    (net (code "162") (name "Net-(DE3-A)") (class "Default")
      (node (ref "DE3") (pin "1") (pinfunction "A_1") (pintype "passive"))
      (node (ref "RG3") (pin "2") (pinfunction "2_2") (pintype "passive"))
    )
    (net (code "163") (name "Net-(DE3-K)") (class "Default")
      (node (ref "DE3") (pin "2") (pinfunction "K_2") (pintype "passive"))
      (node (ref "GP3") (pin "1") (pinfunction "A_1") (pintype "passive"))
    )
    (net (code "164") (name "Net-(DJ1-A)") (class "Default")
      (node (ref "DJ1") (pin "1") (pinfunction "A_1") (pintype "passive"))
      (node (ref "DL3") (pin "2") (pinfunction "K_2") (pintype "passive"))
      (node (ref "K1") (pin "5") (pinfunction "5_5") (pintype "passive"))
      (node (ref "QK1") (pin "1") (pinfunction "C_1") (pintype "passive"))
    )
    (net (code "165") (name "Net-(DJ2-A)") (class "Default")
      (node (ref "DJ2") (pin "1") (pinfunction "A_1") (pintype "passive"))
      (node (ref "DL4") (pin "2") (pinfunction "K_2") (pintype "passive"))
      (node (ref "K2") (pin "5") (pinfunction "5_5") (pintype "passive"))
      (node (ref "QK2") (pin "1") (pinfunction "C_1") (pintype "passive"))
    )
    (net (code "166") (name "Net-(DJ3-A)") (class "Default")
      (node (ref "DJ3") (pin "1") (pinfunction "A_1") (pintype "passive"))
      (node (ref "DL5") (pin "2") (pinfunction "K_2") (pintype "passive"))
      (node (ref "K3") (pin "5") (pinfunction "5_5") (pintype "passive"))
      (node (ref "QK3") (pin "1") (pinfunction "C_1") (pintype "passive"))
    )
    (net (code "167") (name "Net-(DJ4-A)") (class "Default")
      (node (ref "DJ4") (pin "1") (pinfunction "A_1") (pintype "passive"))
      (node (ref "DL7") (pin "2") (pinfunction "K_2") (pintype "passive"))
      (node (ref "K4") (pin "5") (pinfunction "5_5") (pintype "passive"))
      (node (ref "QK5") (pin "1") (pinfunction "C_1") (pintype "passive"))
    )
    (net (code "168") (name "Net-(DJ5-A)") (class "Default")
      (node (ref "DJ5") (pin "1") (pinfunction "A_1") (pintype "passive"))
      (node (ref "DL8") (pin "2") (pinfunction "K_2") (pintype "passive"))
      (node (ref "K5") (pin "5") (pinfunction "5_5") (pintype "passive"))
      (node (ref "QK6") (pin "1") (pinfunction "C_1") (pintype "passive"))
    )
    (net (code "169") (name "Net-(DJ6-A)") (class "Default")
      (node (ref "DJ6") (pin "1") (pinfunction "A_1") (pintype "passive"))
      (node (ref "DL9") (pin "2") (pinfunction "K_2") (pintype "passive"))
      (node (ref "K6") (pin "5") (pinfunction "5_5") (pintype "passive"))
      (node (ref "QK7") (pin "1") (pinfunction "C_1") (pintype "passive"))
    )
    (net (code "170") (name "Net-(DJ7-A)") (class "Default")
      (node (ref "DJ7") (pin "1") (pinfunction "A_1") (pintype "passive"))
      (node (ref "DL12") (pin "2") (pinfunction "K_2") (pintype "passive"))
      (node (ref "K7") (pin "5") (pinfunction "5_5") (pintype "passive"))
      (node (ref "QK8") (pin "1") (pinfunction "C_1") (pintype "passive"))
    )
    (net (code "171") (name "Net-(DJ8-A)") (class "Default")
      (node (ref "DJ8") (pin "1") (pinfunction "A_1") (pintype "passive"))
      (node (ref "DL13") (pin "2") (pinfunction "K_2") (pintype "passive"))
      (node (ref "K8") (pin "5") (pinfunction "5_5") (pintype "passive"))
      (node (ref "QK9") (pin "1") (pinfunction "C_1") (pintype "passive"))
    )
    (net (code "172") (name "Net-(DJ9-A)") (class "Default")
      (node (ref "DJ9") (pin "1") (pinfunction "A_1") (pintype "passive"))
      (node (ref "DL14") (pin "2") (pinfunction "K_2") (pintype "passive"))
      (node (ref "K9") (pin "5") (pinfunction "5_5") (pintype "passive"))
      (node (ref "QK10") (pin "1") (pinfunction "C_1") (pintype "passive"))
    )
    (net (code "173") (name "Net-(DJ10-A)") (class "Default")
      (node (ref "DJ10") (pin "1") (pinfunction "A_1") (pintype "passive"))
      (node (ref "DL16") (pin "2") (pinfunction "K_2") (pintype "passive"))
      (node (ref "K10") (pin "5") (pinfunction "5_5") (pintype "passive"))
      (node (ref "QK11") (pin "1") (pinfunction "C_1") (pintype "passive"))
    )
    (net (code "174") (name "Net-(DL1-A)") (class "Default")
      (node (ref "DL1") (pin "1") (pinfunction "A_1") (pintype "passive"))
      (node (ref "RJ4") (pin "2") (pinfunction "2_2") (pintype "passive"))
    )
    (net (code "175") (name "Net-(DL2-A)") (class "Default")
      (node (ref "DL2") (pin "1") (pinfunction "A_1") (pintype "passive"))
      (node (ref "RJ5") (pin "2") (pinfunction "2_2") (pintype "passive"))
    )
    (net (code "176") (name "Net-(DL3-A)") (class "Default")
      (node (ref "DL3") (pin "1") (pinfunction "A_1") (pintype "passive"))
      (node (ref "RJ1") (pin "2") (pinfunction "2_2") (pintype "passive"))
    )
    (net (code "177") (name "Net-(DL4-A)") (class "Default")
      (node (ref "DL4") (pin "1") (pinfunction "A_1") (pintype "passive"))
      (node (ref "RJ2") (pin "2") (pinfunction "2_2") (pintype "passive"))
    )
    (net (code "178") (name "Net-(DL5-A)") (class "Default")
      (node (ref "DL5") (pin "1") (pinfunction "A_1") (pintype "passive"))
      (node (ref "RJ3") (pin "2") (pinfunction "2_2") (pintype "passive"))
    )
    (net (code "179") (name "Net-(DL6-A)") (class "Default")
      (node (ref "DL6") (pin "1") (pinfunction "A_1") (pintype "passive"))
      (node (ref "RJ7") (pin "2") (pinfunction "2_2") (pintype "passive"))
    )
    (net (code "180") (name "Net-(DL7-A)") (class "Default")
      (node (ref "DL7") (pin "1") (pinfunction "A_1") (pintype "passive"))
      (node (ref "RJ8") (pin "2") (pinfunction "2_2") (pintype "passive"))
    )
    (net (code "181") (name "Net-(DL8-A)") (class "Default")
      (node (ref "DL8") (pin "1") (pinfunction "A_1") (pintype "passive"))
      (node (ref "RJ9") (pin "2") (pinfunction "2_2") (pintype "passive"))
    )
    (net (code "182") (name "Net-(DL9-A)") (class "Default")
      (node (ref "DL9") (pin "1") (pinfunction "A_1") (pintype "passive"))
      (node (ref "RJ10") (pin "2") (pinfunction "2_2") (pintype "passive"))
    )
    (net (code "183") (name "Net-(DL10-A)") (class "Default")
      (node (ref "DL10") (pin "1") (pinfunction "A_1") (pintype "passive"))
      (node (ref "RJ11") (pin "2") (pinfunction "2_2") (pintype "passive"))
    )
    (net (code "184") (name "Net-(DL11-A)") (class "Default")
      (node (ref "DL11") (pin "1") (pinfunction "A_1") (pintype "passive"))
      (node (ref "RJ15") (pin "2") (pinfunction "2_2") (pintype "passive"))
    )
    (net (code "185") (name "Net-(DL12-A)") (class "Default")
      (node (ref "DL12") (pin "1") (pinfunction "A_1") (pintype "passive"))
      (node (ref "RJ12") (pin "2") (pinfunction "2_2") (pintype "passive"))
    )
    (net (code "186") (name "Net-(DL13-A)") (class "Default")
      (node (ref "DL13") (pin "1") (pinfunction "A_1") (pintype "passive"))
      (node (ref "RJ13") (pin "2") (pinfunction "2_2") (pintype "passive"))
    )
    (net (code "187") (name "Net-(DL14-A)") (class "Default")
      (node (ref "DL14") (pin "1") (pinfunction "A_1") (pintype "passive"))
      (node (ref "RJ14") (pin "2") (pinfunction "2_2") (pintype "passive"))
    )
    (net (code "188") (name "Net-(DL15-A)") (class "Default")
      (node (ref "DL15") (pin "1") (pinfunction "A_1") (pintype "passive"))
      (node (ref "RJ17") (pin "2") (pinfunction "2_2") (pintype "passive"))
    )
    (net (code "189") (name "Net-(DL16-A)") (class "Default")
      (node (ref "DL16") (pin "1") (pinfunction "A_1") (pintype "passive"))
      (node (ref "RJ16") (pin "2") (pinfunction "2_2") (pintype "passive"))
    )
    (net (code "190") (name "Net-(DL17-A)") (class "Default")
      (node (ref "DL17") (pin "1") (pinfunction "A_1") (pintype "passive"))
      (node (ref "RJ18") (pin "2") (pinfunction "2_2") (pintype "passive"))
    )
    (net (code "191") (name "Net-(DL18-A)") (class "Default")
      (node (ref "DL18") (pin "1") (pinfunction "A_1") (pintype "passive"))
      (node (ref "RJ19") (pin "2") (pinfunction "2_2") (pintype "passive"))
    )
    (net (code "192") (name "Net-(HC1-SQH)") (class "Default")
      (node (ref "HC1") (pin "9") (pinfunction "SQH_9") (pintype "passive"))
      (node (ref "HC2") (pin "14") (pinfunction "SER_14") (pintype "passive"))
    )
    (net (code "193") (name "Net-(J1-CLK)") (class "Default")
      (node (ref "J1") (pin "7") (pinfunction "CLK_7") (pintype "passive"))
      (node (ref "RA9") (pin "1") (pinfunction "1_1") (pintype "passive"))
    )
    (net (code "194") (name "Net-(J1-I{slash}O)") (class "Default")
      (node (ref "J1") (pin "6") (pinfunction "I/O_6") (pintype "passive"))
      (node (ref "RA6") (pin "1") (pinfunction "1_1") (pintype "passive"))
      (node (ref "RA8") (pin "2") (pinfunction "2_2") (pintype "passive"))
    )
    (net (code "195") (name "Net-(J1-RST)") (class "Default")
      (node (ref "J1") (pin "5") (pinfunction "RST_5") (pintype "passive"))
      (node (ref "RA7") (pin "2") (pinfunction "2_2") (pintype "passive"))
    )
    (net (code "196") (name "Net-(LS1-Pad1)") (class "Default")
      (node (ref "LS1") (pin "1") (pinfunction "1_1") (pintype "passive"))
      (node (ref "RJ6") (pin "2") (pinfunction "2_2") (pintype "passive"))
    )
    (net (code "197") (name "Net-(QK1-B)") (class "Default")
      (node (ref "QK1") (pin "2") (pinfunction "B_2") (pintype "passive"))
      (node (ref "RH1") (pin "1") (pinfunction "1_1") (pintype "passive"))
      (node (ref "RI1") (pin "1") (pinfunction "1_1") (pintype "passive"))
    )
    (net (code "198") (name "Net-(QK2-B)") (class "Default")
      (node (ref "QK2") (pin "2") (pinfunction "B_2") (pintype "passive"))
      (node (ref "RH2") (pin "1") (pinfunction "1_1") (pintype "passive"))
      (node (ref "RI2") (pin "1") (pinfunction "1_1") (pintype "passive"))
    )
    (net (code "199") (name "Net-(QK3-B)") (class "Default")
      (node (ref "QK3") (pin "2") (pinfunction "B_2") (pintype "passive"))
      (node (ref "RH3") (pin "1") (pinfunction "1_1") (pintype "passive"))
      (node (ref "RI3") (pin "1") (pinfunction "1_1") (pintype "passive"))
    )
    (net (code "200") (name "Net-(QK4-B)") (class "Default")
      (node (ref "QK4") (pin "2") (pinfunction "B_2") (pintype "passive"))
      (node (ref "RH4") (pin "1") (pinfunction "1_1") (pintype "passive"))
      (node (ref "RI4") (pin "1") (pinfunction "1_1") (pintype "passive"))
    )
    (net (code "201") (name "Net-(QK4-C)") (class "Default")
      (node (ref "LS1") (pin "2") (pinfunction "2_2") (pintype "passive"))
      (node (ref "QK4") (pin "1") (pinfunction "C_1") (pintype "passive"))
    )
    (net (code "202") (name "Net-(QK5-B)") (class "Default")
      (node (ref "QK5") (pin "2") (pinfunction "B_2") (pintype "passive"))
      (node (ref "RH11") (pin "1") (pinfunction "1_1") (pintype "passive"))
      (node (ref "RI5") (pin "1") (pinfunction "1_1") (pintype "passive"))
    )
    (net (code "203") (name "Net-(QK6-B)") (class "Default")
      (node (ref "QK6") (pin "2") (pinfunction "B_2") (pintype "passive"))
      (node (ref "RH12") (pin "1") (pinfunction "1_1") (pintype "passive"))
      (node (ref "RI6") (pin "1") (pinfunction "1_1") (pintype "passive"))
    )
    (net (code "204") (name "Net-(QK7-B)") (class "Default")
      (node (ref "QK7") (pin "2") (pinfunction "B_2") (pintype "passive"))
      (node (ref "RH13") (pin "1") (pinfunction "1_1") (pintype "passive"))
      (node (ref "RI7") (pin "1") (pinfunction "1_1") (pintype "passive"))
    )
    (net (code "205") (name "Net-(QK8-B)") (class "Default")
      (node (ref "QK8") (pin "2") (pinfunction "B_2") (pintype "passive"))
      (node (ref "RH21") (pin "1") (pinfunction "1_1") (pintype "passive"))
      (node (ref "RI8") (pin "1") (pinfunction "1_1") (pintype "passive"))
    )
    (net (code "206") (name "Net-(QK9-B)") (class "Default")
      (node (ref "QK9") (pin "2") (pinfunction "B_2") (pintype "passive"))
      (node (ref "RH24") (pin "1") (pinfunction "1_1") (pintype "passive"))
      (node (ref "RI9") (pin "1") (pinfunction "1_1") (pintype "passive"))
    )
    (net (code "207") (name "Net-(QK10-B)") (class "Default")
      (node (ref "QK10") (pin "2") (pinfunction "B_2") (pintype "passive"))
      (node (ref "RH25") (pin "1") (pinfunction "1_1") (pintype "passive"))
      (node (ref "RI10") (pin "1") (pinfunction "1_1") (pintype "passive"))
    )
    (net (code "208") (name "Net-(QK11-B)") (class "Default")
      (node (ref "QK11") (pin "2") (pinfunction "B_2") (pintype "passive"))
      (node (ref "RH29") (pin "1") (pinfunction "1_1") (pintype "passive"))
      (node (ref "RI11") (pin "1") (pinfunction "1_1") (pintype "passive"))
    )
    (net (code "209") (name "Net-(QK12-B)") (class "Default")
      (node (ref "QK12") (pin "2") (pinfunction "B_2") (pintype "passive"))
      (node (ref "RH42") (pin "1") (pinfunction "1_1") (pintype "passive"))
      (node (ref "RI12") (pin "1") (pinfunction "1_1") (pintype "passive"))
    )
    (net (code "210") (name "Net-(QK13-B)") (class "Default")
      (node (ref "QK13") (pin "2") (pinfunction "B_2") (pintype "passive"))
      (node (ref "RH43") (pin "1") (pinfunction "1_1") (pintype "passive"))
      (node (ref "RI13") (pin "1") (pinfunction "1_1") (pintype "passive"))
    )
    (net (code "211") (name "Net-(QK13-C)") (class "Default")
      (node (ref "QK13") (pin "1") (pinfunction "C_1") (pintype "passive"))
      (node (ref "S1") (pin "1") (pinfunction "1_1") (pintype "passive"))
      (node (ref "UA1") (pin "1") (pinfunction "GPIO1_1") (pintype "passive"))
      (node (ref "VR1") (pin "1") (pintype "passive"))
    )
    (net (code "212") (name "Net-(QK14-B)") (class "Default")
      (node (ref "QK14") (pin "2") (pinfunction "B_2") (pintype "passive"))
      (node (ref "RH44") (pin "1") (pinfunction "1_1") (pintype "passive"))
      (node (ref "RI14") (pin "1") (pinfunction "1_1") (pintype "passive"))
    )
    (net (code "213") (name "Net-(RE2-Pad2)") (class "Default")
      (node (ref "RE2") (pin "2") (pinfunction "2_2") (pintype "passive"))
      (node (ref "RW1") (pin "1") (pinfunction "1_1") (pintype "passive"))
      (node (ref "RY1") (pin "2") (pinfunction "2_2") (pintype "passive"))
    )
    (net (code "214") (name "Net-(RE4-Pad2)") (class "Default")
      (node (ref "RE4") (pin "2") (pinfunction "2_2") (pintype "passive"))
      (node (ref "RW2") (pin "1") (pinfunction "1_1") (pintype "passive"))
      (node (ref "RY2") (pin "2") (pinfunction "2_2") (pintype "passive"))
    )
    (net (code "215") (name "Net-(RE6-Pad2)") (class "Default")
      (node (ref "RE6") (pin "2") (pinfunction "2_2") (pintype "passive"))
      (node (ref "RW3") (pin "1") (pinfunction "1_1") (pintype "passive"))
      (node (ref "RY3") (pin "2") (pinfunction "2_2") (pintype "passive"))
    )
    (net (code "216") (name "Net-(RE8-Pad2)") (class "Default")
      (node (ref "RE8") (pin "2") (pinfunction "2_2") (pintype "passive"))
      (node (ref "RW4") (pin "1") (pinfunction "1_1") (pintype "passive"))
      (node (ref "RY4") (pin "2") (pinfunction "2_2") (pintype "passive"))
    )
    (net (code "217") (name "Net-(RE10-Pad2)") (class "Default")
      (node (ref "RE10") (pin "2") (pinfunction "2_2") (pintype "passive"))
      (node (ref "RW5") (pin "1") (pinfunction "1_1") (pintype "passive"))
      (node (ref "RY5") (pin "2") (pinfunction "2_2") (pintype "passive"))
    )
    (net (code "218") (name "Net-(TCL1-CS)") (class "Default")
      (node (ref "RH8") (pin "2") (pinfunction "2_2") (pintype "passive"))
      (node (ref "TCL1") (pin "3") (pinfunction "CS_3") (pintype "passive"))
    )
    (net (code "219") (name "Net-(TCL1-DIN)") (class "Default")
      (node (ref "RH5") (pin "2") (pinfunction "2_2") (pintype "passive"))
      (node (ref "TCL1") (pin "1") (pinfunction "DIN_1") (pintype "passive"))
    )
    (net (code "220") (name "Net-(TCL1-DOUT)") (class "Default")
      (node (ref "RH10") (pin "2") (pinfunction "2_2") (pintype "passive"))
      (node (ref "TCL1") (pin "4") (pinfunction "DOUT_4") (pintype "passive"))
    )
    (net (code "221") (name "Net-(TCL1-OUT)") (class "Default")
      (node (ref "RH7") (pin "2") (pinfunction "2_2") (pintype "passive"))
      (node (ref "RJ7") (pin "1") (pinfunction "1_1") (pintype "passive"))
      (node (ref "TCL1") (pin "7") (pinfunction "OUT_7") (pintype "passive"))
    )
    (net (code "222") (name "Net-(TCL1-REFIN)") (class "Default")
      (node (ref "RH9") (pin "2") (pinfunction "2_2") (pintype "passive"))
      (node (ref "TCL1") (pin "6") (pinfunction "REFIN_6") (pintype "passive"))
    )
    (net (code "223") (name "Net-(TCL1-SCLK)") (class "Default")
      (node (ref "RH6") (pin "2") (pinfunction "2_2") (pintype "passive"))
      (node (ref "TCL1") (pin "2") (pinfunction "SCLK_2") (pintype "passive"))
    )
    (net (code "224") (name "Net-(TCL2-CS)") (class "Default")
      (node (ref "RH17") (pin "2") (pinfunction "2_2") (pintype "passive"))
      (node (ref "TCL2") (pin "3") (pinfunction "CS_3") (pintype "passive"))
    )
    (net (code "225") (name "Net-(TCL2-DIN)") (class "Default")
      (node (ref "RH14") (pin "2") (pinfunction "2_2") (pintype "passive"))
      (node (ref "TCL2") (pin "1") (pinfunction "DIN_1") (pintype "passive"))
    )
    (net (code "226") (name "Net-(TCL2-DOUT)") (class "Default")
      (node (ref "RH19") (pin "2") (pinfunction "2_2") (pintype "passive"))
      (node (ref "TCL2") (pin "4") (pinfunction "DOUT_4") (pintype "passive"))
    )
    (net (code "227") (name "Net-(TCL2-OUT)") (class "Default")
      (node (ref "RH16") (pin "2") (pinfunction "2_2") (pintype "passive"))
      (node (ref "RJ11") (pin "1") (pinfunction "1_1") (pintype "passive"))
      (node (ref "TCL2") (pin "7") (pinfunction "OUT_7") (pintype "passive"))
    )
    (net (code "228") (name "Net-(TCL2-REFIN)") (class "Default")
      (node (ref "RH18") (pin "2") (pinfunction "2_2") (pintype "passive"))
      (node (ref "TCL2") (pin "6") (pinfunction "REFIN_6") (pintype "passive"))
    )
    (net (code "229") (name "Net-(TCL2-SCLK)") (class "Default")
      (node (ref "RH15") (pin "2") (pinfunction "2_2") (pintype "passive"))
      (node (ref "TCL2") (pin "2") (pinfunction "SCLK_2") (pintype "passive"))
    )
    (net (code "230") (name "Net-(TCL3-CS)") (class "Default")
      (node (ref "RH26") (pin "2") (pinfunction "2_2") (pintype "passive"))
      (node (ref "TCL3") (pin "3") (pinfunction "CS_3") (pintype "passive"))
    )
    (net (code "231") (name "Net-(TCL3-DIN)") (class "Default")
      (node (ref "RH20") (pin "2") (pinfunction "2_2") (pintype "passive"))
      (node (ref "TCL3") (pin "1") (pinfunction "DIN_1") (pintype "passive"))
    )
    (net (code "232") (name "Net-(TCL3-DOUT)") (class "Default")
      (node (ref "RH28") (pin "2") (pinfunction "2_2") (pintype "passive"))
      (node (ref "TCL3") (pin "4") (pinfunction "DOUT_4") (pintype "passive"))
    )
    (net (code "233") (name "Net-(TCL3-OUT)") (class "Default")
      (node (ref "RH23") (pin "2") (pinfunction "2_2") (pintype "passive"))
      (node (ref "RJ15") (pin "1") (pinfunction "1_1") (pintype "passive"))
      (node (ref "TCL3") (pin "7") (pinfunction "OUT_7") (pintype "passive"))
    )
    (net (code "234") (name "Net-(TCL3-REFIN)") (class "Default")
      (node (ref "RH27") (pin "2") (pinfunction "2_2") (pintype "passive"))
      (node (ref "TCL3") (pin "6") (pinfunction "REFIN_6") (pintype "passive"))
    )
    (net (code "235") (name "Net-(TCL3-SCLK)") (class "Default")
      (node (ref "RH22") (pin "2") (pinfunction "2_2") (pintype "passive"))
      (node (ref "TCL3") (pin "2") (pinfunction "SCLK_2") (pintype "passive"))
    )
    (net (code "236") (name "Net-(TCL4-CS)") (class "Default")
      (node (ref "RH33") (pin "2") (pinfunction "2_2") (pintype "passive"))
      (node (ref "TCL4") (pin "3") (pinfunction "CS_3") (pintype "passive"))
    )
    (net (code "237") (name "Net-(TCL4-DIN)") (class "Default")
      (node (ref "RH30") (pin "2") (pinfunction "2_2") (pintype "passive"))
      (node (ref "TCL4") (pin "1") (pinfunction "DIN_1") (pintype "passive"))
    )
    (net (code "238") (name "Net-(TCL4-DOUT)") (class "Default")
      (node (ref "RH35") (pin "2") (pinfunction "2_2") (pintype "passive"))
      (node (ref "TCL4") (pin "4") (pinfunction "DOUT_4") (pintype "passive"))
    )
    (net (code "239") (name "Net-(TCL4-OUT)") (class "Default")
      (node (ref "RH32") (pin "2") (pinfunction "2_2") (pintype "passive"))
      (node (ref "RJ17") (pin "1") (pinfunction "1_1") (pintype "passive"))
      (node (ref "TCL4") (pin "7") (pinfunction "OUT_7") (pintype "passive"))
    )
    (net (code "240") (name "Net-(TCL4-REFIN)") (class "Default")
      (node (ref "RH34") (pin "2") (pinfunction "2_2") (pintype "passive"))
      (node (ref "TCL4") (pin "6") (pinfunction "REFIN_6") (pintype "passive"))
    )
    (net (code "241") (name "Net-(TCL4-SCLK)") (class "Default")
      (node (ref "RH31") (pin "2") (pinfunction "2_2") (pintype "passive"))
      (node (ref "TCL4") (pin "2") (pinfunction "SCLK_2") (pintype "passive"))
    )
    (net (code "242") (name "Net-(TCL5-CS)") (class "Default")
      (node (ref "RH39") (pin "2") (pinfunction "2_2") (pintype "passive"))
      (node (ref "TCL5") (pin "3") (pinfunction "CS_3") (pintype "passive"))
    )
    (net (code "243") (name "Net-(TCL5-DIN)") (class "Default")
      (node (ref "RH36") (pin "2") (pinfunction "2_2") (pintype "passive"))
      (node (ref "TCL5") (pin "1") (pinfunction "DIN_1") (pintype "passive"))
    )
    (net (code "244") (name "Net-(TCL5-DOUT)") (class "Default")
      (node (ref "RH41") (pin "2") (pinfunction "2_2") (pintype "passive"))
      (node (ref "TCL5") (pin "4") (pinfunction "DOUT_4") (pintype "passive"))
    )
    (net (code "245") (name "Net-(TCL5-OUT)") (class "Default")
      (node (ref "RH38") (pin "2") (pinfunction "2_2") (pintype "passive"))
      (node (ref "RJ18") (pin "1") (pinfunction "1_1") (pintype "passive"))
      (node (ref "TCL5") (pin "7") (pinfunction "OUT_7") (pintype "passive"))
    )
    (net (code "246") (name "Net-(TCL5-REFIN)") (class "Default")
      (node (ref "RH40") (pin "2") (pinfunction "2_2") (pintype "passive"))
      (node (ref "TCL5") (pin "6") (pinfunction "REFIN_6") (pintype "passive"))
    )
    (net (code "247") (name "Net-(TCL5-SCLK)") (class "Default")
      (node (ref "RH37") (pin "2") (pinfunction "2_2") (pintype "passive"))
      (node (ref "TCL5") (pin "2") (pinfunction "SCLK_2") (pintype "passive"))
    )
    (net (code "248") (name "Net-(TTL-SW1-Pad2)") (class "Default")
      (node (ref "TTL-SW1") (pin "2") (pinfunction "2_2") (pintype "passive"))
      (node (ref "TTL1") (pin "1") (pinfunction "1_1") (pintype "passive"))
    )
    (net (code "249") (name "Net-(U6A-IN+)") (class "Default")
      (node (ref "RN1") (pin "1") (pinfunction "1_1") (pintype "passive"))
      (node (ref "RT1") (pin "1") (pinfunction "1_1") (pintype "passive"))
      (node (ref "U6") (pin "3") (pinfunction "IN+_3") (pintype "input"))
    )
    (net (code "250") (name "Net-(U6A-IN-)") (class "Default")
      (node (ref "RA1") (pin "2") (pinfunction "2_2") (pintype "passive"))
      (node (ref "RY1") (pin "1") (pinfunction "1_1") (pintype "passive"))
      (node (ref "U6") (pin "2") (pinfunction "IN-_2") (pintype "input"))
    )
    (net (code "251") (name "Net-(U6A-OUT)") (class "Default")
      (node (ref "RA1") (pin "1") (pinfunction "1_1") (pintype "passive"))
      (node (ref "RF1") (pin "1") (pinfunction "1_1") (pintype "passive"))
      (node (ref "U6") (pin "1") (pinfunction "OUT_1") (pintype "output"))
    )
    (net (code "252") (name "Net-(U6B-IN+)") (class "Default")
      (node (ref "RN2") (pin "1") (pinfunction "1_1") (pintype "passive"))
      (node (ref "RT2") (pin "1") (pinfunction "1_1") (pintype "passive"))
      (node (ref "U6") (pin "5") (pinfunction "IN+_5") (pintype "input"))
    )
    (net (code "253") (name "Net-(U6B-IN-)") (class "Default")
      (node (ref "RA2") (pin "2") (pinfunction "2_2") (pintype "passive"))
      (node (ref "RY2") (pin "1") (pinfunction "1_1") (pintype "passive"))
      (node (ref "U6") (pin "6") (pinfunction "IN-_6") (pintype "input"))
    )
    (net (code "254") (name "Net-(U6B-OUT)") (class "Default")
      (node (ref "RA2") (pin "1") (pinfunction "1_1") (pintype "passive"))
      (node (ref "RF2") (pin "1") (pinfunction "1_1") (pintype "passive"))
      (node (ref "U6") (pin "7") (pinfunction "OUT_7") (pintype "output"))
    )
    (net (code "255") (name "Net-(U7A-IN+)") (class "Default")
      (node (ref "RN3") (pin "1") (pinfunction "1_1") (pintype "passive"))
      (node (ref "RT3") (pin "1") (pinfunction "1_1") (pintype "passive"))
      (node (ref "U7") (pin "3") (pinfunction "IN+_3") (pintype "input"))
    )
    (net (code "256") (name "Net-(U7A-IN-)") (class "Default")
      (node (ref "RA3") (pin "2") (pinfunction "2_2") (pintype "passive"))
      (node (ref "RY3") (pin "1") (pinfunction "1_1") (pintype "passive"))
      (node (ref "U7") (pin "2") (pinfunction "IN-_2") (pintype "input"))
    )
    (net (code "257") (name "Net-(U7A-OUT)") (class "Default")
      (node (ref "RA3") (pin "1") (pinfunction "1_1") (pintype "passive"))
      (node (ref "RF3") (pin "1") (pinfunction "1_1") (pintype "passive"))
      (node (ref "U7") (pin "1") (pinfunction "OUT_1") (pintype "output"))
    )
    (net (code "258") (name "Net-(U7B-IN+)") (class "Default")
      (node (ref "RN4") (pin "1") (pinfunction "1_1") (pintype "passive"))
      (node (ref "RT4") (pin "1") (pinfunction "1_1") (pintype "passive"))
      (node (ref "U7") (pin "5") (pinfunction "IN+_5") (pintype "input"))
    )
    (net (code "259") (name "Net-(U7B-IN-)") (class "Default")
      (node (ref "RA4") (pin "2") (pinfunction "2_2") (pintype "passive"))
      (node (ref "RY4") (pin "1") (pinfunction "1_1") (pintype "passive"))
      (node (ref "U7") (pin "6") (pinfunction "IN-_6") (pintype "input"))
    )
    (net (code "260") (name "Net-(U7B-OUT)") (class "Default")
      (node (ref "RA4") (pin "1") (pinfunction "1_1") (pintype "passive"))
      (node (ref "RF4") (pin "1") (pinfunction "1_1") (pintype "passive"))
      (node (ref "U7") (pin "7") (pinfunction "OUT_7") (pintype "output"))
    )
    (net (code "261") (name "Net-(U9A-IN+)") (class "Default")
      (node (ref "RN5") (pin "1") (pinfunction "1_1") (pintype "passive"))
      (node (ref "RT5") (pin "1") (pinfunction "1_1") (pintype "passive"))
      (node (ref "U9") (pin "3") (pinfunction "IN+_3") (pintype "input"))
    )
    (net (code "262") (name "Net-(U9A-IN-)") (class "Default")
      (node (ref "RA5") (pin "2") (pinfunction "2_2") (pintype "passive"))
      (node (ref "RY5") (pin "1") (pinfunction "1_1") (pintype "passive"))
      (node (ref "U9") (pin "2") (pinfunction "IN-_2") (pintype "input"))
    )
    (net (code "263") (name "Net-(U9A-OUT)") (class "Default")
      (node (ref "RA5") (pin "1") (pinfunction "1_1") (pintype "passive"))
      (node (ref "RF5") (pin "1") (pinfunction "1_1") (pintype "passive"))
      (node (ref "U9") (pin "1") (pinfunction "OUT_1") (pintype "output"))
    )
    (net (code "264") (name "Net-(UM1-PF0-OSC_IN)") (class "Default")
      (node (ref "CU11") (pin "1") (pinfunction "1_1") (pintype "passive"))
      (node (ref "UM1") (pin "5") (pinfunction "PF0-OSC_IN_5") (pintype "passive"))
      (node (ref "X1") (pin "1") (pinfunction "OSC1_1") (pintype "passive"))
    )
    (net (code "265") (name "Net-(UM1-PF1-OSC_OUT)") (class "Default")
      (node (ref "CU12") (pin "1") (pinfunction "1_1") (pintype "passive"))
      (node (ref "UM1") (pin "6") (pinfunction "PF1-OSC_OUT_6") (pintype "passive"))
      (node (ref "X1") (pin "2") (pinfunction "OSC2_2") (pintype "passive"))
    )
    (net (code "266") (name "SIM_PW") (class "Default")
      (node (ref "C6") (pin "1") (pinfunction "1_1") (pintype "passive"))
      (node (ref "C7") (pin "2") (pinfunction "2_2") (pintype "passive"))
      (node (ref "J1") (pin "3") (pinfunction "VCC_3") (pintype "passive"))
      (node (ref "RA6") (pin "2") (pinfunction "2_2") (pintype "passive"))
      (node (ref "UA1") (pin "21") (pinfunction "SIM_VDD_21") (pintype "passive"))
      (node (ref "VR4") (pin "1") (pintype "passive"))
    )
    (net (code "267") (name "VBAT") (class "Default")
      (node (ref "CD1") (pin "2") (pinfunction "2_2") (pintype "passive"))
      (node (ref "CD2") (pin "2") (pinfunction "2_2") (pintype "passive"))
      (node (ref "CD3") (pin "2") (pinfunction "2_2") (pintype "passive"))
      (node (ref "CD4") (pin "1") (pinfunction "1_1") (pintype "passive"))
      (node (ref "Cu29") (pin "1") (pinfunction "1_1") (pintype "passive"))
      (node (ref "Cu30") (pin "2") (pinfunction "2_2") (pintype "passive"))
      (node (ref "U10") (pin "2") (pinfunction "OUT_2") (pintype "power_in"))
      (node (ref "U10") (pin "4") (pinfunction "OUT_4") (pintype "power_in"))
      (node (ref "UA1") (pin "37") (pinfunction "VBAT_37") (pintype "passive"))
      (node (ref "UA1") (pin "38") (pinfunction "VBAT_38") (pintype "passive"))
    )
    (net (code "268") (name "VCC2.5V") (class "Default")
      (node (ref "Cu5") (pin "1") (pinfunction "1_1") (pintype "passive"))
      (node (ref "Cu6") (pin "2") (pinfunction "2_2") (pintype "passive"))
      (node (ref "RH18") (pin "1") (pinfunction "1_1") (pintype "passive"))
      (node (ref "RH27") (pin "1") (pinfunction "1_1") (pintype "passive"))
      (node (ref "RH34") (pin "1") (pinfunction "1_1") (pintype "passive"))
      (node (ref "RH40") (pin "1") (pinfunction "1_1") (pintype "passive"))
      (node (ref "RH9") (pin "1") (pinfunction "1_1") (pintype "passive"))
      (node (ref "RJ5") (pin "1") (pinfunction "1_1") (pintype "passive"))
      (node (ref "U4") (pin "2") (pinfunction "OUT_2") (pintype "power_in"))
      (node (ref "U4") (pin "4") (pinfunction "OUT_4") (pintype "power_in"))
    )
    (net (code "269") (name "VCC3.3") (class "Default")
      (node (ref "CJ1") (pin "1") (pinfunction "1_1") (pintype "passive"))
      (node (ref "CJ3") (pin "1") (pinfunction "1_1") (pintype "passive"))
      (node (ref "CJ5") (pin "1") (pinfunction "1_1") (pintype "passive"))
      (node (ref "CK1") (pin "2") (pinfunction "2_2") (pintype "passive"))
      (node (ref "CU13") (pin "1") (pinfunction "1_1") (pintype "passive"))
      (node (ref "CU14") (pin "1") (pinfunction "1_1") (pintype "passive"))
      (node (ref "CU16") (pin "1") (pinfunction "1_1") (pintype "passive"))
      (node (ref "CU17") (pin "1") (pinfunction "1_1") (pintype "passive"))
      (node (ref "CU20") (pin "1") (pinfunction "1_1") (pintype "passive"))
      (node (ref "Cu1") (pin "1") (pinfunction "1_1") (pintype "passive"))
      (node (ref "Cu2") (pin "2") (pinfunction "2_2") (pintype "passive"))
      (node (ref "HC1") (pin "16") (pinfunction "VCC_16") (pintype "passive"))
      (node (ref "HC2") (pin "16") (pinfunction "VCC_16") (pintype "passive"))
      (node (ref "IIC1") (pin "8") (pinfunction "Vcc_8") (pintype "passive"))
      (node (ref "JP2") (pin "1") (pinfunction "1_1") (pintype "passive"))
      (node (ref "P4") (pin "3") (pinfunction "3_3") (pintype "passive"))
      (node (ref "R2") (pin "2") (pinfunction "2_2") (pintype "passive"))
      (node (ref "R3") (pin "2") (pinfunction "2_2") (pintype "passive"))
      (node (ref "R4") (pin "2") (pinfunction "2_2") (pintype "passive"))
      (node (ref "RD1") (pin "1") (pinfunction "1_1") (pintype "passive"))
      (node (ref "RJ6") (pin "1") (pinfunction "1_1") (pintype "passive"))
      (node (ref "RO1") (pin "2") (pinfunction "2_2") (pintype "passive"))
      (node (ref "RO2") (pin "2") (pinfunction "2_2") (pintype "passive"))
      (node (ref "RO3") (pin "1") (pinfunction "1_1") (pintype "passive"))
      (node (ref "RO4") (pin "2") (pinfunction "2_2") (pintype "passive"))
      (node (ref "RO5") (pin "1") (pinfunction "1_1") (pintype "passive"))
      (node (ref "RO6") (pin "2") (pinfunction "2_2") (pintype "passive"))
      (node (ref "RU1") (pin "1") (pinfunction "1_1") (pintype "passive"))
      (node (ref "RU3") (pin "1") (pinfunction "1_1") (pintype "passive"))
      (node (ref "RU4") (pin "1") (pinfunction "1_1") (pintype "passive"))
      (node (ref "RV1") (pin "2") (pinfunction "2_2") (pintype "passive"))
      (node (ref "RV2") (pin "2") (pinfunction "2_2") (pintype "passive"))
      (node (ref "RZ1") (pin "2") (pinfunction "2_2") (pintype "passive"))
      (node (ref "RZ3") (pin "2") (pinfunction "2_2") (pintype "passive"))
      (node (ref "ST-LINK1") (pin "1") (pinfunction "1_1") (pintype "passive"))
      (node (ref "TTL-SW1") (pin "1") (pinfunction "1_1") (pintype "passive"))
      (node (ref "U1") (pin "8") (pinfunction "VCC_8") (pintype "passive"))
      (node (ref "U2") (pin "2") (pinfunction "OUT_2") (pintype "power_in"))
      (node (ref "U2") (pin "4") (pinfunction "OUT_4") (pintype "power_in"))
      (node (ref "UM1") (pin "1") (pinfunction "VDD_1") (pintype "passive"))
      (node (ref "UM1") (pin "24") (pinfunction "VDD_24") (pintype "passive"))
      (node (ref "UM1") (pin "48") (pinfunction "VDD_48") (pintype "passive"))
      (node (ref "UM1") (pin "9") (pinfunction "VDDA_9") (pintype "passive"))
      (node (ref "W1") (pin "10") (pinfunction "3.3V_10") (pintype "passive"))
    )
    (net (code "270") (name "VCC5V2") (class "Default")
      (node (ref "Cu27") (pin "1") (pinfunction "1_1") (pintype "passive"))
      (node (ref "Cu28") (pin "2") (pinfunction "2_2") (pintype "passive"))
      (node (ref "P4") (pin "1") (pinfunction "1_1") (pintype "passive"))
      (node (ref "RJ19") (pin "1") (pinfunction "1_1") (pintype "passive"))
      (node (ref "U8") (pin "2") (pinfunction "OUT_2") (pintype "power_in"))
      (node (ref "U8") (pin "4") (pinfunction "OUT_4") (pintype "power_in"))
    )
    (net (code "271") (name "VCC5V3") (class "Default")
      (node (ref "1") (pin "6") (pinfunction "6_6") (pintype "passive"))
      (node (ref "2") (pin "6") (pinfunction "6_6") (pintype "passive"))
      (node (ref "3") (pin "6") (pinfunction "6_6") (pintype "passive"))
      (node (ref "4") (pin "6") (pinfunction "6_6") (pintype "passive"))
      (node (ref "5") (pin "6") (pinfunction "6_6") (pintype "passive"))
      (node (ref "Cu15") (pin "1") (pinfunction "1_1") (pintype "passive"))
      (node (ref "Cu21") (pin "1") (pinfunction "1_1") (pintype "passive"))
      (node (ref "Cu23") (pin "1") (pinfunction "1_1") (pintype "passive"))
      (node (ref "Cu25") (pin "1") (pinfunction "1_1") (pintype "passive"))
      (node (ref "Cu3") (pin "1") (pinfunction "1_1") (pintype "passive"))
      (node (ref "Cu4") (pin "2") (pinfunction "2_2") (pintype "passive"))
      (node (ref "Cu7") (pin "1") (pinfunction "1_1") (pintype "passive"))
      (node (ref "RJ4") (pin "1") (pinfunction "1_1") (pintype "passive"))
      (node (ref "TCL1") (pin "8") (pinfunction "VDD_8") (pintype "passive"))
      (node (ref "TCL2") (pin "8") (pinfunction "VDD_8") (pintype "passive"))
      (node (ref "TCL3") (pin "8") (pinfunction "VDD_8") (pintype "passive"))
      (node (ref "TCL4") (pin "8") (pinfunction "VDD_8") (pintype "passive"))
      (node (ref "TCL5") (pin "8") (pinfunction "VDD_8") (pintype "passive"))
      (node (ref "U3") (pin "2") (pinfunction "OUT_2") (pintype "power_in"))
      (node (ref "U3") (pin "4") (pinfunction "OUT_4") (pintype "power_in"))
    )
    (net (code "272") (name "VDDIO") (class "Default")
      (node (ref "R6") (pin "2") (pinfunction "2_2") (pintype "passive"))
      (node (ref "UA1") (pin "24") (pinfunction "VDDIO_24") (pintype "passive"))
    )
    (net (code "273") (name "unconnected-(HC2-SQH-Pad9)") (class "Default")
      (node (ref "HC2") (pin "9") (pinfunction "SQH_9") (pintype "passive"))
    )
    (net (code "274") (name "unconnected-(J1-CD-Pad1)") (class "Default")
      (node (ref "J1") (pin "1") (pinfunction "CD_1") (pintype "passive+no_connect"))
    )
    (net (code "275") (name "unconnected-(J1-VPP-Pad4)") (class "Default")
      (node (ref "J1") (pin "4") (pinfunction "VPP_4") (pintype "passive+no_connect"))
    )
    (net (code "276") (name "unconnected-(JP2-Pad3)") (class "Default")
      (node (ref "JP2") (pin "3") (pinfunction "3_3") (pintype "passive"))
    )
    (net (code "277") (name "unconnected-(K1-Pad2)") (class "Default")
      (node (ref "K1") (pin "2") (pinfunction "2_2") (pintype "passive"))
    )
    (net (code "278") (name "unconnected-(K2-Pad2)") (class "Default")
      (node (ref "K2") (pin "2") (pinfunction "2_2") (pintype "passive"))
    )
    (net (code "279") (name "unconnected-(K3-Pad2)") (class "Default")
      (node (ref "K3") (pin "2") (pinfunction "2_2") (pintype "passive"))
    )
    (net (code "280") (name "unconnected-(K4-Pad2)") (class "Default")
      (node (ref "K4") (pin "2") (pinfunction "2_2") (pintype "passive"))
    )
    (net (code "281") (name "unconnected-(K5-Pad2)") (class "Default")
      (node (ref "K5") (pin "2") (pinfunction "2_2") (pintype "passive"))
    )
    (net (code "282") (name "unconnected-(K6-Pad2)") (class "Default")
      (node (ref "K6") (pin "2") (pinfunction "2_2") (pintype "passive"))
    )
    (net (code "283") (name "unconnected-(K7-Pad2)") (class "Default")
      (node (ref "K7") (pin "2") (pinfunction "2_2") (pintype "passive"))
    )
    (net (code "284") (name "unconnected-(K8-Pad2)") (class "Default")
      (node (ref "K8") (pin "2") (pinfunction "2_2") (pintype "passive"))
    )
    (net (code "285") (name "unconnected-(K9-Pad2)") (class "Default")
      (node (ref "K9") (pin "2") (pinfunction "2_2") (pintype "passive"))
    )
    (net (code "286") (name "unconnected-(K10-Pad2)") (class "Default")
      (node (ref "K10") (pin "2") (pinfunction "2_2") (pintype "passive"))
    )
    (net (code "287") (name "unconnected-(UA1-AON_GPIO_2-Pad17)") (class "Default")
      (node (ref "UA1") (pin "17") (pinfunction "AON_GPIO_2_17") (pintype "passive"))
    )
    (net (code "288") (name "unconnected-(UA1-AON_GPIO_3-Pad16)") (class "Default")
      (node (ref "UA1") (pin "16") (pinfunction "AON_GPIO_3_16") (pintype "passive"))
    )
  )
)
